# Mainboard_LEFT.net
KiCad netlist of a schematic drawn in EAGLE
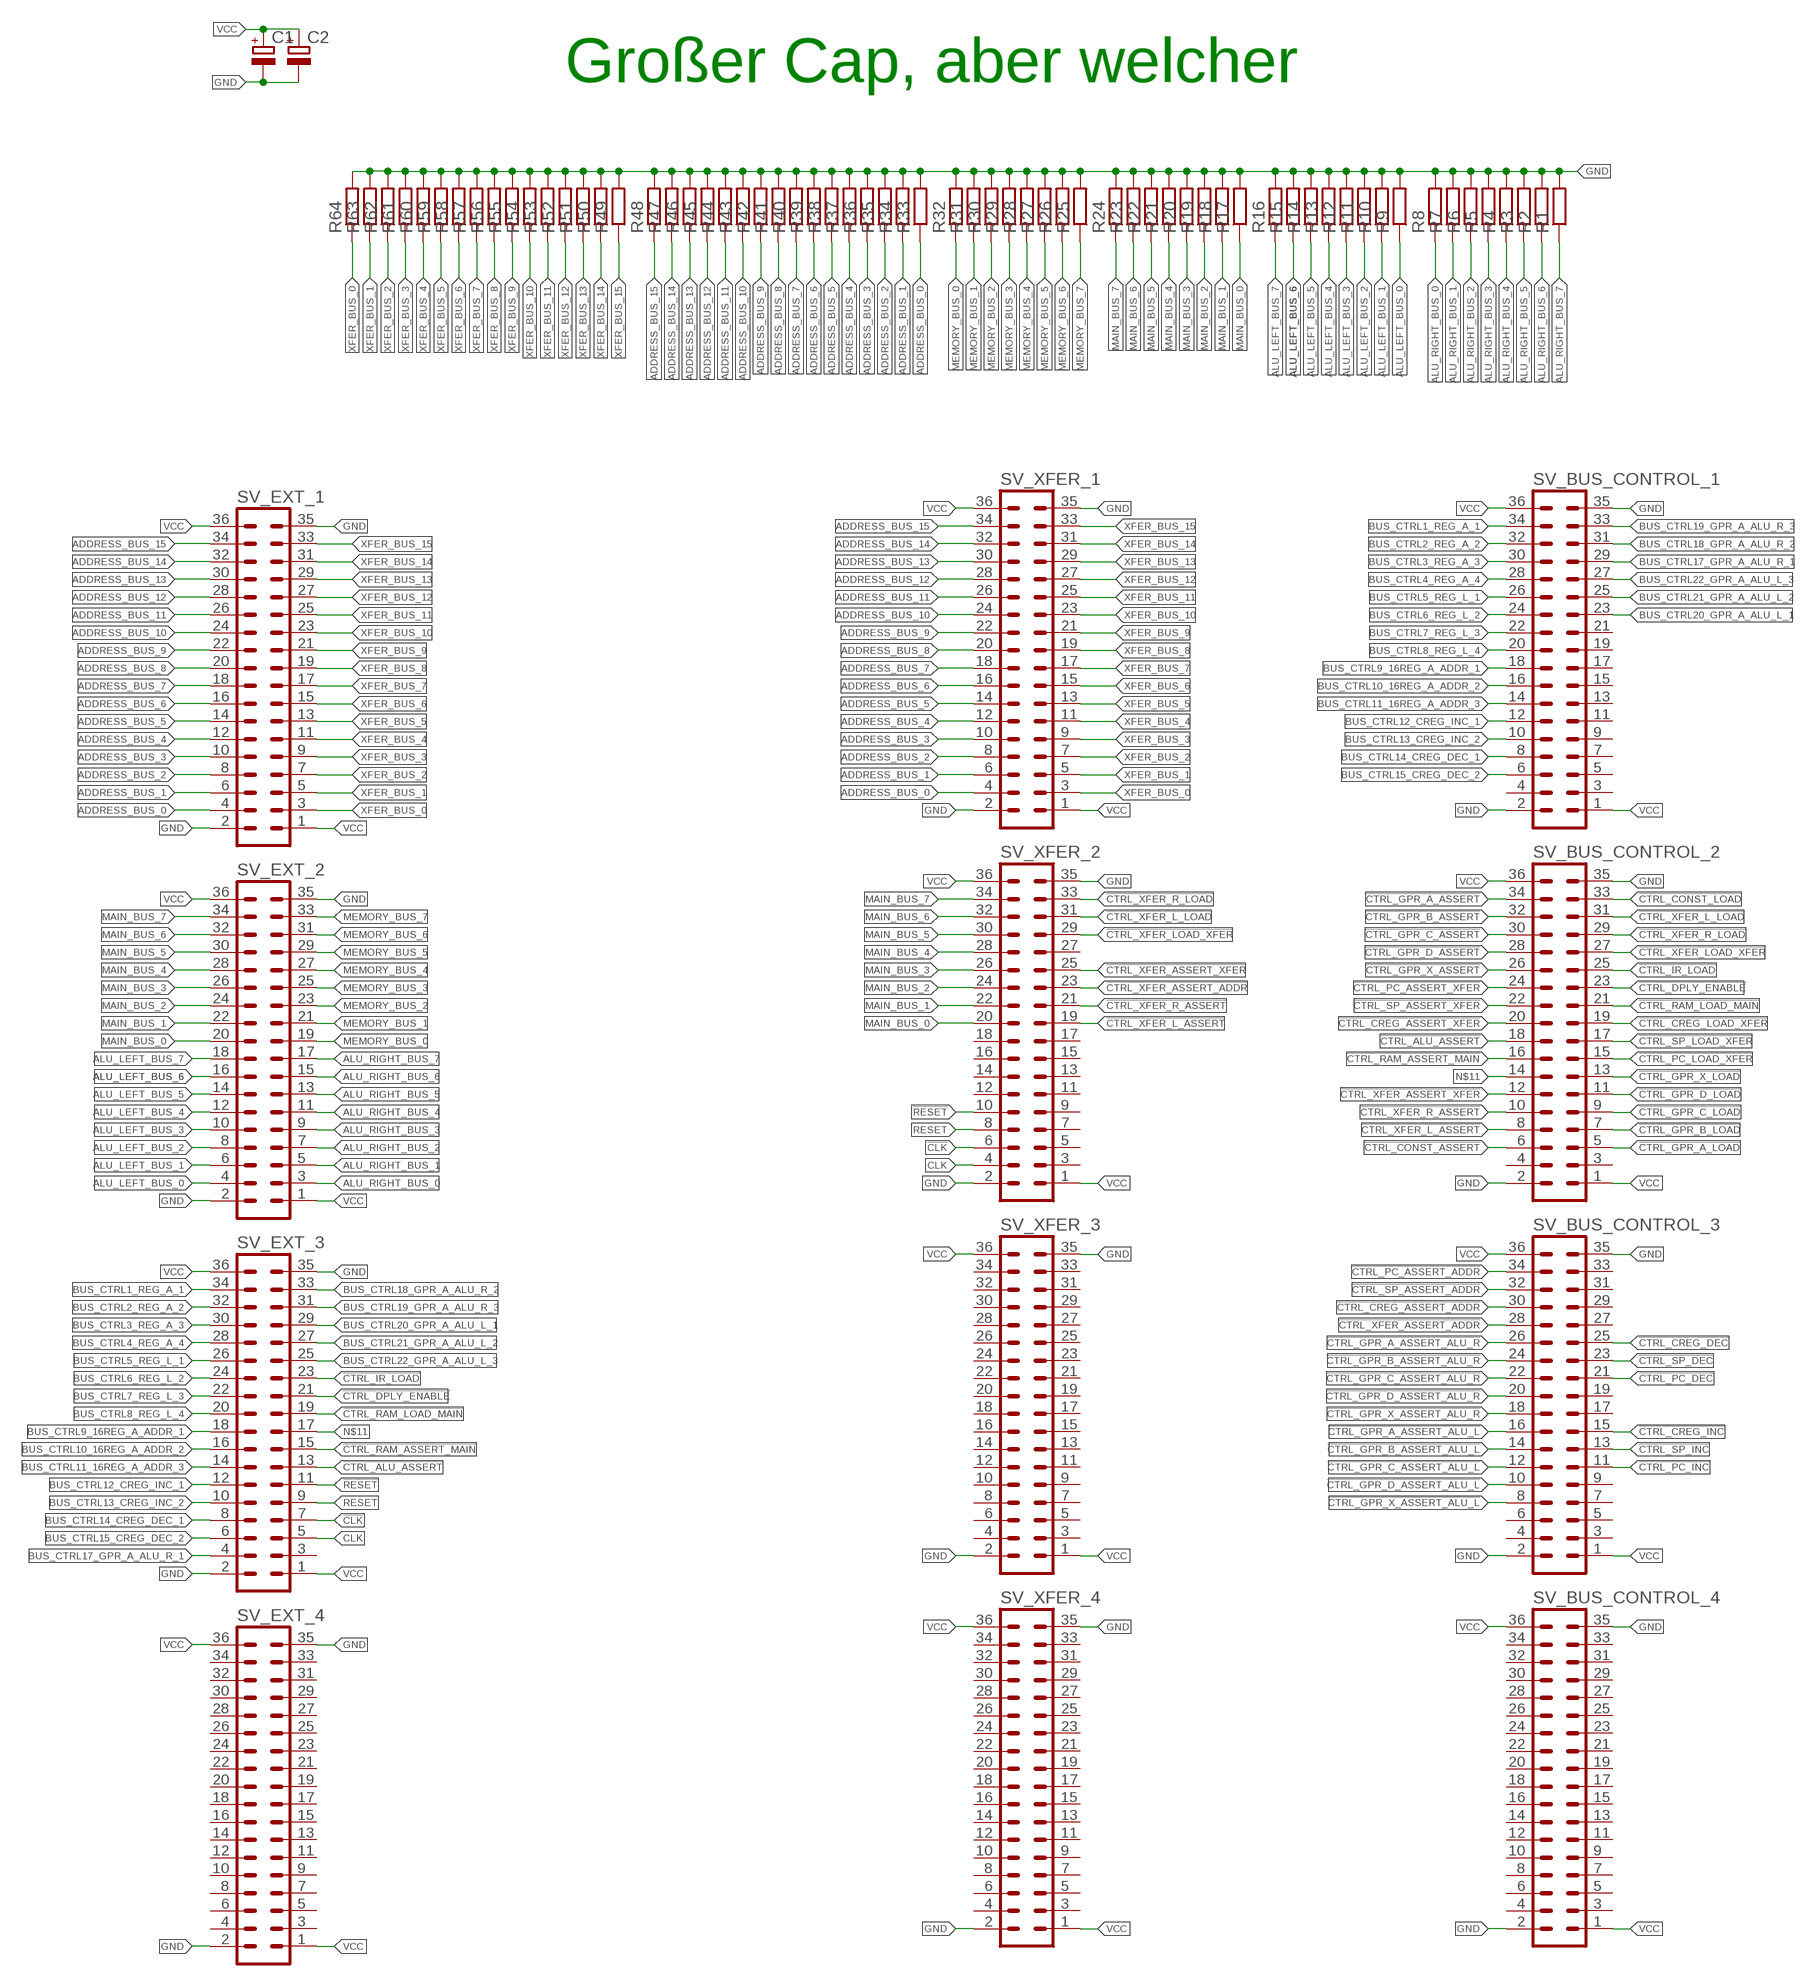
[diagram p0: schematic, sheet 1, part 1 of 2]
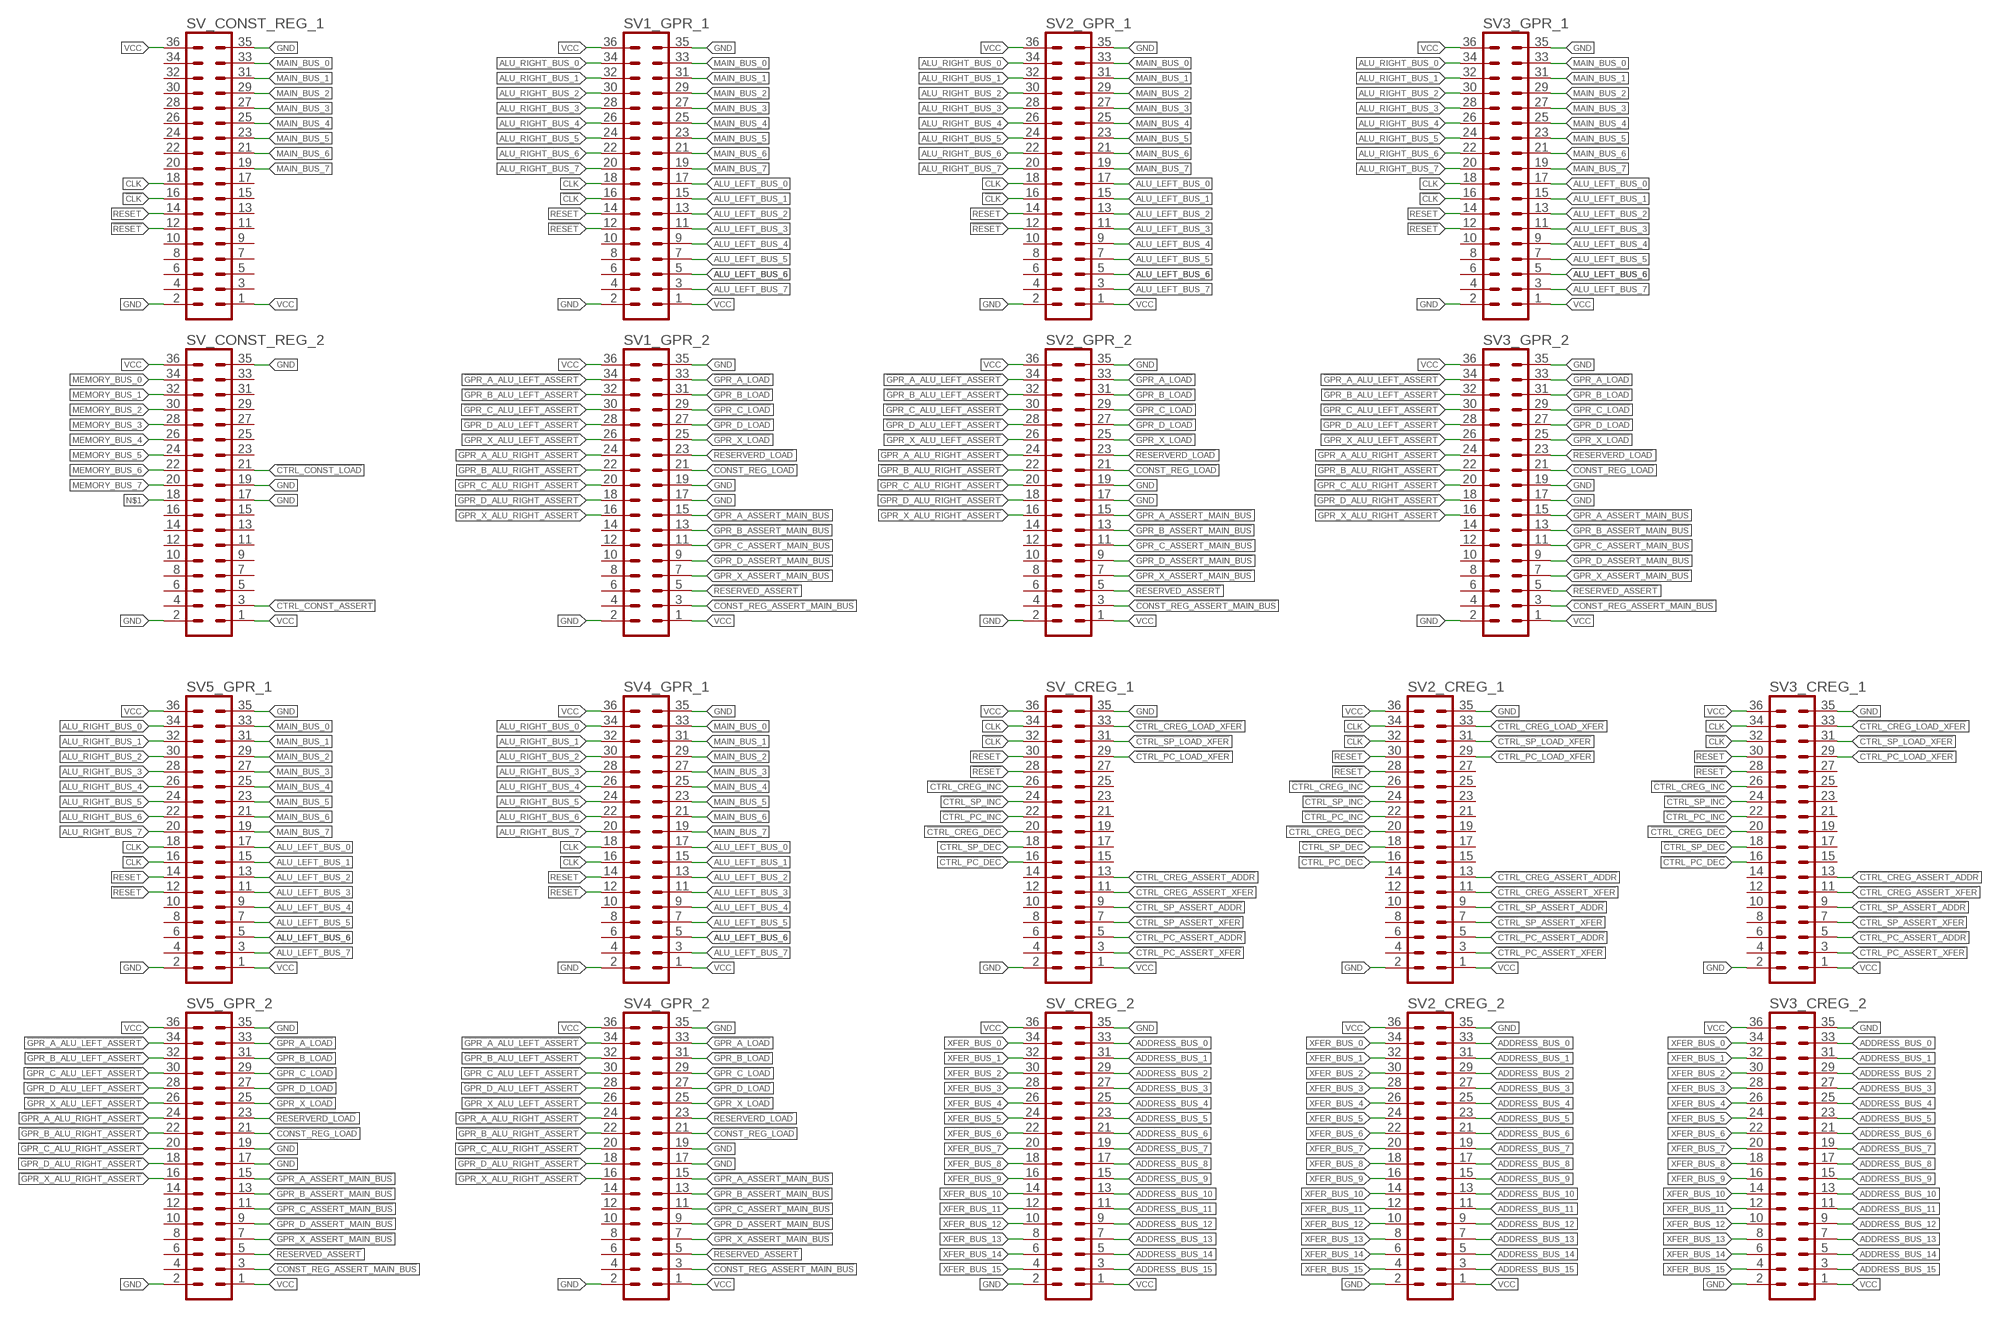
[diagram p1: schematic, sheet 1, part 2 of 2]

(export (version "E")
  (design (tool "Eeschema 10.0.6"))
  (components
    (comp (ref "C1")
      (value "CPOL-EUE5-10.5")
      (footprint "eagle-import:E5-10,5")
      (libsource (lib "eagle-import") (part "CPOL-EUE5-10.5"))
    )
    (comp (ref "C2")
      (value "CPOL-EUE5-10.5")
      (footprint "eagle-import:E5-10,5")
      (libsource (lib "eagle-import") (part "CPOL-EUE5-10.5"))
    )
    (comp (ref "R1")
      (value "R-EU_R0805")
      (footprint "eagle-import:R0805")
      (libsource (lib "eagle-import") (part "R-EU_R0805"))
    )
    (comp (ref "R2")
      (value "R-EU_R0805")
      (footprint "eagle-import:R0805")
      (libsource (lib "eagle-import") (part "R-EU_R0805"))
    )
    (comp (ref "R3")
      (value "R-EU_R0805")
      (footprint "eagle-import:R0805")
      (libsource (lib "eagle-import") (part "R-EU_R0805"))
    )
    (comp (ref "R4")
      (value "R-EU_R0805")
      (footprint "eagle-import:R0805")
      (libsource (lib "eagle-import") (part "R-EU_R0805"))
    )
    (comp (ref "R5")
      (value "R-EU_R0805")
      (footprint "eagle-import:R0805")
      (libsource (lib "eagle-import") (part "R-EU_R0805"))
    )
    (comp (ref "R6")
      (value "R-EU_R0805")
      (footprint "eagle-import:R0805")
      (libsource (lib "eagle-import") (part "R-EU_R0805"))
    )
    (comp (ref "R7")
      (value "R-EU_R0805")
      (footprint "eagle-import:R0805")
      (libsource (lib "eagle-import") (part "R-EU_R0805"))
    )
    (comp (ref "R8")
      (value "R-EU_R0805")
      (footprint "eagle-import:R0805")
      (libsource (lib "eagle-import") (part "R-EU_R0805"))
    )
    (comp (ref "R9")
      (value "R-EU_R0805")
      (footprint "eagle-import:R0805")
      (libsource (lib "eagle-import") (part "R-EU_R0805"))
    )
    (comp (ref "R10")
      (value "R-EU_R0805")
      (footprint "eagle-import:R0805")
      (libsource (lib "eagle-import") (part "R-EU_R0805"))
    )
    (comp (ref "R11")
      (value "R-EU_R0805")
      (footprint "eagle-import:R0805")
      (libsource (lib "eagle-import") (part "R-EU_R0805"))
    )
    (comp (ref "R12")
      (value "R-EU_R0805")
      (footprint "eagle-import:R0805")
      (libsource (lib "eagle-import") (part "R-EU_R0805"))
    )
    (comp (ref "R13")
      (value "R-EU_R0805")
      (footprint "eagle-import:R0805")
      (libsource (lib "eagle-import") (part "R-EU_R0805"))
    )
    (comp (ref "R14")
      (value "R-EU_R0805")
      (footprint "eagle-import:R0805")
      (libsource (lib "eagle-import") (part "R-EU_R0805"))
    )
    (comp (ref "R15")
      (value "R-EU_R0805")
      (footprint "eagle-import:R0805")
      (libsource (lib "eagle-import") (part "R-EU_R0805"))
    )
    (comp (ref "R16")
      (value "R-EU_R0805")
      (footprint "eagle-import:R0805")
      (libsource (lib "eagle-import") (part "R-EU_R0805"))
    )
    (comp (ref "R17")
      (value "R-EU_R0805")
      (footprint "eagle-import:R0805")
      (libsource (lib "eagle-import") (part "R-EU_R0805"))
    )
    (comp (ref "R18")
      (value "R-EU_R0805")
      (footprint "eagle-import:R0805")
      (libsource (lib "eagle-import") (part "R-EU_R0805"))
    )
    (comp (ref "R19")
      (value "R-EU_R0805")
      (footprint "eagle-import:R0805")
      (libsource (lib "eagle-import") (part "R-EU_R0805"))
    )
    (comp (ref "R20")
      (value "R-EU_R0805")
      (footprint "eagle-import:R0805")
      (libsource (lib "eagle-import") (part "R-EU_R0805"))
    )
    (comp (ref "R21")
      (value "R-EU_R0805")
      (footprint "eagle-import:R0805")
      (libsource (lib "eagle-import") (part "R-EU_R0805"))
    )
    (comp (ref "R22")
      (value "R-EU_R0805")
      (footprint "eagle-import:R0805")
      (libsource (lib "eagle-import") (part "R-EU_R0805"))
    )
    (comp (ref "R23")
      (value "R-EU_R0805")
      (footprint "eagle-import:R0805")
      (libsource (lib "eagle-import") (part "R-EU_R0805"))
    )
    (comp (ref "R24")
      (value "R-EU_R0805")
      (footprint "eagle-import:R0805")
      (libsource (lib "eagle-import") (part "R-EU_R0805"))
    )
    (comp (ref "R25")
      (value "R-EU_R0805")
      (footprint "eagle-import:R0805")
      (libsource (lib "eagle-import") (part "R-EU_R0805"))
    )
    (comp (ref "R26")
      (value "R-EU_R0805")
      (footprint "eagle-import:R0805")
      (libsource (lib "eagle-import") (part "R-EU_R0805"))
    )
    (comp (ref "R27")
      (value "R-EU_R0805")
      (footprint "eagle-import:R0805")
      (libsource (lib "eagle-import") (part "R-EU_R0805"))
    )
    (comp (ref "R28")
      (value "R-EU_R0805")
      (footprint "eagle-import:R0805")
      (libsource (lib "eagle-import") (part "R-EU_R0805"))
    )
    (comp (ref "R29")
      (value "R-EU_R0805")
      (footprint "eagle-import:R0805")
      (libsource (lib "eagle-import") (part "R-EU_R0805"))
    )
    (comp (ref "R30")
      (value "R-EU_R0805")
      (footprint "eagle-import:R0805")
      (libsource (lib "eagle-import") (part "R-EU_R0805"))
    )
    (comp (ref "R31")
      (value "R-EU_R0805")
      (footprint "eagle-import:R0805")
      (libsource (lib "eagle-import") (part "R-EU_R0805"))
    )
    (comp (ref "R32")
      (value "R-EU_R0805")
      (footprint "eagle-import:R0805")
      (libsource (lib "eagle-import") (part "R-EU_R0805"))
    )
    (comp (ref "R33")
      (value "R-EU_R0805")
      (footprint "eagle-import:R0805")
      (libsource (lib "eagle-import") (part "R-EU_R0805"))
    )
    (comp (ref "R34")
      (value "R-EU_R0805")
      (footprint "eagle-import:R0805")
      (libsource (lib "eagle-import") (part "R-EU_R0805"))
    )
    (comp (ref "R35")
      (value "R-EU_R0805")
      (footprint "eagle-import:R0805")
      (libsource (lib "eagle-import") (part "R-EU_R0805"))
    )
    (comp (ref "R36")
      (value "R-EU_R0805")
      (footprint "eagle-import:R0805")
      (libsource (lib "eagle-import") (part "R-EU_R0805"))
    )
    (comp (ref "R37")
      (value "R-EU_R0805")
      (footprint "eagle-import:R0805")
      (libsource (lib "eagle-import") (part "R-EU_R0805"))
    )
    (comp (ref "R38")
      (value "R-EU_R0805")
      (footprint "eagle-import:R0805")
      (libsource (lib "eagle-import") (part "R-EU_R0805"))
    )
    (comp (ref "R39")
      (value "R-EU_R0805")
      (footprint "eagle-import:R0805")
      (libsource (lib "eagle-import") (part "R-EU_R0805"))
    )
    (comp (ref "R40")
      (value "R-EU_R0805")
      (footprint "eagle-import:R0805")
      (libsource (lib "eagle-import") (part "R-EU_R0805"))
    )
    (comp (ref "R41")
      (value "R-EU_R0805")
      (footprint "eagle-import:R0805")
      (libsource (lib "eagle-import") (part "R-EU_R0805"))
    )
    (comp (ref "R42")
      (value "R-EU_R0805")
      (footprint "eagle-import:R0805")
      (libsource (lib "eagle-import") (part "R-EU_R0805"))
    )
    (comp (ref "R43")
      (value "R-EU_R0805")
      (footprint "eagle-import:R0805")
      (libsource (lib "eagle-import") (part "R-EU_R0805"))
    )
    (comp (ref "R44")
      (value "R-EU_R0805")
      (footprint "eagle-import:R0805")
      (libsource (lib "eagle-import") (part "R-EU_R0805"))
    )
    (comp (ref "R45")
      (value "R-EU_R0805")
      (footprint "eagle-import:R0805")
      (libsource (lib "eagle-import") (part "R-EU_R0805"))
    )
    (comp (ref "R46")
      (value "R-EU_R0805")
      (footprint "eagle-import:R0805")
      (libsource (lib "eagle-import") (part "R-EU_R0805"))
    )
    (comp (ref "R47")
      (value "R-EU_R0805")
      (footprint "eagle-import:R0805")
      (libsource (lib "eagle-import") (part "R-EU_R0805"))
    )
    (comp (ref "R48")
      (value "R-EU_R0805")
      (footprint "eagle-import:R0805")
      (libsource (lib "eagle-import") (part "R-EU_R0805"))
    )
    (comp (ref "R49")
      (value "R-EU_R0805")
      (footprint "eagle-import:R0805")
      (libsource (lib "eagle-import") (part "R-EU_R0805"))
    )
    (comp (ref "R50")
      (value "R-EU_R0805")
      (footprint "eagle-import:R0805")
      (libsource (lib "eagle-import") (part "R-EU_R0805"))
    )
    (comp (ref "R51")
      (value "R-EU_R0805")
      (footprint "eagle-import:R0805")
      (libsource (lib "eagle-import") (part "R-EU_R0805"))
    )
    (comp (ref "R52")
      (value "R-EU_R0805")
      (footprint "eagle-import:R0805")
      (libsource (lib "eagle-import") (part "R-EU_R0805"))
    )
    (comp (ref "R53")
      (value "R-EU_R0805")
      (footprint "eagle-import:R0805")
      (libsource (lib "eagle-import") (part "R-EU_R0805"))
    )
    (comp (ref "R54")
      (value "R-EU_R0805")
      (footprint "eagle-import:R0805")
      (libsource (lib "eagle-import") (part "R-EU_R0805"))
    )
    (comp (ref "R55")
      (value "R-EU_R0805")
      (footprint "eagle-import:R0805")
      (libsource (lib "eagle-import") (part "R-EU_R0805"))
    )
    (comp (ref "R56")
      (value "R-EU_R0805")
      (footprint "eagle-import:R0805")
      (libsource (lib "eagle-import") (part "R-EU_R0805"))
    )
    (comp (ref "R57")
      (value "R-EU_R0805")
      (footprint "eagle-import:R0805")
      (libsource (lib "eagle-import") (part "R-EU_R0805"))
    )
    (comp (ref "R58")
      (value "R-EU_R0805")
      (footprint "eagle-import:R0805")
      (libsource (lib "eagle-import") (part "R-EU_R0805"))
    )
    (comp (ref "R59")
      (value "R-EU_R0805")
      (footprint "eagle-import:R0805")
      (libsource (lib "eagle-import") (part "R-EU_R0805"))
    )
    (comp (ref "R60")
      (value "R-EU_R0805")
      (footprint "eagle-import:R0805")
      (libsource (lib "eagle-import") (part "R-EU_R0805"))
    )
    (comp (ref "R61")
      (value "R-EU_R0805")
      (footprint "eagle-import:R0805")
      (libsource (lib "eagle-import") (part "R-EU_R0805"))
    )
    (comp (ref "R62")
      (value "R-EU_R0805")
      (footprint "eagle-import:R0805")
      (libsource (lib "eagle-import") (part "R-EU_R0805"))
    )
    (comp (ref "R63")
      (value "R-EU_R0805")
      (footprint "eagle-import:R0805")
      (libsource (lib "eagle-import") (part "R-EU_R0805"))
    )
    (comp (ref "R64")
      (value "R-EU_R0805")
      (footprint "eagle-import:R0805")
      (libsource (lib "eagle-import") (part "R-EU_R0805"))
    )
    (comp (ref "SV1_GPR_1")
      (value "MA18-2")
      (footprint "eagle-import:MA18-2")
      (libsource (lib "eagle-import") (part "MA18-2"))
    )
    (comp (ref "SV1_GPR_2")
      (value "MA18-2")
      (footprint "eagle-import:MA18-2")
      (libsource (lib "eagle-import") (part "MA18-2"))
    )
    (comp (ref "SV2_CREG_1")
      (value "MA18-2")
      (footprint "eagle-import:MA18-2")
      (libsource (lib "eagle-import") (part "MA18-2"))
    )
    (comp (ref "SV2_CREG_2")
      (value "MA18-2")
      (footprint "eagle-import:MA18-2")
      (libsource (lib "eagle-import") (part "MA18-2"))
    )
    (comp (ref "SV2_GPR_1")
      (value "MA18-2")
      (footprint "eagle-import:MA18-2")
      (libsource (lib "eagle-import") (part "MA18-2"))
    )
    (comp (ref "SV2_GPR_2")
      (value "MA18-2")
      (footprint "eagle-import:MA18-2")
      (libsource (lib "eagle-import") (part "MA18-2"))
    )
    (comp (ref "SV3_CREG_1")
      (value "MA18-2")
      (footprint "eagle-import:MA18-2")
      (libsource (lib "eagle-import") (part "MA18-2"))
    )
    (comp (ref "SV3_CREG_2")
      (value "MA18-2")
      (footprint "eagle-import:MA18-2")
      (libsource (lib "eagle-import") (part "MA18-2"))
    )
    (comp (ref "SV3_GPR_1")
      (value "MA18-2")
      (footprint "eagle-import:MA18-2")
      (libsource (lib "eagle-import") (part "MA18-2"))
    )
    (comp (ref "SV3_GPR_2")
      (value "MA18-2")
      (footprint "eagle-import:MA18-2")
      (libsource (lib "eagle-import") (part "MA18-2"))
    )
    (comp (ref "SV4_GPR_1")
      (value "MA18-2")
      (footprint "eagle-import:MA18-2")
      (libsource (lib "eagle-import") (part "MA18-2"))
    )
    (comp (ref "SV4_GPR_2")
      (value "MA18-2")
      (footprint "eagle-import:MA18-2")
      (libsource (lib "eagle-import") (part "MA18-2"))
    )
    (comp (ref "SV5_GPR_1")
      (value "MA18-2")
      (footprint "eagle-import:MA18-2")
      (libsource (lib "eagle-import") (part "MA18-2"))
    )
    (comp (ref "SV5_GPR_2")
      (value "MA18-2")
      (footprint "eagle-import:MA18-2")
      (libsource (lib "eagle-import") (part "MA18-2"))
    )
    (comp (ref "SV_BUS_CONTROL_1")
      (value "MA18-2")
      (footprint "eagle-import:MA18-2")
      (libsource (lib "eagle-import") (part "MA18-2"))
    )
    (comp (ref "SV_BUS_CONTROL_2")
      (value "MA18-2")
      (footprint "eagle-import:MA18-2")
      (libsource (lib "eagle-import") (part "MA18-2"))
    )
    (comp (ref "SV_BUS_CONTROL_3")
      (value "MA18-2")
      (footprint "eagle-import:MA18-2")
      (libsource (lib "eagle-import") (part "MA18-2"))
    )
    (comp (ref "SV_BUS_CONTROL_4")
      (value "MA18-2")
      (footprint "eagle-import:MA18-2")
      (libsource (lib "eagle-import") (part "MA18-2"))
    )
    (comp (ref "SV_CONST_REG_1")
      (value "MA18-2")
      (footprint "eagle-import:MA18-2")
      (libsource (lib "eagle-import") (part "MA18-2"))
    )
    (comp (ref "SV_CONST_REG_2")
      (value "MA18-2")
      (footprint "eagle-import:MA18-2")
      (libsource (lib "eagle-import") (part "MA18-2"))
    )
    (comp (ref "SV_CREG_1")
      (value "MA18-2")
      (footprint "eagle-import:MA18-2")
      (libsource (lib "eagle-import") (part "MA18-2"))
    )
    (comp (ref "SV_CREG_2")
      (value "MA18-2")
      (footprint "eagle-import:MA18-2")
      (libsource (lib "eagle-import") (part "MA18-2"))
    )
    (comp (ref "SV_EXT_1")
      (value "MA18-2W")
      (footprint "eagle-import:MA18-2W")
      (libsource (lib "eagle-import") (part "MA18-2W"))
    )
    (comp (ref "SV_EXT_2")
      (value "MA18-2W")
      (footprint "eagle-import:MA18-2W")
      (libsource (lib "eagle-import") (part "MA18-2W"))
    )
    (comp (ref "SV_EXT_3")
      (value "MA18-2W")
      (footprint "eagle-import:MA18-2W")
      (libsource (lib "eagle-import") (part "MA18-2W"))
    )
    (comp (ref "SV_EXT_4")
      (value "MA18-2W")
      (footprint "eagle-import:MA18-2W")
      (libsource (lib "eagle-import") (part "MA18-2W"))
    )
    (comp (ref "SV_XFER_1")
      (value "MA18-2")
      (footprint "eagle-import:MA18-2")
      (libsource (lib "eagle-import") (part "MA18-2"))
    )
    (comp (ref "SV_XFER_2")
      (value "MA18-2")
      (footprint "eagle-import:MA18-2")
      (libsource (lib "eagle-import") (part "MA18-2"))
    )
    (comp (ref "SV_XFER_3")
      (value "MA18-2")
      (footprint "eagle-import:MA18-2")
      (libsource (lib "eagle-import") (part "MA18-2"))
    )
    (comp (ref "SV_XFER_4")
      (value "MA18-2")
      (footprint "eagle-import:MA18-2")
      (libsource (lib "eagle-import") (part "MA18-2"))
    )
  )
  (nets
    (net (code "1") (name "/~{CLK}") (class "Default")
      (node (ref "SV1_GPR_1") (pin "16") (pinfunction "16_16") (pintype "passive"))
      (node (ref "SV2_CREG_1") (pin "32") (pinfunction "32_32") (pintype "passive"))
      (node (ref "SV2_GPR_1") (pin "16") (pinfunction "16_16") (pintype "passive"))
      (node (ref "SV3_CREG_1") (pin "32") (pinfunction "32_32") (pintype "passive"))
      (node (ref "SV3_GPR_1") (pin "16") (pinfunction "16_16") (pintype "passive"))
      (node (ref "SV4_GPR_1") (pin "16") (pinfunction "16_16") (pintype "passive"))
      (node (ref "SV5_GPR_1") (pin "16") (pinfunction "16_16") (pintype "passive"))
      (node (ref "SV_CONST_REG_1") (pin "16") (pinfunction "16_16") (pintype "passive"))
      (node (ref "SV_CREG_1") (pin "32") (pinfunction "32_32") (pintype "passive"))
      (node (ref "SV_EXT_3") (pin "7") (pinfunction "7_7") (pintype "passive"))
      (node (ref "SV_XFER_2") (pin "6") (pinfunction "6_6") (pintype "passive"))
    )
    (net (code "2") (name "/~{CONST_REG_ASSERT_MAIN_BUS}") (class "Default")
      (node (ref "SV1_GPR_2") (pin "3") (pinfunction "3_3") (pintype "passive"))
      (node (ref "SV2_GPR_2") (pin "3") (pinfunction "3_3") (pintype "passive"))
      (node (ref "SV3_GPR_2") (pin "3") (pinfunction "3_3") (pintype "passive"))
      (node (ref "SV4_GPR_2") (pin "3") (pinfunction "3_3") (pintype "passive"))
      (node (ref "SV5_GPR_2") (pin "3") (pinfunction "3_3") (pintype "passive"))
    )
    (net (code "3") (name "/~{CONST_REG_LOAD}") (class "Default")
      (node (ref "SV1_GPR_2") (pin "21") (pinfunction "21_21") (pintype "passive"))
      (node (ref "SV2_GPR_2") (pin "21") (pinfunction "21_21") (pintype "passive"))
      (node (ref "SV3_GPR_2") (pin "21") (pinfunction "21_21") (pintype "passive"))
      (node (ref "SV4_GPR_2") (pin "21") (pinfunction "21_21") (pintype "passive"))
      (node (ref "SV5_GPR_2") (pin "21") (pinfunction "21_21") (pintype "passive"))
    )
    (net (code "4") (name "/~{CTRL_ALU_ASSERT}") (class "Default")
      (node (ref "SV_BUS_CONTROL_2") (pin "18") (pinfunction "18_18") (pintype "passive"))
      (node (ref "SV_EXT_3") (pin "13") (pinfunction "13_13") (pintype "passive"))
    )
    (net (code "5") (name "/~{CTRL_CONST_ASSERT}") (class "Default")
      (node (ref "SV_BUS_CONTROL_2") (pin "6") (pinfunction "6_6") (pintype "passive"))
      (node (ref "SV_CONST_REG_2") (pin "3") (pinfunction "3_3") (pintype "passive"))
    )
    (net (code "6") (name "/~{CTRL_CONST_LOAD}") (class "Default")
      (node (ref "SV_BUS_CONTROL_2") (pin "33") (pinfunction "33_33") (pintype "passive"))
      (node (ref "SV_CONST_REG_2") (pin "21") (pinfunction "21_21") (pintype "passive"))
    )
    (net (code "7") (name "/~{CTRL_CREG_ASSERT_ADDR}") (class "Default")
      (node (ref "SV2_CREG_1") (pin "13") (pinfunction "13_13") (pintype "passive"))
      (node (ref "SV3_CREG_1") (pin "13") (pinfunction "13_13") (pintype "passive"))
      (node (ref "SV_BUS_CONTROL_3") (pin "30") (pinfunction "30_30") (pintype "passive"))
      (node (ref "SV_CREG_1") (pin "13") (pinfunction "13_13") (pintype "passive"))
    )
    (net (code "8") (name "/~{CTRL_CREG_ASSERT_XFER}") (class "Default")
      (node (ref "SV2_CREG_1") (pin "11") (pinfunction "11_11") (pintype "passive"))
      (node (ref "SV3_CREG_1") (pin "11") (pinfunction "11_11") (pintype "passive"))
      (node (ref "SV_BUS_CONTROL_2") (pin "20") (pinfunction "20_20") (pintype "passive"))
      (node (ref "SV_CREG_1") (pin "11") (pinfunction "11_11") (pintype "passive"))
    )
    (net (code "9") (name "/~{CTRL_CREG_DEC}") (class "Default")
      (node (ref "SV2_CREG_1") (pin "20") (pinfunction "20_20") (pintype "passive"))
      (node (ref "SV3_CREG_1") (pin "20") (pinfunction "20_20") (pintype "passive"))
      (node (ref "SV_BUS_CONTROL_3") (pin "25") (pinfunction "25_25") (pintype "passive"))
      (node (ref "SV_CREG_1") (pin "20") (pinfunction "20_20") (pintype "passive"))
    )
    (net (code "10") (name "/~{CTRL_CREG_INC}") (class "Default")
      (node (ref "SV2_CREG_1") (pin "26") (pinfunction "26_26") (pintype "passive"))
      (node (ref "SV3_CREG_1") (pin "26") (pinfunction "26_26") (pintype "passive"))
      (node (ref "SV_BUS_CONTROL_3") (pin "15") (pinfunction "15_15") (pintype "passive"))
      (node (ref "SV_CREG_1") (pin "26") (pinfunction "26_26") (pintype "passive"))
    )
    (net (code "11") (name "/~{CTRL_CREG_LOAD_XFER}") (class "Default")
      (node (ref "SV2_CREG_1") (pin "33") (pinfunction "33_33") (pintype "passive"))
      (node (ref "SV3_CREG_1") (pin "33") (pinfunction "33_33") (pintype "passive"))
      (node (ref "SV_BUS_CONTROL_2") (pin "19") (pinfunction "19_19") (pintype "passive"))
      (node (ref "SV_CREG_1") (pin "33") (pinfunction "33_33") (pintype "passive"))
    )
    (net (code "12") (name "/~{CTRL_DPLY_ENABLE}") (class "Default")
      (node (ref "SV_BUS_CONTROL_2") (pin "23") (pinfunction "23_23") (pintype "passive"))
      (node (ref "SV_EXT_3") (pin "21") (pinfunction "21_21") (pintype "passive"))
    )
    (net (code "13") (name "/~{CTRL_GPR_A_ASSERT_ALU_L}") (class "Default")
      (node (ref "SV_BUS_CONTROL_3") (pin "16") (pinfunction "16_16") (pintype "passive"))
    )
    (net (code "14") (name "/~{CTRL_GPR_A_ASSERT_ALU_R}") (class "Default")
      (node (ref "SV_BUS_CONTROL_3") (pin "26") (pinfunction "26_26") (pintype "passive"))
    )
    (net (code "15") (name "/~{CTRL_GPR_A_ASSERT}") (class "Default")
      (node (ref "SV_BUS_CONTROL_2") (pin "34") (pinfunction "34_34") (pintype "passive"))
    )
    (net (code "16") (name "/~{CTRL_GPR_A_LOAD}") (class "Default")
      (node (ref "SV_BUS_CONTROL_2") (pin "5") (pinfunction "5_5") (pintype "passive"))
    )
    (net (code "17") (name "/~{CTRL_GPR_B_ASSERT_ALU_L}") (class "Default")
      (node (ref "SV_BUS_CONTROL_3") (pin "14") (pinfunction "14_14") (pintype "passive"))
    )
    (net (code "18") (name "/~{CTRL_GPR_B_ASSERT_ALU_R}") (class "Default")
      (node (ref "SV_BUS_CONTROL_3") (pin "24") (pinfunction "24_24") (pintype "passive"))
    )
    (net (code "19") (name "/~{CTRL_GPR_B_ASSERT}") (class "Default")
      (node (ref "SV_BUS_CONTROL_2") (pin "32") (pinfunction "32_32") (pintype "passive"))
    )
    (net (code "20") (name "/~{CTRL_GPR_B_LOAD}") (class "Default")
      (node (ref "SV_BUS_CONTROL_2") (pin "7") (pinfunction "7_7") (pintype "passive"))
    )
    (net (code "21") (name "/~{CTRL_GPR_C_ASSERT_ALU_L}") (class "Default")
      (node (ref "SV_BUS_CONTROL_3") (pin "12") (pinfunction "12_12") (pintype "passive"))
    )
    (net (code "22") (name "/~{CTRL_GPR_C_ASSERT_ALU_R}") (class "Default")
      (node (ref "SV_BUS_CONTROL_3") (pin "22") (pinfunction "22_22") (pintype "passive"))
    )
    (net (code "23") (name "/~{CTRL_GPR_C_ASSERT}") (class "Default")
      (node (ref "SV_BUS_CONTROL_2") (pin "30") (pinfunction "30_30") (pintype "passive"))
    )
    (net (code "24") (name "/~{CTRL_GPR_C_LOAD}") (class "Default")
      (node (ref "SV_BUS_CONTROL_2") (pin "9") (pinfunction "9_9") (pintype "passive"))
    )
    (net (code "25") (name "/~{CTRL_GPR_D_ASSERT_ALU_L}") (class "Default")
      (node (ref "SV_BUS_CONTROL_3") (pin "10") (pinfunction "10_10") (pintype "passive"))
    )
    (net (code "26") (name "/~{CTRL_GPR_D_ASSERT_ALU_R}") (class "Default")
      (node (ref "SV_BUS_CONTROL_3") (pin "20") (pinfunction "20_20") (pintype "passive"))
    )
    (net (code "27") (name "/~{CTRL_GPR_D_ASSERT}") (class "Default")
      (node (ref "SV_BUS_CONTROL_2") (pin "28") (pinfunction "28_28") (pintype "passive"))
    )
    (net (code "28") (name "/~{CTRL_GPR_D_LOAD}") (class "Default")
      (node (ref "SV_BUS_CONTROL_2") (pin "11") (pinfunction "11_11") (pintype "passive"))
    )
    (net (code "29") (name "/~{CTRL_GPR_X_ASSERT_ALU_L}") (class "Default")
      (node (ref "SV_BUS_CONTROL_3") (pin "8") (pinfunction "8_8") (pintype "passive"))
    )
    (net (code "30") (name "/~{CTRL_GPR_X_ASSERT_ALU_R}") (class "Default")
      (node (ref "SV_BUS_CONTROL_3") (pin "18") (pinfunction "18_18") (pintype "passive"))
    )
    (net (code "31") (name "/~{CTRL_GPR_X_ASSERT}") (class "Default")
      (node (ref "SV_BUS_CONTROL_2") (pin "26") (pinfunction "26_26") (pintype "passive"))
    )
    (net (code "32") (name "/~{CTRL_GPR_X_LOAD}") (class "Default")
      (node (ref "SV_BUS_CONTROL_2") (pin "13") (pinfunction "13_13") (pintype "passive"))
    )
    (net (code "33") (name "/~{CTRL_IR_LOAD}") (class "Default")
      (node (ref "SV_BUS_CONTROL_2") (pin "25") (pinfunction "25_25") (pintype "passive"))
      (node (ref "SV_EXT_3") (pin "23") (pinfunction "23_23") (pintype "passive"))
    )
    (net (code "34") (name "/~{CTRL_PC_ASSERT_ADDR}") (class "Default")
      (node (ref "SV2_CREG_1") (pin "5") (pinfunction "5_5") (pintype "passive"))
      (node (ref "SV3_CREG_1") (pin "5") (pinfunction "5_5") (pintype "passive"))
      (node (ref "SV_BUS_CONTROL_3") (pin "34") (pinfunction "34_34") (pintype "passive"))
      (node (ref "SV_CREG_1") (pin "5") (pinfunction "5_5") (pintype "passive"))
    )
    (net (code "35") (name "/~{CTRL_PC_ASSERT_XFER}") (class "Default")
      (node (ref "SV2_CREG_1") (pin "3") (pinfunction "3_3") (pintype "passive"))
      (node (ref "SV3_CREG_1") (pin "3") (pinfunction "3_3") (pintype "passive"))
      (node (ref "SV_BUS_CONTROL_2") (pin "24") (pinfunction "24_24") (pintype "passive"))
      (node (ref "SV_CREG_1") (pin "3") (pinfunction "3_3") (pintype "passive"))
    )
    (net (code "36") (name "/~{CTRL_PC_DEC}") (class "Default")
      (node (ref "SV2_CREG_1") (pin "16") (pinfunction "16_16") (pintype "passive"))
      (node (ref "SV3_CREG_1") (pin "16") (pinfunction "16_16") (pintype "passive"))
      (node (ref "SV_BUS_CONTROL_3") (pin "21") (pinfunction "21_21") (pintype "passive"))
      (node (ref "SV_CREG_1") (pin "16") (pinfunction "16_16") (pintype "passive"))
    )
    (net (code "37") (name "/~{CTRL_PC_INC}") (class "Default")
      (node (ref "SV2_CREG_1") (pin "22") (pinfunction "22_22") (pintype "passive"))
      (node (ref "SV3_CREG_1") (pin "22") (pinfunction "22_22") (pintype "passive"))
      (node (ref "SV_BUS_CONTROL_3") (pin "11") (pinfunction "11_11") (pintype "passive"))
      (node (ref "SV_CREG_1") (pin "22") (pinfunction "22_22") (pintype "passive"))
    )
    (net (code "38") (name "/~{CTRL_PC_LOAD_XFER}") (class "Default")
      (node (ref "SV2_CREG_1") (pin "29") (pinfunction "29_29") (pintype "passive"))
      (node (ref "SV3_CREG_1") (pin "29") (pinfunction "29_29") (pintype "passive"))
      (node (ref "SV_BUS_CONTROL_2") (pin "15") (pinfunction "15_15") (pintype "passive"))
      (node (ref "SV_CREG_1") (pin "29") (pinfunction "29_29") (pintype "passive"))
    )
    (net (code "39") (name "/~{CTRL_RAM_ASSERT_MAIN}") (class "Default")
      (node (ref "SV_BUS_CONTROL_2") (pin "16") (pinfunction "16_16") (pintype "passive"))
      (node (ref "SV_EXT_3") (pin "15") (pinfunction "15_15") (pintype "passive"))
    )
    (net (code "40") (name "/~{CTRL_RAM_LOAD_MAIN}") (class "Default")
      (node (ref "SV_BUS_CONTROL_2") (pin "21") (pinfunction "21_21") (pintype "passive"))
      (node (ref "SV_EXT_3") (pin "19") (pinfunction "19_19") (pintype "passive"))
    )
    (net (code "41") (name "/~{CTRL_SP_ASSERT_ADDR}") (class "Default")
      (node (ref "SV2_CREG_1") (pin "9") (pinfunction "9_9") (pintype "passive"))
      (node (ref "SV3_CREG_1") (pin "9") (pinfunction "9_9") (pintype "passive"))
      (node (ref "SV_BUS_CONTROL_3") (pin "32") (pinfunction "32_32") (pintype "passive"))
      (node (ref "SV_CREG_1") (pin "9") (pinfunction "9_9") (pintype "passive"))
    )
    (net (code "42") (name "/~{CTRL_SP_ASSERT_XFER}") (class "Default")
      (node (ref "SV2_CREG_1") (pin "7") (pinfunction "7_7") (pintype "passive"))
      (node (ref "SV3_CREG_1") (pin "7") (pinfunction "7_7") (pintype "passive"))
      (node (ref "SV_BUS_CONTROL_2") (pin "22") (pinfunction "22_22") (pintype "passive"))
      (node (ref "SV_CREG_1") (pin "7") (pinfunction "7_7") (pintype "passive"))
    )
    (net (code "43") (name "/~{CTRL_SP_DEC}") (class "Default")
      (node (ref "SV2_CREG_1") (pin "18") (pinfunction "18_18") (pintype "passive"))
      (node (ref "SV3_CREG_1") (pin "18") (pinfunction "18_18") (pintype "passive"))
      (node (ref "SV_BUS_CONTROL_3") (pin "23") (pinfunction "23_23") (pintype "passive"))
      (node (ref "SV_CREG_1") (pin "18") (pinfunction "18_18") (pintype "passive"))
    )
    (net (code "44") (name "/~{CTRL_SP_INC}") (class "Default")
      (node (ref "SV2_CREG_1") (pin "24") (pinfunction "24_24") (pintype "passive"))
      (node (ref "SV3_CREG_1") (pin "24") (pinfunction "24_24") (pintype "passive"))
      (node (ref "SV_BUS_CONTROL_3") (pin "13") (pinfunction "13_13") (pintype "passive"))
      (node (ref "SV_CREG_1") (pin "24") (pinfunction "24_24") (pintype "passive"))
    )
    (net (code "45") (name "/~{CTRL_SP_LOAD_XFER}") (class "Default")
      (node (ref "SV2_CREG_1") (pin "31") (pinfunction "31_31") (pintype "passive"))
      (node (ref "SV3_CREG_1") (pin "31") (pinfunction "31_31") (pintype "passive"))
      (node (ref "SV_BUS_CONTROL_2") (pin "17") (pinfunction "17_17") (pintype "passive"))
      (node (ref "SV_CREG_1") (pin "31") (pinfunction "31_31") (pintype "passive"))
    )
    (net (code "46") (name "/~{CTRL_XFER_ASSERT_ADDR}") (class "Default")
      (node (ref "SV_BUS_CONTROL_3") (pin "28") (pinfunction "28_28") (pintype "passive"))
      (node (ref "SV_XFER_2") (pin "23") (pinfunction "23_23") (pintype "passive"))
    )
    (net (code "47") (name "/~{CTRL_XFER_ASSERT_XFER}") (class "Default")
      (node (ref "SV_BUS_CONTROL_2") (pin "12") (pinfunction "12_12") (pintype "passive"))
      (node (ref "SV_XFER_2") (pin "25") (pinfunction "25_25") (pintype "passive"))
    )
    (net (code "48") (name "/~{CTRL_XFER_LOAD_XFER}") (class "Default")
      (node (ref "SV_BUS_CONTROL_2") (pin "27") (pinfunction "27_27") (pintype "passive"))
      (node (ref "SV_XFER_2") (pin "29") (pinfunction "29_29") (pintype "passive"))
    )
    (net (code "49") (name "/~{CTRL_XFER_L_ASSERT}") (class "Default")
      (node (ref "SV_BUS_CONTROL_2") (pin "8") (pinfunction "8_8") (pintype "passive"))
      (node (ref "SV_XFER_2") (pin "19") (pinfunction "19_19") (pintype "passive"))
    )
    (net (code "50") (name "/~{CTRL_XFER_L_LOAD}") (class "Default")
      (node (ref "SV_BUS_CONTROL_2") (pin "31") (pinfunction "31_31") (pintype "passive"))
      (node (ref "SV_XFER_2") (pin "31") (pinfunction "31_31") (pintype "passive"))
    )
    (net (code "51") (name "/~{CTRL_XFER_R_ASSERT}") (class "Default")
      (node (ref "SV_BUS_CONTROL_2") (pin "10") (pinfunction "10_10") (pintype "passive"))
      (node (ref "SV_XFER_2") (pin "21") (pinfunction "21_21") (pintype "passive"))
    )
    (net (code "52") (name "/~{CTRL_XFER_R_LOAD}") (class "Default")
      (node (ref "SV_BUS_CONTROL_2") (pin "29") (pinfunction "29_29") (pintype "passive"))
      (node (ref "SV_XFER_2") (pin "33") (pinfunction "33_33") (pintype "passive"))
    )
    (net (code "53") (name "/~{GPR_A_ALU_LEFT_ASSERT}") (class "Default")
      (node (ref "SV1_GPR_2") (pin "34") (pinfunction "34_34") (pintype "passive"))
      (node (ref "SV2_GPR_2") (pin "34") (pinfunction "34_34") (pintype "passive"))
      (node (ref "SV3_GPR_2") (pin "34") (pinfunction "34_34") (pintype "passive"))
      (node (ref "SV4_GPR_2") (pin "34") (pinfunction "34_34") (pintype "passive"))
      (node (ref "SV5_GPR_2") (pin "34") (pinfunction "34_34") (pintype "passive"))
    )
    (net (code "54") (name "/~{GPR_A_ALU_RIGHT_ASSERT}") (class "Default")
      (node (ref "SV1_GPR_2") (pin "24") (pinfunction "24_24") (pintype "passive"))
      (node (ref "SV2_GPR_2") (pin "24") (pinfunction "24_24") (pintype "passive"))
      (node (ref "SV3_GPR_2") (pin "24") (pinfunction "24_24") (pintype "passive"))
      (node (ref "SV4_GPR_2") (pin "24") (pinfunction "24_24") (pintype "passive"))
      (node (ref "SV5_GPR_2") (pin "24") (pinfunction "24_24") (pintype "passive"))
    )
    (net (code "55") (name "/~{GPR_A_ASSERT_MAIN_BUS}") (class "Default")
      (node (ref "SV1_GPR_2") (pin "15") (pinfunction "15_15") (pintype "passive"))
      (node (ref "SV2_GPR_2") (pin "15") (pinfunction "15_15") (pintype "passive"))
      (node (ref "SV3_GPR_2") (pin "15") (pinfunction "15_15") (pintype "passive"))
      (node (ref "SV4_GPR_2") (pin "15") (pinfunction "15_15") (pintype "passive"))
      (node (ref "SV5_GPR_2") (pin "15") (pinfunction "15_15") (pintype "passive"))
    )
    (net (code "56") (name "/~{GPR_A_LOAD}") (class "Default")
      (node (ref "SV1_GPR_2") (pin "33") (pinfunction "33_33") (pintype "passive"))
      (node (ref "SV2_GPR_2") (pin "33") (pinfunction "33_33") (pintype "passive"))
      (node (ref "SV3_GPR_2") (pin "33") (pinfunction "33_33") (pintype "passive"))
      (node (ref "SV4_GPR_2") (pin "33") (pinfunction "33_33") (pintype "passive"))
      (node (ref "SV5_GPR_2") (pin "33") (pinfunction "33_33") (pintype "passive"))
    )
    (net (code "57") (name "/~{GPR_B_ALU_LEFT_ASSERT}") (class "Default")
      (node (ref "SV1_GPR_2") (pin "32") (pinfunction "32_32") (pintype "passive"))
      (node (ref "SV2_GPR_2") (pin "32") (pinfunction "32_32") (pintype "passive"))
      (node (ref "SV3_GPR_2") (pin "32") (pinfunction "32_32") (pintype "passive"))
      (node (ref "SV4_GPR_2") (pin "32") (pinfunction "32_32") (pintype "passive"))
      (node (ref "SV5_GPR_2") (pin "32") (pinfunction "32_32") (pintype "passive"))
    )
    (net (code "58") (name "/~{GPR_B_ALU_RIGHT_ASSERT}") (class "Default")
      (node (ref "SV1_GPR_2") (pin "22") (pinfunction "22_22") (pintype "passive"))
      (node (ref "SV2_GPR_2") (pin "22") (pinfunction "22_22") (pintype "passive"))
      (node (ref "SV3_GPR_2") (pin "22") (pinfunction "22_22") (pintype "passive"))
      (node (ref "SV4_GPR_2") (pin "22") (pinfunction "22_22") (pintype "passive"))
      (node (ref "SV5_GPR_2") (pin "22") (pinfunction "22_22") (pintype "passive"))
    )
    (net (code "59") (name "/~{GPR_B_ASSERT_MAIN_BUS}") (class "Default")
      (node (ref "SV1_GPR_2") (pin "13") (pinfunction "13_13") (pintype "passive"))
      (node (ref "SV2_GPR_2") (pin "13") (pinfunction "13_13") (pintype "passive"))
      (node (ref "SV3_GPR_2") (pin "13") (pinfunction "13_13") (pintype "passive"))
      (node (ref "SV4_GPR_2") (pin "13") (pinfunction "13_13") (pintype "passive"))
      (node (ref "SV5_GPR_2") (pin "13") (pinfunction "13_13") (pintype "passive"))
    )
    (net (code "60") (name "/~{GPR_B_LOAD}") (class "Default")
      (node (ref "SV1_GPR_2") (pin "31") (pinfunction "31_31") (pintype "passive"))
      (node (ref "SV2_GPR_2") (pin "31") (pinfunction "31_31") (pintype "passive"))
      (node (ref "SV3_GPR_2") (pin "31") (pinfunction "31_31") (pintype "passive"))
      (node (ref "SV4_GPR_2") (pin "31") (pinfunction "31_31") (pintype "passive"))
      (node (ref "SV5_GPR_2") (pin "31") (pinfunction "31_31") (pintype "passive"))
    )
    (net (code "61") (name "/~{GPR_C_ALU_LEFT_ASSERT}") (class "Default")
      (node (ref "SV1_GPR_2") (pin "30") (pinfunction "30_30") (pintype "passive"))
      (node (ref "SV2_GPR_2") (pin "30") (pinfunction "30_30") (pintype "passive"))
      (node (ref "SV3_GPR_2") (pin "30") (pinfunction "30_30") (pintype "passive"))
      (node (ref "SV4_GPR_2") (pin "30") (pinfunction "30_30") (pintype "passive"))
      (node (ref "SV5_GPR_2") (pin "30") (pinfunction "30_30") (pintype "passive"))
    )
    (net (code "62") (name "/~{GPR_C_ALU_RIGHT_ASSERT}") (class "Default")
      (node (ref "SV1_GPR_2") (pin "20") (pinfunction "20_20") (pintype "passive"))
      (node (ref "SV2_GPR_2") (pin "20") (pinfunction "20_20") (pintype "passive"))
      (node (ref "SV3_GPR_2") (pin "20") (pinfunction "20_20") (pintype "passive"))
      (node (ref "SV4_GPR_2") (pin "20") (pinfunction "20_20") (pintype "passive"))
      (node (ref "SV5_GPR_2") (pin "20") (pinfunction "20_20") (pintype "passive"))
    )
    (net (code "63") (name "/~{GPR_C_ASSERT_MAIN_BUS}") (class "Default")
      (node (ref "SV1_GPR_2") (pin "11") (pinfunction "11_11") (pintype "passive"))
      (node (ref "SV2_GPR_2") (pin "11") (pinfunction "11_11") (pintype "passive"))
      (node (ref "SV3_GPR_2") (pin "11") (pinfunction "11_11") (pintype "passive"))
      (node (ref "SV4_GPR_2") (pin "11") (pinfunction "11_11") (pintype "passive"))
      (node (ref "SV5_GPR_2") (pin "11") (pinfunction "11_11") (pintype "passive"))
    )
    (net (code "64") (name "/~{GPR_C_LOAD}") (class "Default")
      (node (ref "SV1_GPR_2") (pin "29") (pinfunction "29_29") (pintype "passive"))
      (node (ref "SV2_GPR_2") (pin "29") (pinfunction "29_29") (pintype "passive"))
      (node (ref "SV3_GPR_2") (pin "29") (pinfunction "29_29") (pintype "passive"))
      (node (ref "SV4_GPR_2") (pin "29") (pinfunction "29_29") (pintype "passive"))
      (node (ref "SV5_GPR_2") (pin "29") (pinfunction "29_29") (pintype "passive"))
    )
    (net (code "65") (name "/~{GPR_D_ALU_LEFT_ASSERT}") (class "Default")
      (node (ref "SV1_GPR_2") (pin "28") (pinfunction "28_28") (pintype "passive"))
      (node (ref "SV2_GPR_2") (pin "28") (pinfunction "28_28") (pintype "passive"))
      (node (ref "SV3_GPR_2") (pin "28") (pinfunction "28_28") (pintype "passive"))
      (node (ref "SV4_GPR_2") (pin "28") (pinfunction "28_28") (pintype "passive"))
      (node (ref "SV5_GPR_2") (pin "28") (pinfunction "28_28") (pintype "passive"))
    )
    (net (code "66") (name "/~{GPR_D_ALU_RIGHT_ASSERT}") (class "Default")
      (node (ref "SV1_GPR_2") (pin "18") (pinfunction "18_18") (pintype "passive"))
      (node (ref "SV2_GPR_2") (pin "18") (pinfunction "18_18") (pintype "passive"))
      (node (ref "SV3_GPR_2") (pin "18") (pinfunction "18_18") (pintype "passive"))
      (node (ref "SV4_GPR_2") (pin "18") (pinfunction "18_18") (pintype "passive"))
      (node (ref "SV5_GPR_2") (pin "18") (pinfunction "18_18") (pintype "passive"))
    )
    (net (code "67") (name "/~{GPR_D_ASSERT_MAIN_BUS}") (class "Default")
      (node (ref "SV1_GPR_2") (pin "9") (pinfunction "9_9") (pintype "passive"))
      (node (ref "SV2_GPR_2") (pin "9") (pinfunction "9_9") (pintype "passive"))
      (node (ref "SV3_GPR_2") (pin "9") (pinfunction "9_9") (pintype "passive"))
      (node (ref "SV4_GPR_2") (pin "9") (pinfunction "9_9") (pintype "passive"))
      (node (ref "SV5_GPR_2") (pin "9") (pinfunction "9_9") (pintype "passive"))
    )
    (net (code "68") (name "/~{GPR_D_LOAD}") (class "Default")
      (node (ref "SV1_GPR_2") (pin "27") (pinfunction "27_27") (pintype "passive"))
      (node (ref "SV2_GPR_2") (pin "27") (pinfunction "27_27") (pintype "passive"))
      (node (ref "SV3_GPR_2") (pin "27") (pinfunction "27_27") (pintype "passive"))
      (node (ref "SV4_GPR_2") (pin "27") (pinfunction "27_27") (pintype "passive"))
      (node (ref "SV5_GPR_2") (pin "27") (pinfunction "27_27") (pintype "passive"))
    )
    (net (code "69") (name "/~{GPR_X_ALU_LEFT_ASSERT}") (class "Default")
      (node (ref "SV1_GPR_2") (pin "26") (pinfunction "26_26") (pintype "passive"))
      (node (ref "SV2_GPR_2") (pin "26") (pinfunction "26_26") (pintype "passive"))
      (node (ref "SV3_GPR_2") (pin "26") (pinfunction "26_26") (pintype "passive"))
      (node (ref "SV4_GPR_2") (pin "26") (pinfunction "26_26") (pintype "passive"))
      (node (ref "SV5_GPR_2") (pin "26") (pinfunction "26_26") (pintype "passive"))
    )
    (net (code "70") (name "/~{GPR_X_ALU_RIGHT_ASSERT}") (class "Default")
      (node (ref "SV1_GPR_2") (pin "16") (pinfunction "16_16") (pintype "passive"))
      (node (ref "SV2_GPR_2") (pin "16") (pinfunction "16_16") (pintype "passive"))
      (node (ref "SV3_GPR_2") (pin "16") (pinfunction "16_16") (pintype "passive"))
      (node (ref "SV4_GPR_2") (pin "16") (pinfunction "16_16") (pintype "passive"))
      (node (ref "SV5_GPR_2") (pin "16") (pinfunction "16_16") (pintype "passive"))
    )
    (net (code "71") (name "/~{GPR_X_ASSERT_MAIN_BUS}") (class "Default")
      (node (ref "SV1_GPR_2") (pin "7") (pinfunction "7_7") (pintype "passive"))
      (node (ref "SV2_GPR_2") (pin "7") (pinfunction "7_7") (pintype "passive"))
      (node (ref "SV3_GPR_2") (pin "7") (pinfunction "7_7") (pintype "passive"))
      (node (ref "SV4_GPR_2") (pin "7") (pinfunction "7_7") (pintype "passive"))
      (node (ref "SV5_GPR_2") (pin "7") (pinfunction "7_7") (pintype "passive"))
    )
    (net (code "72") (name "/~{GPR_X_LOAD}") (class "Default")
      (node (ref "SV1_GPR_2") (pin "25") (pinfunction "25_25") (pintype "passive"))
      (node (ref "SV2_GPR_2") (pin "25") (pinfunction "25_25") (pintype "passive"))
      (node (ref "SV3_GPR_2") (pin "25") (pinfunction "25_25") (pintype "passive"))
      (node (ref "SV4_GPR_2") (pin "25") (pinfunction "25_25") (pintype "passive"))
      (node (ref "SV5_GPR_2") (pin "25") (pinfunction "25_25") (pintype "passive"))
    )
    (net (code "73") (name "/~{RESERVED_ASSERT}") (class "Default")
      (node (ref "SV1_GPR_2") (pin "5") (pinfunction "5_5") (pintype "passive"))
      (node (ref "SV2_GPR_2") (pin "5") (pinfunction "5_5") (pintype "passive"))
      (node (ref "SV3_GPR_2") (pin "5") (pinfunction "5_5") (pintype "passive"))
      (node (ref "SV4_GPR_2") (pin "5") (pinfunction "5_5") (pintype "passive"))
      (node (ref "SV5_GPR_2") (pin "5") (pinfunction "5_5") (pintype "passive"))
    )
    (net (code "74") (name "/~{RESERVERD_LOAD}") (class "Default")
      (node (ref "SV1_GPR_2") (pin "23") (pinfunction "23_23") (pintype "passive"))
      (node (ref "SV2_GPR_2") (pin "23") (pinfunction "23_23") (pintype "passive"))
      (node (ref "SV3_GPR_2") (pin "23") (pinfunction "23_23") (pintype "passive"))
      (node (ref "SV4_GPR_2") (pin "23") (pinfunction "23_23") (pintype "passive"))
      (node (ref "SV5_GPR_2") (pin "23") (pinfunction "23_23") (pintype "passive"))
    )
    (net (code "75") (name "/~{RESET}") (class "Default")
      (node (ref "SV1_GPR_1") (pin "12") (pinfunction "12_12") (pintype "passive"))
      (node (ref "SV2_CREG_1") (pin "28") (pinfunction "28_28") (pintype "passive"))
      (node (ref "SV2_GPR_1") (pin "12") (pinfunction "12_12") (pintype "passive"))
      (node (ref "SV3_CREG_1") (pin "28") (pinfunction "28_28") (pintype "passive"))
      (node (ref "SV3_GPR_1") (pin "12") (pinfunction "12_12") (pintype "passive"))
      (node (ref "SV4_GPR_1") (pin "12") (pinfunction "12_12") (pintype "passive"))
      (node (ref "SV5_GPR_1") (pin "12") (pinfunction "12_12") (pintype "passive"))
      (node (ref "SV_CONST_REG_1") (pin "12") (pinfunction "12_12") (pintype "passive"))
      (node (ref "SV_CREG_1") (pin "28") (pinfunction "28_28") (pintype "passive"))
      (node (ref "SV_EXT_3") (pin "11") (pinfunction "11_11") (pintype "passive"))
      (node (ref "SV_XFER_2") (pin "10") (pinfunction "10_10") (pintype "passive"))
    )
    (net (code "76") (name "ADDRESS_BUS_0") (class "Default")
      (node (ref "R33") (pin "1") (pinfunction "1_1") (pintype "passive"))
      (node (ref "SV2_CREG_2") (pin "33") (pinfunction "33_33") (pintype "passive"))
      (node (ref "SV3_CREG_2") (pin "33") (pinfunction "33_33") (pintype "passive"))
      (node (ref "SV_CREG_2") (pin "33") (pinfunction "33_33") (pintype "passive"))
      (node (ref "SV_EXT_1") (pin "4") (pinfunction "4_4") (pintype "passive"))
      (node (ref "SV_XFER_1") (pin "4") (pinfunction "4_4") (pintype "passive"))
    )
    (net (code "77") (name "ADDRESS_BUS_1") (class "Default")
      (node (ref "R34") (pin "1") (pinfunction "1_1") (pintype "passive"))
      (node (ref "SV2_CREG_2") (pin "31") (pinfunction "31_31") (pintype "passive"))
      (node (ref "SV3_CREG_2") (pin "31") (pinfunction "31_31") (pintype "passive"))
      (node (ref "SV_CREG_2") (pin "31") (pinfunction "31_31") (pintype "passive"))
      (node (ref "SV_EXT_1") (pin "6") (pinfunction "6_6") (pintype "passive"))
      (node (ref "SV_XFER_1") (pin "6") (pinfunction "6_6") (pintype "passive"))
    )
    (net (code "78") (name "ADDRESS_BUS_2") (class "Default")
      (node (ref "R35") (pin "1") (pinfunction "1_1") (pintype "passive"))
      (node (ref "SV2_CREG_2") (pin "29") (pinfunction "29_29") (pintype "passive"))
      (node (ref "SV3_CREG_2") (pin "29") (pinfunction "29_29") (pintype "passive"))
      (node (ref "SV_CREG_2") (pin "29") (pinfunction "29_29") (pintype "passive"))
      (node (ref "SV_EXT_1") (pin "8") (pinfunction "8_8") (pintype "passive"))
      (node (ref "SV_XFER_1") (pin "8") (pinfunction "8_8") (pintype "passive"))
    )
    (net (code "79") (name "ADDRESS_BUS_3") (class "Default")
      (node (ref "R36") (pin "1") (pinfunction "1_1") (pintype "passive"))
      (node (ref "SV2_CREG_2") (pin "27") (pinfunction "27_27") (pintype "passive"))
      (node (ref "SV3_CREG_2") (pin "27") (pinfunction "27_27") (pintype "passive"))
      (node (ref "SV_CREG_2") (pin "27") (pinfunction "27_27") (pintype "passive"))
      (node (ref "SV_EXT_1") (pin "10") (pinfunction "10_10") (pintype "passive"))
      (node (ref "SV_XFER_1") (pin "10") (pinfunction "10_10") (pintype "passive"))
    )
    (net (code "80") (name "ADDRESS_BUS_4") (class "Default")
      (node (ref "R37") (pin "1") (pinfunction "1_1") (pintype "passive"))
      (node (ref "SV2_CREG_2") (pin "25") (pinfunction "25_25") (pintype "passive"))
      (node (ref "SV3_CREG_2") (pin "25") (pinfunction "25_25") (pintype "passive"))
      (node (ref "SV_CREG_2") (pin "25") (pinfunction "25_25") (pintype "passive"))
      (node (ref "SV_EXT_1") (pin "12") (pinfunction "12_12") (pintype "passive"))
      (node (ref "SV_XFER_1") (pin "12") (pinfunction "12_12") (pintype "passive"))
    )
    (net (code "81") (name "ADDRESS_BUS_5") (class "Default")
      (node (ref "R38") (pin "1") (pinfunction "1_1") (pintype "passive"))
      (node (ref "SV2_CREG_2") (pin "23") (pinfunction "23_23") (pintype "passive"))
      (node (ref "SV3_CREG_2") (pin "23") (pinfunction "23_23") (pintype "passive"))
      (node (ref "SV_CREG_2") (pin "23") (pinfunction "23_23") (pintype "passive"))
      (node (ref "SV_EXT_1") (pin "14") (pinfunction "14_14") (pintype "passive"))
      (node (ref "SV_XFER_1") (pin "14") (pinfunction "14_14") (pintype "passive"))
    )
    (net (code "82") (name "ADDRESS_BUS_6") (class "Default")
      (node (ref "R39") (pin "1") (pinfunction "1_1") (pintype "passive"))
      (node (ref "SV2_CREG_2") (pin "21") (pinfunction "21_21") (pintype "passive"))
      (node (ref "SV3_CREG_2") (pin "21") (pinfunction "21_21") (pintype "passive"))
      (node (ref "SV_CREG_2") (pin "21") (pinfunction "21_21") (pintype "passive"))
      (node (ref "SV_EXT_1") (pin "16") (pinfunction "16_16") (pintype "passive"))
      (node (ref "SV_XFER_1") (pin "16") (pinfunction "16_16") (pintype "passive"))
    )
    (net (code "83") (name "ADDRESS_BUS_7") (class "Default")
      (node (ref "R40") (pin "1") (pinfunction "1_1") (pintype "passive"))
      (node (ref "SV2_CREG_2") (pin "19") (pinfunction "19_19") (pintype "passive"))
      (node (ref "SV3_CREG_2") (pin "19") (pinfunction "19_19") (pintype "passive"))
      (node (ref "SV_CREG_2") (pin "19") (pinfunction "19_19") (pintype "passive"))
      (node (ref "SV_EXT_1") (pin "18") (pinfunction "18_18") (pintype "passive"))
      (node (ref "SV_XFER_1") (pin "18") (pinfunction "18_18") (pintype "passive"))
    )
    (net (code "84") (name "ADDRESS_BUS_8") (class "Default")
      (node (ref "R41") (pin "1") (pinfunction "1_1") (pintype "passive"))
      (node (ref "SV2_CREG_2") (pin "17") (pinfunction "17_17") (pintype "passive"))
      (node (ref "SV3_CREG_2") (pin "17") (pinfunction "17_17") (pintype "passive"))
      (node (ref "SV_CREG_2") (pin "17") (pinfunction "17_17") (pintype "passive"))
      (node (ref "SV_EXT_1") (pin "20") (pinfunction "20_20") (pintype "passive"))
      (node (ref "SV_XFER_1") (pin "20") (pinfunction "20_20") (pintype "passive"))
    )
    (net (code "85") (name "ADDRESS_BUS_9") (class "Default")
      (node (ref "R42") (pin "1") (pinfunction "1_1") (pintype "passive"))
      (node (ref "SV2_CREG_2") (pin "15") (pinfunction "15_15") (pintype "passive"))
      (node (ref "SV3_CREG_2") (pin "15") (pinfunction "15_15") (pintype "passive"))
      (node (ref "SV_CREG_2") (pin "15") (pinfunction "15_15") (pintype "passive"))
      (node (ref "SV_EXT_1") (pin "22") (pinfunction "22_22") (pintype "passive"))
      (node (ref "SV_XFER_1") (pin "22") (pinfunction "22_22") (pintype "passive"))
    )
    (net (code "86") (name "ADDRESS_BUS_10") (class "Default")
      (node (ref "R43") (pin "1") (pinfunction "1_1") (pintype "passive"))
      (node (ref "SV2_CREG_2") (pin "13") (pinfunction "13_13") (pintype "passive"))
      (node (ref "SV3_CREG_2") (pin "13") (pinfunction "13_13") (pintype "passive"))
      (node (ref "SV_CREG_2") (pin "13") (pinfunction "13_13") (pintype "passive"))
      (node (ref "SV_EXT_1") (pin "24") (pinfunction "24_24") (pintype "passive"))
      (node (ref "SV_XFER_1") (pin "24") (pinfunction "24_24") (pintype "passive"))
    )
    (net (code "87") (name "ADDRESS_BUS_11") (class "Default")
      (node (ref "R44") (pin "1") (pinfunction "1_1") (pintype "passive"))
      (node (ref "SV2_CREG_2") (pin "11") (pinfunction "11_11") (pintype "passive"))
      (node (ref "SV3_CREG_2") (pin "11") (pinfunction "11_11") (pintype "passive"))
      (node (ref "SV_CREG_2") (pin "11") (pinfunction "11_11") (pintype "passive"))
      (node (ref "SV_EXT_1") (pin "26") (pinfunction "26_26") (pintype "passive"))
      (node (ref "SV_XFER_1") (pin "26") (pinfunction "26_26") (pintype "passive"))
    )
    (net (code "88") (name "ADDRESS_BUS_12") (class "Default")
      (node (ref "R45") (pin "1") (pinfunction "1_1") (pintype "passive"))
      (node (ref "SV2_CREG_2") (pin "9") (pinfunction "9_9") (pintype "passive"))
      (node (ref "SV3_CREG_2") (pin "9") (pinfunction "9_9") (pintype "passive"))
      (node (ref "SV_CREG_2") (pin "9") (pinfunction "9_9") (pintype "passive"))
      (node (ref "SV_EXT_1") (pin "28") (pinfunction "28_28") (pintype "passive"))
      (node (ref "SV_XFER_1") (pin "28") (pinfunction "28_28") (pintype "passive"))
    )
    (net (code "89") (name "ADDRESS_BUS_13") (class "Default")
      (node (ref "R46") (pin "1") (pinfunction "1_1") (pintype "passive"))
      (node (ref "SV2_CREG_2") (pin "7") (pinfunction "7_7") (pintype "passive"))
      (node (ref "SV3_CREG_2") (pin "7") (pinfunction "7_7") (pintype "passive"))
      (node (ref "SV_CREG_2") (pin "7") (pinfunction "7_7") (pintype "passive"))
      (node (ref "SV_EXT_1") (pin "30") (pinfunction "30_30") (pintype "passive"))
      (node (ref "SV_XFER_1") (pin "30") (pinfunction "30_30") (pintype "passive"))
    )
    (net (code "90") (name "ADDRESS_BUS_14") (class "Default")
      (node (ref "R47") (pin "1") (pinfunction "1_1") (pintype "passive"))
      (node (ref "SV2_CREG_2") (pin "5") (pinfunction "5_5") (pintype "passive"))
      (node (ref "SV3_CREG_2") (pin "5") (pinfunction "5_5") (pintype "passive"))
      (node (ref "SV_CREG_2") (pin "5") (pinfunction "5_5") (pintype "passive"))
      (node (ref "SV_EXT_1") (pin "32") (pinfunction "32_32") (pintype "passive"))
      (node (ref "SV_XFER_1") (pin "32") (pinfunction "32_32") (pintype "passive"))
    )
    (net (code "91") (name "ADDRESS_BUS_15") (class "Default")
      (node (ref "R48") (pin "1") (pinfunction "1_1") (pintype "passive"))
      (node (ref "SV2_CREG_2") (pin "3") (pinfunction "3_3") (pintype "passive"))
      (node (ref "SV3_CREG_2") (pin "3") (pinfunction "3_3") (pintype "passive"))
      (node (ref "SV_CREG_2") (pin "3") (pinfunction "3_3") (pintype "passive"))
      (node (ref "SV_EXT_1") (pin "34") (pinfunction "34_34") (pintype "passive"))
      (node (ref "SV_XFER_1") (pin "34") (pinfunction "34_34") (pintype "passive"))
    )
    (net (code "92") (name "ALU_LEFT_BUS_0") (class "Default")
      (node (ref "R9") (pin "1") (pinfunction "1_1") (pintype "passive"))
      (node (ref "SV1_GPR_1") (pin "17") (pinfunction "17_17") (pintype "passive"))
      (node (ref "SV2_GPR_1") (pin "17") (pinfunction "17_17") (pintype "passive"))
      (node (ref "SV3_GPR_1") (pin "17") (pinfunction "17_17") (pintype "passive"))
      (node (ref "SV4_GPR_1") (pin "17") (pinfunction "17_17") (pintype "passive"))
      (node (ref "SV5_GPR_1") (pin "17") (pinfunction "17_17") (pintype "passive"))
      (node (ref "SV_EXT_2") (pin "4") (pinfunction "4_4") (pintype "passive"))
    )
    (net (code "93") (name "ALU_LEFT_BUS_1") (class "Default")
      (node (ref "R10") (pin "1") (pinfunction "1_1") (pintype "passive"))
      (node (ref "SV1_GPR_1") (pin "15") (pinfunction "15_15") (pintype "passive"))
      (node (ref "SV2_GPR_1") (pin "15") (pinfunction "15_15") (pintype "passive"))
      (node (ref "SV3_GPR_1") (pin "15") (pinfunction "15_15") (pintype "passive"))
      (node (ref "SV4_GPR_1") (pin "15") (pinfunction "15_15") (pintype "passive"))
      (node (ref "SV5_GPR_1") (pin "15") (pinfunction "15_15") (pintype "passive"))
      (node (ref "SV_EXT_2") (pin "6") (pinfunction "6_6") (pintype "passive"))
    )
    (net (code "94") (name "ALU_LEFT_BUS_2") (class "Default")
      (node (ref "R11") (pin "1") (pinfunction "1_1") (pintype "passive"))
      (node (ref "SV1_GPR_1") (pin "13") (pinfunction "13_13") (pintype "passive"))
      (node (ref "SV2_GPR_1") (pin "13") (pinfunction "13_13") (pintype "passive"))
      (node (ref "SV3_GPR_1") (pin "13") (pinfunction "13_13") (pintype "passive"))
      (node (ref "SV4_GPR_1") (pin "13") (pinfunction "13_13") (pintype "passive"))
      (node (ref "SV5_GPR_1") (pin "13") (pinfunction "13_13") (pintype "passive"))
      (node (ref "SV_EXT_2") (pin "8") (pinfunction "8_8") (pintype "passive"))
    )
    (net (code "95") (name "ALU_LEFT_BUS_3") (class "Default")
      (node (ref "R12") (pin "1") (pinfunction "1_1") (pintype "passive"))
      (node (ref "SV1_GPR_1") (pin "11") (pinfunction "11_11") (pintype "passive"))
      (node (ref "SV2_GPR_1") (pin "11") (pinfunction "11_11") (pintype "passive"))
      (node (ref "SV3_GPR_1") (pin "11") (pinfunction "11_11") (pintype "passive"))
      (node (ref "SV4_GPR_1") (pin "11") (pinfunction "11_11") (pintype "passive"))
      (node (ref "SV5_GPR_1") (pin "11") (pinfunction "11_11") (pintype "passive"))
      (node (ref "SV_EXT_2") (pin "10") (pinfunction "10_10") (pintype "passive"))
    )
    (net (code "96") (name "ALU_LEFT_BUS_4") (class "Default")
      (node (ref "R13") (pin "1") (pinfunction "1_1") (pintype "passive"))
      (node (ref "SV1_GPR_1") (pin "9") (pinfunction "9_9") (pintype "passive"))
      (node (ref "SV2_GPR_1") (pin "9") (pinfunction "9_9") (pintype "passive"))
      (node (ref "SV3_GPR_1") (pin "9") (pinfunction "9_9") (pintype "passive"))
      (node (ref "SV4_GPR_1") (pin "9") (pinfunction "9_9") (pintype "passive"))
      (node (ref "SV5_GPR_1") (pin "9") (pinfunction "9_9") (pintype "passive"))
      (node (ref "SV_EXT_2") (pin "12") (pinfunction "12_12") (pintype "passive"))
    )
    (net (code "97") (name "ALU_LEFT_BUS_5") (class "Default")
      (node (ref "R14") (pin "1") (pinfunction "1_1") (pintype "passive"))
      (node (ref "SV1_GPR_1") (pin "7") (pinfunction "7_7") (pintype "passive"))
      (node (ref "SV2_GPR_1") (pin "7") (pinfunction "7_7") (pintype "passive"))
      (node (ref "SV3_GPR_1") (pin "7") (pinfunction "7_7") (pintype "passive"))
      (node (ref "SV4_GPR_1") (pin "7") (pinfunction "7_7") (pintype "passive"))
      (node (ref "SV5_GPR_1") (pin "7") (pinfunction "7_7") (pintype "passive"))
      (node (ref "SV_EXT_2") (pin "14") (pinfunction "14_14") (pintype "passive"))
    )
    (net (code "98") (name "ALU_LEFT_BUS_6") (class "Default")
      (node (ref "R15") (pin "1") (pinfunction "1_1") (pintype "passive"))
      (node (ref "SV1_GPR_1") (pin "5") (pinfunction "5_5") (pintype "passive"))
      (node (ref "SV2_GPR_1") (pin "5") (pinfunction "5_5") (pintype "passive"))
      (node (ref "SV3_GPR_1") (pin "5") (pinfunction "5_5") (pintype "passive"))
      (node (ref "SV4_GPR_1") (pin "5") (pinfunction "5_5") (pintype "passive"))
      (node (ref "SV5_GPR_1") (pin "5") (pinfunction "5_5") (pintype "passive"))
      (node (ref "SV_EXT_2") (pin "16") (pinfunction "16_16") (pintype "passive"))
    )
    (net (code "99") (name "ALU_LEFT_BUS_7") (class "Default")
      (node (ref "R16") (pin "1") (pinfunction "1_1") (pintype "passive"))
      (node (ref "SV1_GPR_1") (pin "3") (pinfunction "3_3") (pintype "passive"))
      (node (ref "SV2_GPR_1") (pin "3") (pinfunction "3_3") (pintype "passive"))
      (node (ref "SV3_GPR_1") (pin "3") (pinfunction "3_3") (pintype "passive"))
      (node (ref "SV4_GPR_1") (pin "3") (pinfunction "3_3") (pintype "passive"))
      (node (ref "SV5_GPR_1") (pin "3") (pinfunction "3_3") (pintype "passive"))
      (node (ref "SV_EXT_2") (pin "18") (pinfunction "18_18") (pintype "passive"))
    )
    (net (code "100") (name "ALU_RIGHT_BUS_0") (class "Default")
      (node (ref "R8") (pin "1") (pinfunction "1_1") (pintype "passive"))
      (node (ref "SV1_GPR_1") (pin "34") (pinfunction "34_34") (pintype "passive"))
      (node (ref "SV2_GPR_1") (pin "34") (pinfunction "34_34") (pintype "passive"))
      (node (ref "SV3_GPR_1") (pin "34") (pinfunction "34_34") (pintype "passive"))
      (node (ref "SV4_GPR_1") (pin "34") (pinfunction "34_34") (pintype "passive"))
      (node (ref "SV5_GPR_1") (pin "34") (pinfunction "34_34") (pintype "passive"))
      (node (ref "SV_EXT_2") (pin "3") (pinfunction "3_3") (pintype "passive"))
    )
    (net (code "101") (name "ALU_RIGHT_BUS_1") (class "Default")
      (node (ref "R7") (pin "1") (pinfunction "1_1") (pintype "passive"))
      (node (ref "SV1_GPR_1") (pin "32") (pinfunction "32_32") (pintype "passive"))
      (node (ref "SV2_GPR_1") (pin "32") (pinfunction "32_32") (pintype "passive"))
      (node (ref "SV3_GPR_1") (pin "32") (pinfunction "32_32") (pintype "passive"))
      (node (ref "SV4_GPR_1") (pin "32") (pinfunction "32_32") (pintype "passive"))
      (node (ref "SV5_GPR_1") (pin "32") (pinfunction "32_32") (pintype "passive"))
      (node (ref "SV_EXT_2") (pin "5") (pinfunction "5_5") (pintype "passive"))
    )
    (net (code "102") (name "ALU_RIGHT_BUS_2") (class "Default")
      (node (ref "R6") (pin "1") (pinfunction "1_1") (pintype "passive"))
      (node (ref "SV1_GPR_1") (pin "30") (pinfunction "30_30") (pintype "passive"))
      (node (ref "SV2_GPR_1") (pin "30") (pinfunction "30_30") (pintype "passive"))
      (node (ref "SV3_GPR_1") (pin "30") (pinfunction "30_30") (pintype "passive"))
      (node (ref "SV4_GPR_1") (pin "30") (pinfunction "30_30") (pintype "passive"))
      (node (ref "SV5_GPR_1") (pin "30") (pinfunction "30_30") (pintype "passive"))
      (node (ref "SV_EXT_2") (pin "7") (pinfunction "7_7") (pintype "passive"))
    )
    (net (code "103") (name "ALU_RIGHT_BUS_3") (class "Default")
      (node (ref "R5") (pin "1") (pinfunction "1_1") (pintype "passive"))
      (node (ref "SV1_GPR_1") (pin "28") (pinfunction "28_28") (pintype "passive"))
      (node (ref "SV2_GPR_1") (pin "28") (pinfunction "28_28") (pintype "passive"))
      (node (ref "SV3_GPR_1") (pin "28") (pinfunction "28_28") (pintype "passive"))
      (node (ref "SV4_GPR_1") (pin "28") (pinfunction "28_28") (pintype "passive"))
      (node (ref "SV5_GPR_1") (pin "28") (pinfunction "28_28") (pintype "passive"))
      (node (ref "SV_EXT_2") (pin "9") (pinfunction "9_9") (pintype "passive"))
    )
    (net (code "104") (name "ALU_RIGHT_BUS_4") (class "Default")
      (node (ref "R4") (pin "1") (pinfunction "1_1") (pintype "passive"))
      (node (ref "SV1_GPR_1") (pin "26") (pinfunction "26_26") (pintype "passive"))
      (node (ref "SV2_GPR_1") (pin "26") (pinfunction "26_26") (pintype "passive"))
      (node (ref "SV3_GPR_1") (pin "26") (pinfunction "26_26") (pintype "passive"))
      (node (ref "SV4_GPR_1") (pin "26") (pinfunction "26_26") (pintype "passive"))
      (node (ref "SV5_GPR_1") (pin "26") (pinfunction "26_26") (pintype "passive"))
      (node (ref "SV_EXT_2") (pin "11") (pinfunction "11_11") (pintype "passive"))
    )
    (net (code "105") (name "ALU_RIGHT_BUS_5") (class "Default")
      (node (ref "R3") (pin "1") (pinfunction "1_1") (pintype "passive"))
      (node (ref "SV1_GPR_1") (pin "24") (pinfunction "24_24") (pintype "passive"))
      (node (ref "SV2_GPR_1") (pin "24") (pinfunction "24_24") (pintype "passive"))
      (node (ref "SV3_GPR_1") (pin "24") (pinfunction "24_24") (pintype "passive"))
      (node (ref "SV4_GPR_1") (pin "24") (pinfunction "24_24") (pintype "passive"))
      (node (ref "SV5_GPR_1") (pin "24") (pinfunction "24_24") (pintype "passive"))
      (node (ref "SV_EXT_2") (pin "13") (pinfunction "13_13") (pintype "passive"))
    )
    (net (code "106") (name "ALU_RIGHT_BUS_6") (class "Default")
      (node (ref "R2") (pin "1") (pinfunction "1_1") (pintype "passive"))
      (node (ref "SV1_GPR_1") (pin "22") (pinfunction "22_22") (pintype "passive"))
      (node (ref "SV2_GPR_1") (pin "22") (pinfunction "22_22") (pintype "passive"))
      (node (ref "SV3_GPR_1") (pin "22") (pinfunction "22_22") (pintype "passive"))
      (node (ref "SV4_GPR_1") (pin "22") (pinfunction "22_22") (pintype "passive"))
      (node (ref "SV5_GPR_1") (pin "22") (pinfunction "22_22") (pintype "passive"))
      (node (ref "SV_EXT_2") (pin "15") (pinfunction "15_15") (pintype "passive"))
    )
    (net (code "107") (name "ALU_RIGHT_BUS_7") (class "Default")
      (node (ref "R1") (pin "1") (pinfunction "1_1") (pintype "passive"))
      (node (ref "SV1_GPR_1") (pin "20") (pinfunction "20_20") (pintype "passive"))
      (node (ref "SV2_GPR_1") (pin "20") (pinfunction "20_20") (pintype "passive"))
      (node (ref "SV3_GPR_1") (pin "20") (pinfunction "20_20") (pintype "passive"))
      (node (ref "SV4_GPR_1") (pin "20") (pinfunction "20_20") (pintype "passive"))
      (node (ref "SV5_GPR_1") (pin "20") (pinfunction "20_20") (pintype "passive"))
      (node (ref "SV_EXT_2") (pin "17") (pinfunction "17_17") (pintype "passive"))
    )
    (net (code "108") (name "BUS_CTRL1_REG_A_1") (class "Default")
      (node (ref "SV_BUS_CONTROL_1") (pin "34") (pinfunction "34_34") (pintype "passive"))
      (node (ref "SV_EXT_3") (pin "34") (pinfunction "34_34") (pintype "passive"))
    )
    (net (code "109") (name "BUS_CTRL2_REG_A_2") (class "Default")
      (node (ref "SV_BUS_CONTROL_1") (pin "32") (pinfunction "32_32") (pintype "passive"))
      (node (ref "SV_EXT_3") (pin "32") (pinfunction "32_32") (pintype "passive"))
    )
    (net (code "110") (name "BUS_CTRL3_REG_A_3") (class "Default")
      (node (ref "SV_BUS_CONTROL_1") (pin "30") (pinfunction "30_30") (pintype "passive"))
      (node (ref "SV_EXT_3") (pin "30") (pinfunction "30_30") (pintype "passive"))
    )
    (net (code "111") (name "BUS_CTRL4_REG_A_4") (class "Default")
      (node (ref "SV_BUS_CONTROL_1") (pin "28") (pinfunction "28_28") (pintype "passive"))
      (node (ref "SV_EXT_3") (pin "28") (pinfunction "28_28") (pintype "passive"))
    )
    (net (code "112") (name "BUS_CTRL5_REG_L_1") (class "Default")
      (node (ref "SV_BUS_CONTROL_1") (pin "26") (pinfunction "26_26") (pintype "passive"))
      (node (ref "SV_EXT_3") (pin "26") (pinfunction "26_26") (pintype "passive"))
    )
    (net (code "113") (name "BUS_CTRL6_REG_L_2") (class "Default")
      (node (ref "SV_BUS_CONTROL_1") (pin "24") (pinfunction "24_24") (pintype "passive"))
      (node (ref "SV_EXT_3") (pin "24") (pinfunction "24_24") (pintype "passive"))
    )
    (net (code "114") (name "BUS_CTRL7_REG_L_3") (class "Default")
      (node (ref "SV_BUS_CONTROL_1") (pin "22") (pinfunction "22_22") (pintype "passive"))
      (node (ref "SV_EXT_3") (pin "22") (pinfunction "22_22") (pintype "passive"))
    )
    (net (code "115") (name "BUS_CTRL8_REG_L_4") (class "Default")
      (node (ref "SV_BUS_CONTROL_1") (pin "20") (pinfunction "20_20") (pintype "passive"))
      (node (ref "SV_EXT_3") (pin "20") (pinfunction "20_20") (pintype "passive"))
    )
    (net (code "116") (name "BUS_CTRL9_16REG_A_ADDR_1") (class "Default")
      (node (ref "SV_BUS_CONTROL_1") (pin "18") (pinfunction "18_18") (pintype "passive"))
      (node (ref "SV_EXT_3") (pin "18") (pinfunction "18_18") (pintype "passive"))
    )
    (net (code "117") (name "BUS_CTRL10_16REG_A_ADDR_2") (class "Default")
      (node (ref "SV_BUS_CONTROL_1") (pin "16") (pinfunction "16_16") (pintype "passive"))
      (node (ref "SV_EXT_3") (pin "16") (pinfunction "16_16") (pintype "passive"))
    )
    (net (code "118") (name "BUS_CTRL11_16REG_A_ADDR_3") (class "Default")
      (node (ref "SV_BUS_CONTROL_1") (pin "14") (pinfunction "14_14") (pintype "passive"))
      (node (ref "SV_EXT_3") (pin "14") (pinfunction "14_14") (pintype "passive"))
    )
    (net (code "119") (name "BUS_CTRL12_CREG_INC_1") (class "Default")
      (node (ref "SV_BUS_CONTROL_1") (pin "12") (pinfunction "12_12") (pintype "passive"))
      (node (ref "SV_EXT_3") (pin "12") (pinfunction "12_12") (pintype "passive"))
    )
    (net (code "120") (name "BUS_CTRL13_CREG_INC_2") (class "Default")
      (node (ref "SV_BUS_CONTROL_1") (pin "10") (pinfunction "10_10") (pintype "passive"))
      (node (ref "SV_EXT_3") (pin "10") (pinfunction "10_10") (pintype "passive"))
    )
    (net (code "121") (name "BUS_CTRL14_CREG_DEC_1") (class "Default")
      (node (ref "SV_BUS_CONTROL_1") (pin "8") (pinfunction "8_8") (pintype "passive"))
      (node (ref "SV_EXT_3") (pin "8") (pinfunction "8_8") (pintype "passive"))
    )
    (net (code "122") (name "BUS_CTRL15_CREG_DEC_2") (class "Default")
      (node (ref "SV_BUS_CONTROL_1") (pin "6") (pinfunction "6_6") (pintype "passive"))
      (node (ref "SV_EXT_3") (pin "6") (pinfunction "6_6") (pintype "passive"))
    )
    (net (code "123") (name "BUS_CTRL17_GPR_A_ALU_R_1") (class "Default")
      (node (ref "SV_BUS_CONTROL_1") (pin "29") (pinfunction "29_29") (pintype "passive"))
      (node (ref "SV_EXT_3") (pin "4") (pinfunction "4_4") (pintype "passive"))
    )
    (net (code "124") (name "BUS_CTRL18_GPR_A_ALU_R_2") (class "Default")
      (node (ref "SV_BUS_CONTROL_1") (pin "31") (pinfunction "31_31") (pintype "passive"))
      (node (ref "SV_EXT_3") (pin "33") (pinfunction "33_33") (pintype "passive"))
    )
    (net (code "125") (name "BUS_CTRL19_GPR_A_ALU_R_3") (class "Default")
      (node (ref "SV_BUS_CONTROL_1") (pin "33") (pinfunction "33_33") (pintype "passive"))
      (node (ref "SV_EXT_3") (pin "31") (pinfunction "31_31") (pintype "passive"))
    )
    (net (code "126") (name "BUS_CTRL20_GPR_A_ALU_L_1") (class "Default")
      (node (ref "SV_BUS_CONTROL_1") (pin "23") (pinfunction "23_23") (pintype "passive"))
      (node (ref "SV_EXT_3") (pin "29") (pinfunction "29_29") (pintype "passive"))
    )
    (net (code "127") (name "BUS_CTRL21_GPR_A_ALU_L_2") (class "Default")
      (node (ref "SV_BUS_CONTROL_1") (pin "25") (pinfunction "25_25") (pintype "passive"))
      (node (ref "SV_EXT_3") (pin "27") (pinfunction "27_27") (pintype "passive"))
    )
    (net (code "128") (name "BUS_CTRL22_GPR_A_ALU_L_3") (class "Default")
      (node (ref "SV_BUS_CONTROL_1") (pin "27") (pinfunction "27_27") (pintype "passive"))
      (node (ref "SV_EXT_3") (pin "25") (pinfunction "25_25") (pintype "passive"))
    )
    (net (code "129") (name "CLK") (class "Default")
      (node (ref "SV1_GPR_1") (pin "18") (pinfunction "18_18") (pintype "passive"))
      (node (ref "SV2_CREG_1") (pin "34") (pinfunction "34_34") (pintype "passive"))
      (node (ref "SV2_GPR_1") (pin "18") (pinfunction "18_18") (pintype "passive"))
      (node (ref "SV3_CREG_1") (pin "34") (pinfunction "34_34") (pintype "passive"))
      (node (ref "SV3_GPR_1") (pin "18") (pinfunction "18_18") (pintype "passive"))
      (node (ref "SV4_GPR_1") (pin "18") (pinfunction "18_18") (pintype "passive"))
      (node (ref "SV5_GPR_1") (pin "18") (pinfunction "18_18") (pintype "passive"))
      (node (ref "SV_CONST_REG_1") (pin "18") (pinfunction "18_18") (pintype "passive"))
      (node (ref "SV_CREG_1") (pin "34") (pinfunction "34_34") (pintype "passive"))
      (node (ref "SV_EXT_3") (pin "5") (pinfunction "5_5") (pintype "passive"))
      (node (ref "SV_XFER_2") (pin "4") (pinfunction "4_4") (pintype "passive"))
    )
    (net (code "130") (name "GND") (class "Default")
      (node (ref "C1") (pin "-") (pinfunction "-_-") (pintype "passive"))
      (node (ref "C2") (pin "-") (pinfunction "-_-") (pintype "passive"))
      (node (ref "R1") (pin "2") (pinfunction "2_2") (pintype "passive"))
      (node (ref "R10") (pin "2") (pinfunction "2_2") (pintype "passive"))
      (node (ref "R11") (pin "2") (pinfunction "2_2") (pintype "passive"))
      (node (ref "R12") (pin "2") (pinfunction "2_2") (pintype "passive"))
      (node (ref "R13") (pin "2") (pinfunction "2_2") (pintype "passive"))
      (node (ref "R14") (pin "2") (pinfunction "2_2") (pintype "passive"))
      (node (ref "R15") (pin "2") (pinfunction "2_2") (pintype "passive"))
      (node (ref "R16") (pin "2") (pinfunction "2_2") (pintype "passive"))
      (node (ref "R17") (pin "2") (pinfunction "2_2") (pintype "passive"))
      (node (ref "R18") (pin "2") (pinfunction "2_2") (pintype "passive"))
      (node (ref "R19") (pin "2") (pinfunction "2_2") (pintype "passive"))
      (node (ref "R2") (pin "2") (pinfunction "2_2") (pintype "passive"))
      (node (ref "R20") (pin "2") (pinfunction "2_2") (pintype "passive"))
      (node (ref "R21") (pin "2") (pinfunction "2_2") (pintype "passive"))
      (node (ref "R22") (pin "2") (pinfunction "2_2") (pintype "passive"))
      (node (ref "R23") (pin "2") (pinfunction "2_2") (pintype "passive"))
      (node (ref "R24") (pin "2") (pinfunction "2_2") (pintype "passive"))
      (node (ref "R25") (pin "2") (pinfunction "2_2") (pintype "passive"))
      (node (ref "R26") (pin "2") (pinfunction "2_2") (pintype "passive"))
      (node (ref "R27") (pin "2") (pinfunction "2_2") (pintype "passive"))
      (node (ref "R28") (pin "2") (pinfunction "2_2") (pintype "passive"))
      (node (ref "R29") (pin "2") (pinfunction "2_2") (pintype "passive"))
      (node (ref "R3") (pin "2") (pinfunction "2_2") (pintype "passive"))
      (node (ref "R30") (pin "2") (pinfunction "2_2") (pintype "passive"))
      (node (ref "R31") (pin "2") (pinfunction "2_2") (pintype "passive"))
      (node (ref "R32") (pin "2") (pinfunction "2_2") (pintype "passive"))
      (node (ref "R33") (pin "2") (pinfunction "2_2") (pintype "passive"))
      (node (ref "R34") (pin "2") (pinfunction "2_2") (pintype "passive"))
      (node (ref "R35") (pin "2") (pinfunction "2_2") (pintype "passive"))
      (node (ref "R36") (pin "2") (pinfunction "2_2") (pintype "passive"))
      (node (ref "R37") (pin "2") (pinfunction "2_2") (pintype "passive"))
      (node (ref "R38") (pin "2") (pinfunction "2_2") (pintype "passive"))
      (node (ref "R39") (pin "2") (pinfunction "2_2") (pintype "passive"))
      (node (ref "R4") (pin "2") (pinfunction "2_2") (pintype "passive"))
      (node (ref "R40") (pin "2") (pinfunction "2_2") (pintype "passive"))
      (node (ref "R41") (pin "2") (pinfunction "2_2") (pintype "passive"))
      (node (ref "R42") (pin "2") (pinfunction "2_2") (pintype "passive"))
      (node (ref "R43") (pin "2") (pinfunction "2_2") (pintype "passive"))
      (node (ref "R44") (pin "2") (pinfunction "2_2") (pintype "passive"))
      (node (ref "R45") (pin "2") (pinfunction "2_2") (pintype "passive"))
      (node (ref "R46") (pin "2") (pinfunction "2_2") (pintype "passive"))
      (node (ref "R47") (pin "2") (pinfunction "2_2") (pintype "passive"))
      (node (ref "R48") (pin "2") (pinfunction "2_2") (pintype "passive"))
      (node (ref "R49") (pin "2") (pinfunction "2_2") (pintype "passive"))
      (node (ref "R5") (pin "2") (pinfunction "2_2") (pintype "passive"))
      (node (ref "R50") (pin "2") (pinfunction "2_2") (pintype "passive"))
      (node (ref "R51") (pin "2") (pinfunction "2_2") (pintype "passive"))
      (node (ref "R52") (pin "2") (pinfunction "2_2") (pintype "passive"))
      (node (ref "R53") (pin "2") (pinfunction "2_2") (pintype "passive"))
      (node (ref "R54") (pin "2") (pinfunction "2_2") (pintype "passive"))
      (node (ref "R55") (pin "2") (pinfunction "2_2") (pintype "passive"))
      (node (ref "R56") (pin "2") (pinfunction "2_2") (pintype "passive"))
      (node (ref "R57") (pin "2") (pinfunction "2_2") (pintype "passive"))
      (node (ref "R58") (pin "2") (pinfunction "2_2") (pintype "passive"))
      (node (ref "R59") (pin "2") (pinfunction "2_2") (pintype "passive"))
      (node (ref "R6") (pin "2") (pinfunction "2_2") (pintype "passive"))
      (node (ref "R60") (pin "2") (pinfunction "2_2") (pintype "passive"))
      (node (ref "R61") (pin "2") (pinfunction "2_2") (pintype "passive"))
      (node (ref "R62") (pin "2") (pinfunction "2_2") (pintype "passive"))
      (node (ref "R63") (pin "2") (pinfunction "2_2") (pintype "passive"))
      (node (ref "R64") (pin "2") (pinfunction "2_2") (pintype "passive"))
      (node (ref "R7") (pin "2") (pinfunction "2_2") (pintype "passive"))
      (node (ref "R8") (pin "2") (pinfunction "2_2") (pintype "passive"))
      (node (ref "R9") (pin "2") (pinfunction "2_2") (pintype "passive"))
      (node (ref "SV1_GPR_1") (pin "2") (pinfunction "2_2") (pintype "passive"))
      (node (ref "SV1_GPR_1") (pin "35") (pinfunction "35_35") (pintype "passive"))
      (node (ref "SV1_GPR_2") (pin "17") (pinfunction "17_17") (pintype "passive"))
      (node (ref "SV1_GPR_2") (pin "19") (pinfunction "19_19") (pintype "passive"))
      (node (ref "SV1_GPR_2") (pin "2") (pinfunction "2_2") (pintype "passive"))
      (node (ref "SV1_GPR_2") (pin "35") (pinfunction "35_35") (pintype "passive"))
      (node (ref "SV2_CREG_1") (pin "2") (pinfunction "2_2") (pintype "passive"))
      (node (ref "SV2_CREG_1") (pin "35") (pinfunction "35_35") (pintype "passive"))
      (node (ref "SV2_CREG_2") (pin "2") (pinfunction "2_2") (pintype "passive"))
      (node (ref "SV2_CREG_2") (pin "35") (pinfunction "35_35") (pintype "passive"))
      (node (ref "SV2_GPR_1") (pin "2") (pinfunction "2_2") (pintype "passive"))
      (node (ref "SV2_GPR_1") (pin "35") (pinfunction "35_35") (pintype "passive"))
      (node (ref "SV2_GPR_2") (pin "17") (pinfunction "17_17") (pintype "passive"))
      (node (ref "SV2_GPR_2") (pin "19") (pinfunction "19_19") (pintype "passive"))
      (node (ref "SV2_GPR_2") (pin "2") (pinfunction "2_2") (pintype "passive"))
      (node (ref "SV2_GPR_2") (pin "35") (pinfunction "35_35") (pintype "passive"))
      (node (ref "SV3_CREG_1") (pin "2") (pinfunction "2_2") (pintype "passive"))
      (node (ref "SV3_CREG_1") (pin "35") (pinfunction "35_35") (pintype "passive"))
      (node (ref "SV3_CREG_2") (pin "2") (pinfunction "2_2") (pintype "passive"))
      (node (ref "SV3_CREG_2") (pin "35") (pinfunction "35_35") (pintype "passive"))
      (node (ref "SV3_GPR_1") (pin "2") (pinfunction "2_2") (pintype "passive"))
      (node (ref "SV3_GPR_1") (pin "35") (pinfunction "35_35") (pintype "passive"))
      (node (ref "SV3_GPR_2") (pin "17") (pinfunction "17_17") (pintype "passive"))
      (node (ref "SV3_GPR_2") (pin "19") (pinfunction "19_19") (pintype "passive"))
      (node (ref "SV3_GPR_2") (pin "2") (pinfunction "2_2") (pintype "passive"))
      (node (ref "SV3_GPR_2") (pin "35") (pinfunction "35_35") (pintype "passive"))
      (node (ref "SV4_GPR_1") (pin "2") (pinfunction "2_2") (pintype "passive"))
      (node (ref "SV4_GPR_1") (pin "35") (pinfunction "35_35") (pintype "passive"))
      (node (ref "SV4_GPR_2") (pin "17") (pinfunction "17_17") (pintype "passive"))
      (node (ref "SV4_GPR_2") (pin "19") (pinfunction "19_19") (pintype "passive"))
      (node (ref "SV4_GPR_2") (pin "2") (pinfunction "2_2") (pintype "passive"))
      (node (ref "SV4_GPR_2") (pin "35") (pinfunction "35_35") (pintype "passive"))
      (node (ref "SV5_GPR_1") (pin "2") (pinfunction "2_2") (pintype "passive"))
      (node (ref "SV5_GPR_1") (pin "35") (pinfunction "35_35") (pintype "passive"))
      (node (ref "SV5_GPR_2") (pin "17") (pinfunction "17_17") (pintype "passive"))
      (node (ref "SV5_GPR_2") (pin "19") (pinfunction "19_19") (pintype "passive"))
      (node (ref "SV5_GPR_2") (pin "2") (pinfunction "2_2") (pintype "passive"))
      (node (ref "SV5_GPR_2") (pin "35") (pinfunction "35_35") (pintype "passive"))
      (node (ref "SV_BUS_CONTROL_1") (pin "2") (pinfunction "2_2") (pintype "passive"))
      (node (ref "SV_BUS_CONTROL_1") (pin "35") (pinfunction "35_35") (pintype "passive"))
      (node (ref "SV_BUS_CONTROL_2") (pin "2") (pinfunction "2_2") (pintype "passive"))
      (node (ref "SV_BUS_CONTROL_2") (pin "35") (pinfunction "35_35") (pintype "passive"))
      (node (ref "SV_BUS_CONTROL_3") (pin "2") (pinfunction "2_2") (pintype "passive"))
      (node (ref "SV_BUS_CONTROL_3") (pin "35") (pinfunction "35_35") (pintype "passive"))
      (node (ref "SV_BUS_CONTROL_4") (pin "2") (pinfunction "2_2") (pintype "passive"))
      (node (ref "SV_BUS_CONTROL_4") (pin "35") (pinfunction "35_35") (pintype "passive"))
      (node (ref "SV_CONST_REG_1") (pin "2") (pinfunction "2_2") (pintype "passive"))
      (node (ref "SV_CONST_REG_1") (pin "35") (pinfunction "35_35") (pintype "passive"))
      (node (ref "SV_CONST_REG_2") (pin "17") (pinfunction "17_17") (pintype "passive"))
      (node (ref "SV_CONST_REG_2") (pin "19") (pinfunction "19_19") (pintype "passive"))
      (node (ref "SV_CONST_REG_2") (pin "2") (pinfunction "2_2") (pintype "passive"))
      (node (ref "SV_CONST_REG_2") (pin "35") (pinfunction "35_35") (pintype "passive"))
      (node (ref "SV_CREG_1") (pin "2") (pinfunction "2_2") (pintype "passive"))
      (node (ref "SV_CREG_1") (pin "35") (pinfunction "35_35") (pintype "passive"))
      (node (ref "SV_CREG_2") (pin "2") (pinfunction "2_2") (pintype "passive"))
      (node (ref "SV_CREG_2") (pin "35") (pinfunction "35_35") (pintype "passive"))
      (node (ref "SV_EXT_1") (pin "2") (pinfunction "2_2") (pintype "passive"))
      (node (ref "SV_EXT_1") (pin "35") (pinfunction "35_35") (pintype "passive"))
      (node (ref "SV_EXT_2") (pin "2") (pinfunction "2_2") (pintype "passive"))
      (node (ref "SV_EXT_2") (pin "35") (pinfunction "35_35") (pintype "passive"))
      (node (ref "SV_EXT_3") (pin "2") (pinfunction "2_2") (pintype "passive"))
      (node (ref "SV_EXT_3") (pin "35") (pinfunction "35_35") (pintype "passive"))
      (node (ref "SV_EXT_4") (pin "2") (pinfunction "2_2") (pintype "passive"))
      (node (ref "SV_EXT_4") (pin "35") (pinfunction "35_35") (pintype "passive"))
      (node (ref "SV_XFER_1") (pin "2") (pinfunction "2_2") (pintype "passive"))
      (node (ref "SV_XFER_1") (pin "35") (pinfunction "35_35") (pintype "passive"))
      (node (ref "SV_XFER_2") (pin "2") (pinfunction "2_2") (pintype "passive"))
      (node (ref "SV_XFER_2") (pin "35") (pinfunction "35_35") (pintype "passive"))
      (node (ref "SV_XFER_3") (pin "2") (pinfunction "2_2") (pintype "passive"))
      (node (ref "SV_XFER_3") (pin "35") (pinfunction "35_35") (pintype "passive"))
      (node (ref "SV_XFER_4") (pin "2") (pinfunction "2_2") (pintype "passive"))
      (node (ref "SV_XFER_4") (pin "35") (pinfunction "35_35") (pintype "passive"))
    )
    (net (code "131") (name "MAIN_BUS_0") (class "Default")
      (node (ref "R17") (pin "1") (pinfunction "1_1") (pintype "passive"))
      (node (ref "SV1_GPR_1") (pin "33") (pinfunction "33_33") (pintype "passive"))
      (node (ref "SV2_GPR_1") (pin "33") (pinfunction "33_33") (pintype "passive"))
      (node (ref "SV3_GPR_1") (pin "33") (pinfunction "33_33") (pintype "passive"))
      (node (ref "SV4_GPR_1") (pin "33") (pinfunction "33_33") (pintype "passive"))
      (node (ref "SV5_GPR_1") (pin "33") (pinfunction "33_33") (pintype "passive"))
      (node (ref "SV_CONST_REG_1") (pin "33") (pinfunction "33_33") (pintype "passive"))
      (node (ref "SV_EXT_2") (pin "20") (pinfunction "20_20") (pintype "passive"))
      (node (ref "SV_XFER_2") (pin "20") (pinfunction "20_20") (pintype "passive"))
    )
    (net (code "132") (name "MAIN_BUS_1") (class "Default")
      (node (ref "R18") (pin "1") (pinfunction "1_1") (pintype "passive"))
      (node (ref "SV1_GPR_1") (pin "31") (pinfunction "31_31") (pintype "passive"))
      (node (ref "SV2_GPR_1") (pin "31") (pinfunction "31_31") (pintype "passive"))
      (node (ref "SV3_GPR_1") (pin "31") (pinfunction "31_31") (pintype "passive"))
      (node (ref "SV4_GPR_1") (pin "31") (pinfunction "31_31") (pintype "passive"))
      (node (ref "SV5_GPR_1") (pin "31") (pinfunction "31_31") (pintype "passive"))
      (node (ref "SV_CONST_REG_1") (pin "31") (pinfunction "31_31") (pintype "passive"))
      (node (ref "SV_EXT_2") (pin "22") (pinfunction "22_22") (pintype "passive"))
      (node (ref "SV_XFER_2") (pin "22") (pinfunction "22_22") (pintype "passive"))
    )
    (net (code "133") (name "MAIN_BUS_2") (class "Default")
      (node (ref "R19") (pin "1") (pinfunction "1_1") (pintype "passive"))
      (node (ref "SV1_GPR_1") (pin "29") (pinfunction "29_29") (pintype "passive"))
      (node (ref "SV2_GPR_1") (pin "29") (pinfunction "29_29") (pintype "passive"))
      (node (ref "SV3_GPR_1") (pin "29") (pinfunction "29_29") (pintype "passive"))
      (node (ref "SV4_GPR_1") (pin "29") (pinfunction "29_29") (pintype "passive"))
      (node (ref "SV5_GPR_1") (pin "29") (pinfunction "29_29") (pintype "passive"))
      (node (ref "SV_CONST_REG_1") (pin "29") (pinfunction "29_29") (pintype "passive"))
      (node (ref "SV_EXT_2") (pin "24") (pinfunction "24_24") (pintype "passive"))
      (node (ref "SV_XFER_2") (pin "24") (pinfunction "24_24") (pintype "passive"))
    )
    (net (code "134") (name "MAIN_BUS_3") (class "Default")
      (node (ref "R20") (pin "1") (pinfunction "1_1") (pintype "passive"))
      (node (ref "SV1_GPR_1") (pin "27") (pinfunction "27_27") (pintype "passive"))
      (node (ref "SV2_GPR_1") (pin "27") (pinfunction "27_27") (pintype "passive"))
      (node (ref "SV3_GPR_1") (pin "27") (pinfunction "27_27") (pintype "passive"))
      (node (ref "SV4_GPR_1") (pin "27") (pinfunction "27_27") (pintype "passive"))
      (node (ref "SV5_GPR_1") (pin "27") (pinfunction "27_27") (pintype "passive"))
      (node (ref "SV_CONST_REG_1") (pin "27") (pinfunction "27_27") (pintype "passive"))
      (node (ref "SV_EXT_2") (pin "26") (pinfunction "26_26") (pintype "passive"))
      (node (ref "SV_XFER_2") (pin "26") (pinfunction "26_26") (pintype "passive"))
    )
    (net (code "135") (name "MAIN_BUS_4") (class "Default")
      (node (ref "R21") (pin "1") (pinfunction "1_1") (pintype "passive"))
      (node (ref "SV1_GPR_1") (pin "25") (pinfunction "25_25") (pintype "passive"))
      (node (ref "SV2_GPR_1") (pin "25") (pinfunction "25_25") (pintype "passive"))
      (node (ref "SV3_GPR_1") (pin "25") (pinfunction "25_25") (pintype "passive"))
      (node (ref "SV4_GPR_1") (pin "25") (pinfunction "25_25") (pintype "passive"))
      (node (ref "SV5_GPR_1") (pin "25") (pinfunction "25_25") (pintype "passive"))
      (node (ref "SV_CONST_REG_1") (pin "25") (pinfunction "25_25") (pintype "passive"))
      (node (ref "SV_EXT_2") (pin "28") (pinfunction "28_28") (pintype "passive"))
      (node (ref "SV_XFER_2") (pin "28") (pinfunction "28_28") (pintype "passive"))
    )
    (net (code "136") (name "MAIN_BUS_5") (class "Default")
      (node (ref "R22") (pin "1") (pinfunction "1_1") (pintype "passive"))
      (node (ref "SV1_GPR_1") (pin "23") (pinfunction "23_23") (pintype "passive"))
      (node (ref "SV2_GPR_1") (pin "23") (pinfunction "23_23") (pintype "passive"))
      (node (ref "SV3_GPR_1") (pin "23") (pinfunction "23_23") (pintype "passive"))
      (node (ref "SV4_GPR_1") (pin "23") (pinfunction "23_23") (pintype "passive"))
      (node (ref "SV5_GPR_1") (pin "23") (pinfunction "23_23") (pintype "passive"))
      (node (ref "SV_CONST_REG_1") (pin "23") (pinfunction "23_23") (pintype "passive"))
      (node (ref "SV_EXT_2") (pin "30") (pinfunction "30_30") (pintype "passive"))
      (node (ref "SV_XFER_2") (pin "30") (pinfunction "30_30") (pintype "passive"))
    )
    (net (code "137") (name "MAIN_BUS_6") (class "Default")
      (node (ref "R23") (pin "1") (pinfunction "1_1") (pintype "passive"))
      (node (ref "SV1_GPR_1") (pin "21") (pinfunction "21_21") (pintype "passive"))
      (node (ref "SV2_GPR_1") (pin "21") (pinfunction "21_21") (pintype "passive"))
      (node (ref "SV3_GPR_1") (pin "21") (pinfunction "21_21") (pintype "passive"))
      (node (ref "SV4_GPR_1") (pin "21") (pinfunction "21_21") (pintype "passive"))
      (node (ref "SV5_GPR_1") (pin "21") (pinfunction "21_21") (pintype "passive"))
      (node (ref "SV_CONST_REG_1") (pin "21") (pinfunction "21_21") (pintype "passive"))
      (node (ref "SV_EXT_2") (pin "32") (pinfunction "32_32") (pintype "passive"))
      (node (ref "SV_XFER_2") (pin "32") (pinfunction "32_32") (pintype "passive"))
    )
    (net (code "138") (name "MAIN_BUS_7") (class "Default")
      (node (ref "R24") (pin "1") (pinfunction "1_1") (pintype "passive"))
      (node (ref "SV1_GPR_1") (pin "19") (pinfunction "19_19") (pintype "passive"))
      (node (ref "SV2_GPR_1") (pin "19") (pinfunction "19_19") (pintype "passive"))
      (node (ref "SV3_GPR_1") (pin "19") (pinfunction "19_19") (pintype "passive"))
      (node (ref "SV4_GPR_1") (pin "19") (pinfunction "19_19") (pintype "passive"))
      (node (ref "SV5_GPR_1") (pin "19") (pinfunction "19_19") (pintype "passive"))
      (node (ref "SV_CONST_REG_1") (pin "19") (pinfunction "19_19") (pintype "passive"))
      (node (ref "SV_EXT_2") (pin "34") (pinfunction "34_34") (pintype "passive"))
      (node (ref "SV_XFER_2") (pin "34") (pinfunction "34_34") (pintype "passive"))
    )
    (net (code "139") (name "MEMORY_BUS_0") (class "Default")
      (node (ref "R32") (pin "1") (pinfunction "1_1") (pintype "passive"))
      (node (ref "SV_CONST_REG_2") (pin "34") (pinfunction "34_34") (pintype "passive"))
      (node (ref "SV_EXT_2") (pin "19") (pinfunction "19_19") (pintype "passive"))
    )
    (net (code "140") (name "MEMORY_BUS_1") (class "Default")
      (node (ref "R31") (pin "1") (pinfunction "1_1") (pintype "passive"))
      (node (ref "SV_CONST_REG_2") (pin "32") (pinfunction "32_32") (pintype "passive"))
      (node (ref "SV_EXT_2") (pin "21") (pinfunction "21_21") (pintype "passive"))
    )
    (net (code "141") (name "MEMORY_BUS_2") (class "Default")
      (node (ref "R30") (pin "1") (pinfunction "1_1") (pintype "passive"))
      (node (ref "SV_CONST_REG_2") (pin "30") (pinfunction "30_30") (pintype "passive"))
      (node (ref "SV_EXT_2") (pin "23") (pinfunction "23_23") (pintype "passive"))
    )
    (net (code "142") (name "MEMORY_BUS_3") (class "Default")
      (node (ref "R29") (pin "1") (pinfunction "1_1") (pintype "passive"))
      (node (ref "SV_CONST_REG_2") (pin "28") (pinfunction "28_28") (pintype "passive"))
      (node (ref "SV_EXT_2") (pin "25") (pinfunction "25_25") (pintype "passive"))
    )
    (net (code "143") (name "MEMORY_BUS_4") (class "Default")
      (node (ref "R28") (pin "1") (pinfunction "1_1") (pintype "passive"))
      (node (ref "SV_CONST_REG_2") (pin "26") (pinfunction "26_26") (pintype "passive"))
      (node (ref "SV_EXT_2") (pin "27") (pinfunction "27_27") (pintype "passive"))
    )
    (net (code "144") (name "MEMORY_BUS_5") (class "Default")
      (node (ref "R27") (pin "1") (pinfunction "1_1") (pintype "passive"))
      (node (ref "SV_CONST_REG_2") (pin "24") (pinfunction "24_24") (pintype "passive"))
      (node (ref "SV_EXT_2") (pin "29") (pinfunction "29_29") (pintype "passive"))
    )
    (net (code "145") (name "MEMORY_BUS_6") (class "Default")
      (node (ref "R26") (pin "1") (pinfunction "1_1") (pintype "passive"))
      (node (ref "SV_CONST_REG_2") (pin "22") (pinfunction "22_22") (pintype "passive"))
      (node (ref "SV_EXT_2") (pin "31") (pinfunction "31_31") (pintype "passive"))
    )
    (net (code "146") (name "MEMORY_BUS_7") (class "Default")
      (node (ref "R25") (pin "1") (pinfunction "1_1") (pintype "passive"))
      (node (ref "SV_CONST_REG_2") (pin "20") (pinfunction "20_20") (pintype "passive"))
      (node (ref "SV_EXT_2") (pin "33") (pinfunction "33_33") (pintype "passive"))
    )
    (net (code "147") (name "N$1") (class "Default")
      (node (ref "SV_CONST_REG_2") (pin "18") (pinfunction "18_18") (pintype "passive"))
    )
    (net (code "148") (name "N$11") (class "Default")
      (node (ref "SV_BUS_CONTROL_2") (pin "14") (pinfunction "14_14") (pintype "passive"))
      (node (ref "SV_EXT_3") (pin "17") (pinfunction "17_17") (pintype "passive"))
    )
    (net (code "149") (name "RESET") (class "Default")
      (node (ref "SV1_GPR_1") (pin "14") (pinfunction "14_14") (pintype "passive"))
      (node (ref "SV2_CREG_1") (pin "30") (pinfunction "30_30") (pintype "passive"))
      (node (ref "SV2_GPR_1") (pin "14") (pinfunction "14_14") (pintype "passive"))
      (node (ref "SV3_CREG_1") (pin "30") (pinfunction "30_30") (pintype "passive"))
      (node (ref "SV3_GPR_1") (pin "14") (pinfunction "14_14") (pintype "passive"))
      (node (ref "SV4_GPR_1") (pin "14") (pinfunction "14_14") (pintype "passive"))
      (node (ref "SV5_GPR_1") (pin "14") (pinfunction "14_14") (pintype "passive"))
      (node (ref "SV_CONST_REG_1") (pin "14") (pinfunction "14_14") (pintype "passive"))
      (node (ref "SV_CREG_1") (pin "30") (pinfunction "30_30") (pintype "passive"))
      (node (ref "SV_EXT_3") (pin "9") (pinfunction "9_9") (pintype "passive"))
      (node (ref "SV_XFER_2") (pin "8") (pinfunction "8_8") (pintype "passive"))
    )
    (net (code "150") (name "VCC") (class "Default")
      (node (ref "C1") (pin "+") (pinfunction "+_+") (pintype "passive"))
      (node (ref "C2") (pin "+") (pinfunction "+_+") (pintype "passive"))
      (node (ref "SV1_GPR_1") (pin "1") (pinfunction "1_1") (pintype "passive"))
      (node (ref "SV1_GPR_1") (pin "36") (pinfunction "36_36") (pintype "passive"))
      (node (ref "SV1_GPR_2") (pin "1") (pinfunction "1_1") (pintype "passive"))
      (node (ref "SV1_GPR_2") (pin "36") (pinfunction "36_36") (pintype "passive"))
      (node (ref "SV2_CREG_1") (pin "1") (pinfunction "1_1") (pintype "passive"))
      (node (ref "SV2_CREG_1") (pin "36") (pinfunction "36_36") (pintype "passive"))
      (node (ref "SV2_CREG_2") (pin "1") (pinfunction "1_1") (pintype "passive"))
      (node (ref "SV2_CREG_2") (pin "36") (pinfunction "36_36") (pintype "passive"))
      (node (ref "SV2_GPR_1") (pin "1") (pinfunction "1_1") (pintype "passive"))
      (node (ref "SV2_GPR_1") (pin "36") (pinfunction "36_36") (pintype "passive"))
      (node (ref "SV2_GPR_2") (pin "1") (pinfunction "1_1") (pintype "passive"))
      (node (ref "SV2_GPR_2") (pin "36") (pinfunction "36_36") (pintype "passive"))
      (node (ref "SV3_CREG_1") (pin "1") (pinfunction "1_1") (pintype "passive"))
      (node (ref "SV3_CREG_1") (pin "36") (pinfunction "36_36") (pintype "passive"))
      (node (ref "SV3_CREG_2") (pin "1") (pinfunction "1_1") (pintype "passive"))
      (node (ref "SV3_CREG_2") (pin "36") (pinfunction "36_36") (pintype "passive"))
      (node (ref "SV3_GPR_1") (pin "1") (pinfunction "1_1") (pintype "passive"))
      (node (ref "SV3_GPR_1") (pin "36") (pinfunction "36_36") (pintype "passive"))
      (node (ref "SV3_GPR_2") (pin "1") (pinfunction "1_1") (pintype "passive"))
      (node (ref "SV3_GPR_2") (pin "36") (pinfunction "36_36") (pintype "passive"))
      (node (ref "SV4_GPR_1") (pin "1") (pinfunction "1_1") (pintype "passive"))
      (node (ref "SV4_GPR_1") (pin "36") (pinfunction "36_36") (pintype "passive"))
      (node (ref "SV4_GPR_2") (pin "1") (pinfunction "1_1") (pintype "passive"))
      (node (ref "SV4_GPR_2") (pin "36") (pinfunction "36_36") (pintype "passive"))
      (node (ref "SV5_GPR_1") (pin "1") (pinfunction "1_1") (pintype "passive"))
      (node (ref "SV5_GPR_1") (pin "36") (pinfunction "36_36") (pintype "passive"))
      (node (ref "SV5_GPR_2") (pin "1") (pinfunction "1_1") (pintype "passive"))
      (node (ref "SV5_GPR_2") (pin "36") (pinfunction "36_36") (pintype "passive"))
      (node (ref "SV_BUS_CONTROL_1") (pin "1") (pinfunction "1_1") (pintype "passive"))
      (node (ref "SV_BUS_CONTROL_1") (pin "36") (pinfunction "36_36") (pintype "passive"))
      (node (ref "SV_BUS_CONTROL_2") (pin "1") (pinfunction "1_1") (pintype "passive"))
      (node (ref "SV_BUS_CONTROL_2") (pin "36") (pinfunction "36_36") (pintype "passive"))
      (node (ref "SV_BUS_CONTROL_3") (pin "1") (pinfunction "1_1") (pintype "passive"))
      (node (ref "SV_BUS_CONTROL_3") (pin "36") (pinfunction "36_36") (pintype "passive"))
      (node (ref "SV_BUS_CONTROL_4") (pin "1") (pinfunction "1_1") (pintype "passive"))
      (node (ref "SV_BUS_CONTROL_4") (pin "36") (pinfunction "36_36") (pintype "passive"))
      (node (ref "SV_CONST_REG_1") (pin "1") (pinfunction "1_1") (pintype "passive"))
      (node (ref "SV_CONST_REG_1") (pin "36") (pinfunction "36_36") (pintype "passive"))
      (node (ref "SV_CONST_REG_2") (pin "1") (pinfunction "1_1") (pintype "passive"))
      (node (ref "SV_CONST_REG_2") (pin "36") (pinfunction "36_36") (pintype "passive"))
      (node (ref "SV_CREG_1") (pin "1") (pinfunction "1_1") (pintype "passive"))
      (node (ref "SV_CREG_1") (pin "36") (pinfunction "36_36") (pintype "passive"))
      (node (ref "SV_CREG_2") (pin "1") (pinfunction "1_1") (pintype "passive"))
      (node (ref "SV_CREG_2") (pin "36") (pinfunction "36_36") (pintype "passive"))
      (node (ref "SV_EXT_1") (pin "1") (pinfunction "1_1") (pintype "passive"))
      (node (ref "SV_EXT_1") (pin "36") (pinfunction "36_36") (pintype "passive"))
      (node (ref "SV_EXT_2") (pin "1") (pinfunction "1_1") (pintype "passive"))
      (node (ref "SV_EXT_2") (pin "36") (pinfunction "36_36") (pintype "passive"))
      (node (ref "SV_EXT_3") (pin "1") (pinfunction "1_1") (pintype "passive"))
      (node (ref "SV_EXT_3") (pin "36") (pinfunction "36_36") (pintype "passive"))
      (node (ref "SV_EXT_4") (pin "1") (pinfunction "1_1") (pintype "passive"))
      (node (ref "SV_EXT_4") (pin "36") (pinfunction "36_36") (pintype "passive"))
      (node (ref "SV_XFER_1") (pin "1") (pinfunction "1_1") (pintype "passive"))
      (node (ref "SV_XFER_1") (pin "36") (pinfunction "36_36") (pintype "passive"))
      (node (ref "SV_XFER_2") (pin "1") (pinfunction "1_1") (pintype "passive"))
      (node (ref "SV_XFER_2") (pin "36") (pinfunction "36_36") (pintype "passive"))
      (node (ref "SV_XFER_3") (pin "1") (pinfunction "1_1") (pintype "passive"))
      (node (ref "SV_XFER_3") (pin "36") (pinfunction "36_36") (pintype "passive"))
      (node (ref "SV_XFER_4") (pin "1") (pinfunction "1_1") (pintype "passive"))
      (node (ref "SV_XFER_4") (pin "36") (pinfunction "36_36") (pintype "passive"))
    )
    (net (code "151") (name "XFER_BUS_0") (class "Default")
      (node (ref "R64") (pin "1") (pinfunction "1_1") (pintype "passive"))
      (node (ref "SV2_CREG_2") (pin "34") (pinfunction "34_34") (pintype "passive"))
      (node (ref "SV3_CREG_2") (pin "34") (pinfunction "34_34") (pintype "passive"))
      (node (ref "SV_CREG_2") (pin "34") (pinfunction "34_34") (pintype "passive"))
      (node (ref "SV_EXT_1") (pin "3") (pinfunction "3_3") (pintype "passive"))
      (node (ref "SV_XFER_1") (pin "3") (pinfunction "3_3") (pintype "passive"))
    )
    (net (code "152") (name "XFER_BUS_1") (class "Default")
      (node (ref "R63") (pin "1") (pinfunction "1_1") (pintype "passive"))
      (node (ref "SV2_CREG_2") (pin "32") (pinfunction "32_32") (pintype "passive"))
      (node (ref "SV3_CREG_2") (pin "32") (pinfunction "32_32") (pintype "passive"))
      (node (ref "SV_CREG_2") (pin "32") (pinfunction "32_32") (pintype "passive"))
      (node (ref "SV_EXT_1") (pin "5") (pinfunction "5_5") (pintype "passive"))
      (node (ref "SV_XFER_1") (pin "5") (pinfunction "5_5") (pintype "passive"))
    )
    (net (code "153") (name "XFER_BUS_2") (class "Default")
      (node (ref "R62") (pin "1") (pinfunction "1_1") (pintype "passive"))
      (node (ref "SV2_CREG_2") (pin "30") (pinfunction "30_30") (pintype "passive"))
      (node (ref "SV3_CREG_2") (pin "30") (pinfunction "30_30") (pintype "passive"))
      (node (ref "SV_CREG_2") (pin "30") (pinfunction "30_30") (pintype "passive"))
      (node (ref "SV_EXT_1") (pin "7") (pinfunction "7_7") (pintype "passive"))
      (node (ref "SV_XFER_1") (pin "7") (pinfunction "7_7") (pintype "passive"))
    )
    (net (code "154") (name "XFER_BUS_3") (class "Default")
      (node (ref "R61") (pin "1") (pinfunction "1_1") (pintype "passive"))
      (node (ref "SV2_CREG_2") (pin "28") (pinfunction "28_28") (pintype "passive"))
      (node (ref "SV3_CREG_2") (pin "28") (pinfunction "28_28") (pintype "passive"))
      (node (ref "SV_CREG_2") (pin "28") (pinfunction "28_28") (pintype "passive"))
      (node (ref "SV_EXT_1") (pin "9") (pinfunction "9_9") (pintype "passive"))
      (node (ref "SV_XFER_1") (pin "9") (pinfunction "9_9") (pintype "passive"))
    )
    (net (code "155") (name "XFER_BUS_4") (class "Default")
      (node (ref "R60") (pin "1") (pinfunction "1_1") (pintype "passive"))
      (node (ref "SV2_CREG_2") (pin "26") (pinfunction "26_26") (pintype "passive"))
      (node (ref "SV3_CREG_2") (pin "26") (pinfunction "26_26") (pintype "passive"))
      (node (ref "SV_CREG_2") (pin "26") (pinfunction "26_26") (pintype "passive"))
      (node (ref "SV_EXT_1") (pin "11") (pinfunction "11_11") (pintype "passive"))
      (node (ref "SV_XFER_1") (pin "11") (pinfunction "11_11") (pintype "passive"))
    )
    (net (code "156") (name "XFER_BUS_5") (class "Default")
      (node (ref "R59") (pin "1") (pinfunction "1_1") (pintype "passive"))
      (node (ref "SV2_CREG_2") (pin "24") (pinfunction "24_24") (pintype "passive"))
      (node (ref "SV3_CREG_2") (pin "24") (pinfunction "24_24") (pintype "passive"))
      (node (ref "SV_CREG_2") (pin "24") (pinfunction "24_24") (pintype "passive"))
      (node (ref "SV_EXT_1") (pin "13") (pinfunction "13_13") (pintype "passive"))
      (node (ref "SV_XFER_1") (pin "13") (pinfunction "13_13") (pintype "passive"))
    )
    (net (code "157") (name "XFER_BUS_6") (class "Default")
      (node (ref "R58") (pin "1") (pinfunction "1_1") (pintype "passive"))
      (node (ref "SV2_CREG_2") (pin "22") (pinfunction "22_22") (pintype "passive"))
      (node (ref "SV3_CREG_2") (pin "22") (pinfunction "22_22") (pintype "passive"))
      (node (ref "SV_CREG_2") (pin "22") (pinfunction "22_22") (pintype "passive"))
      (node (ref "SV_EXT_1") (pin "15") (pinfunction "15_15") (pintype "passive"))
      (node (ref "SV_XFER_1") (pin "15") (pinfunction "15_15") (pintype "passive"))
    )
    (net (code "158") (name "XFER_BUS_7") (class "Default")
      (node (ref "R57") (pin "1") (pinfunction "1_1") (pintype "passive"))
      (node (ref "SV2_CREG_2") (pin "20") (pinfunction "20_20") (pintype "passive"))
      (node (ref "SV3_CREG_2") (pin "20") (pinfunction "20_20") (pintype "passive"))
      (node (ref "SV_CREG_2") (pin "20") (pinfunction "20_20") (pintype "passive"))
      (node (ref "SV_EXT_1") (pin "17") (pinfunction "17_17") (pintype "passive"))
      (node (ref "SV_XFER_1") (pin "17") (pinfunction "17_17") (pintype "passive"))
    )
    (net (code "159") (name "XFER_BUS_8") (class "Default")
      (node (ref "R56") (pin "1") (pinfunction "1_1") (pintype "passive"))
      (node (ref "SV2_CREG_2") (pin "18") (pinfunction "18_18") (pintype "passive"))
      (node (ref "SV3_CREG_2") (pin "18") (pinfunction "18_18") (pintype "passive"))
      (node (ref "SV_CREG_2") (pin "18") (pinfunction "18_18") (pintype "passive"))
      (node (ref "SV_EXT_1") (pin "19") (pinfunction "19_19") (pintype "passive"))
      (node (ref "SV_XFER_1") (pin "19") (pinfunction "19_19") (pintype "passive"))
    )
    (net (code "160") (name "XFER_BUS_9") (class "Default")
      (node (ref "R55") (pin "1") (pinfunction "1_1") (pintype "passive"))
      (node (ref "SV2_CREG_2") (pin "16") (pinfunction "16_16") (pintype "passive"))
      (node (ref "SV3_CREG_2") (pin "16") (pinfunction "16_16") (pintype "passive"))
      (node (ref "SV_CREG_2") (pin "16") (pinfunction "16_16") (pintype "passive"))
      (node (ref "SV_EXT_1") (pin "21") (pinfunction "21_21") (pintype "passive"))
      (node (ref "SV_XFER_1") (pin "21") (pinfunction "21_21") (pintype "passive"))
    )
    (net (code "161") (name "XFER_BUS_10") (class "Default")
      (node (ref "R54") (pin "1") (pinfunction "1_1") (pintype "passive"))
      (node (ref "SV2_CREG_2") (pin "14") (pinfunction "14_14") (pintype "passive"))
      (node (ref "SV3_CREG_2") (pin "14") (pinfunction "14_14") (pintype "passive"))
      (node (ref "SV_CREG_2") (pin "14") (pinfunction "14_14") (pintype "passive"))
      (node (ref "SV_EXT_1") (pin "23") (pinfunction "23_23") (pintype "passive"))
      (node (ref "SV_XFER_1") (pin "23") (pinfunction "23_23") (pintype "passive"))
    )
    (net (code "162") (name "XFER_BUS_11") (class "Default")
      (node (ref "R53") (pin "1") (pinfunction "1_1") (pintype "passive"))
      (node (ref "SV2_CREG_2") (pin "12") (pinfunction "12_12") (pintype "passive"))
      (node (ref "SV3_CREG_2") (pin "12") (pinfunction "12_12") (pintype "passive"))
      (node (ref "SV_CREG_2") (pin "12") (pinfunction "12_12") (pintype "passive"))
      (node (ref "SV_EXT_1") (pin "25") (pinfunction "25_25") (pintype "passive"))
      (node (ref "SV_XFER_1") (pin "25") (pinfunction "25_25") (pintype "passive"))
    )
    (net (code "163") (name "XFER_BUS_12") (class "Default")
      (node (ref "R52") (pin "1") (pinfunction "1_1") (pintype "passive"))
      (node (ref "SV2_CREG_2") (pin "10") (pinfunction "10_10") (pintype "passive"))
      (node (ref "SV3_CREG_2") (pin "10") (pinfunction "10_10") (pintype "passive"))
      (node (ref "SV_CREG_2") (pin "10") (pinfunction "10_10") (pintype "passive"))
      (node (ref "SV_EXT_1") (pin "27") (pinfunction "27_27") (pintype "passive"))
      (node (ref "SV_XFER_1") (pin "27") (pinfunction "27_27") (pintype "passive"))
    )
    (net (code "164") (name "XFER_BUS_13") (class "Default")
      (node (ref "R51") (pin "1") (pinfunction "1_1") (pintype "passive"))
      (node (ref "SV2_CREG_2") (pin "8") (pinfunction "8_8") (pintype "passive"))
      (node (ref "SV3_CREG_2") (pin "8") (pinfunction "8_8") (pintype "passive"))
      (node (ref "SV_CREG_2") (pin "8") (pinfunction "8_8") (pintype "passive"))
      (node (ref "SV_EXT_1") (pin "29") (pinfunction "29_29") (pintype "passive"))
      (node (ref "SV_XFER_1") (pin "29") (pinfunction "29_29") (pintype "passive"))
    )
    (net (code "165") (name "XFER_BUS_14") (class "Default")
      (node (ref "R50") (pin "1") (pinfunction "1_1") (pintype "passive"))
      (node (ref "SV2_CREG_2") (pin "6") (pinfunction "6_6") (pintype "passive"))
      (node (ref "SV3_CREG_2") (pin "6") (pinfunction "6_6") (pintype "passive"))
      (node (ref "SV_CREG_2") (pin "6") (pinfunction "6_6") (pintype "passive"))
      (node (ref "SV_EXT_1") (pin "31") (pinfunction "31_31") (pintype "passive"))
      (node (ref "SV_XFER_1") (pin "31") (pinfunction "31_31") (pintype "passive"))
    )
    (net (code "166") (name "XFER_BUS_15") (class "Default")
      (node (ref "R49") (pin "1") (pinfunction "1_1") (pintype "passive"))
      (node (ref "SV2_CREG_2") (pin "4") (pinfunction "4_4") (pintype "passive"))
      (node (ref "SV3_CREG_2") (pin "4") (pinfunction "4_4") (pintype "passive"))
      (node (ref "SV_CREG_2") (pin "4") (pinfunction "4_4") (pintype "passive"))
      (node (ref "SV_EXT_1") (pin "33") (pinfunction "33_33") (pintype "passive"))
      (node (ref "SV_XFER_1") (pin "33") (pinfunction "33_33") (pintype "passive"))
    )
    (net (code "167") (name "unconnected-(SV1_GPR_1-Pad4)") (class "Default")
      (node (ref "SV1_GPR_1") (pin "4") (pinfunction "4_4") (pintype "passive"))
    )
    (net (code "168") (name "unconnected-(SV1_GPR_1-Pad6)") (class "Default")
      (node (ref "SV1_GPR_1") (pin "6") (pinfunction "6_6") (pintype "passive"))
    )
    (net (code "169") (name "unconnected-(SV1_GPR_1-Pad8)") (class "Default")
      (node (ref "SV1_GPR_1") (pin "8") (pinfunction "8_8") (pintype "passive"))
    )
    (net (code "170") (name "unconnected-(SV1_GPR_1-Pad10)") (class "Default")
      (node (ref "SV1_GPR_1") (pin "10") (pinfunction "10_10") (pintype "passive"))
    )
    (net (code "171") (name "unconnected-(SV1_GPR_2-Pad4)") (class "Default")
      (node (ref "SV1_GPR_2") (pin "4") (pinfunction "4_4") (pintype "passive"))
    )
    (net (code "172") (name "unconnected-(SV1_GPR_2-Pad6)") (class "Default")
      (node (ref "SV1_GPR_2") (pin "6") (pinfunction "6_6") (pintype "passive"))
    )
    (net (code "173") (name "unconnected-(SV1_GPR_2-Pad8)") (class "Default")
      (node (ref "SV1_GPR_2") (pin "8") (pinfunction "8_8") (pintype "passive"))
    )
    (net (code "174") (name "unconnected-(SV1_GPR_2-Pad10)") (class "Default")
      (node (ref "SV1_GPR_2") (pin "10") (pinfunction "10_10") (pintype "passive"))
    )
    (net (code "175") (name "unconnected-(SV1_GPR_2-Pad12)") (class "Default")
      (node (ref "SV1_GPR_2") (pin "12") (pinfunction "12_12") (pintype "passive"))
    )
    (net (code "176") (name "unconnected-(SV1_GPR_2-Pad14)") (class "Default")
      (node (ref "SV1_GPR_2") (pin "14") (pinfunction "14_14") (pintype "passive"))
    )
    (net (code "177") (name "unconnected-(SV2_CREG_1-Pad4)") (class "Default")
      (node (ref "SV2_CREG_1") (pin "4") (pinfunction "4_4") (pintype "passive"))
    )
    (net (code "178") (name "unconnected-(SV2_CREG_1-Pad6)") (class "Default")
      (node (ref "SV2_CREG_1") (pin "6") (pinfunction "6_6") (pintype "passive"))
    )
    (net (code "179") (name "unconnected-(SV2_CREG_1-Pad8)") (class "Default")
      (node (ref "SV2_CREG_1") (pin "8") (pinfunction "8_8") (pintype "passive"))
    )
    (net (code "180") (name "unconnected-(SV2_CREG_1-Pad10)") (class "Default")
      (node (ref "SV2_CREG_1") (pin "10") (pinfunction "10_10") (pintype "passive"))
    )
    (net (code "181") (name "unconnected-(SV2_CREG_1-Pad12)") (class "Default")
      (node (ref "SV2_CREG_1") (pin "12") (pinfunction "12_12") (pintype "passive"))
    )
    (net (code "182") (name "unconnected-(SV2_CREG_1-Pad14)") (class "Default")
      (node (ref "SV2_CREG_1") (pin "14") (pinfunction "14_14") (pintype "passive"))
    )
    (net (code "183") (name "unconnected-(SV2_CREG_1-Pad15)") (class "Default")
      (node (ref "SV2_CREG_1") (pin "15") (pinfunction "15_15") (pintype "passive"))
    )
    (net (code "184") (name "unconnected-(SV2_CREG_1-Pad17)") (class "Default")
      (node (ref "SV2_CREG_1") (pin "17") (pinfunction "17_17") (pintype "passive"))
    )
    (net (code "185") (name "unconnected-(SV2_CREG_1-Pad19)") (class "Default")
      (node (ref "SV2_CREG_1") (pin "19") (pinfunction "19_19") (pintype "passive"))
    )
    (net (code "186") (name "unconnected-(SV2_CREG_1-Pad21)") (class "Default")
      (node (ref "SV2_CREG_1") (pin "21") (pinfunction "21_21") (pintype "passive"))
    )
    (net (code "187") (name "unconnected-(SV2_CREG_1-Pad23)") (class "Default")
      (node (ref "SV2_CREG_1") (pin "23") (pinfunction "23_23") (pintype "passive"))
    )
    (net (code "188") (name "unconnected-(SV2_CREG_1-Pad25)") (class "Default")
      (node (ref "SV2_CREG_1") (pin "25") (pinfunction "25_25") (pintype "passive"))
    )
    (net (code "189") (name "unconnected-(SV2_CREG_1-Pad27)") (class "Default")
      (node (ref "SV2_CREG_1") (pin "27") (pinfunction "27_27") (pintype "passive"))
    )
    (net (code "190") (name "unconnected-(SV2_GPR_1-Pad4)") (class "Default")
      (node (ref "SV2_GPR_1") (pin "4") (pinfunction "4_4") (pintype "passive"))
    )
    (net (code "191") (name "unconnected-(SV2_GPR_1-Pad6)") (class "Default")
      (node (ref "SV2_GPR_1") (pin "6") (pinfunction "6_6") (pintype "passive"))
    )
    (net (code "192") (name "unconnected-(SV2_GPR_1-Pad8)") (class "Default")
      (node (ref "SV2_GPR_1") (pin "8") (pinfunction "8_8") (pintype "passive"))
    )
    (net (code "193") (name "unconnected-(SV2_GPR_1-Pad10)") (class "Default")
      (node (ref "SV2_GPR_1") (pin "10") (pinfunction "10_10") (pintype "passive"))
    )
    (net (code "194") (name "unconnected-(SV2_GPR_2-Pad4)") (class "Default")
      (node (ref "SV2_GPR_2") (pin "4") (pinfunction "4_4") (pintype "passive"))
    )
    (net (code "195") (name "unconnected-(SV2_GPR_2-Pad6)") (class "Default")
      (node (ref "SV2_GPR_2") (pin "6") (pinfunction "6_6") (pintype "passive"))
    )
    (net (code "196") (name "unconnected-(SV2_GPR_2-Pad8)") (class "Default")
      (node (ref "SV2_GPR_2") (pin "8") (pinfunction "8_8") (pintype "passive"))
    )
    (net (code "197") (name "unconnected-(SV2_GPR_2-Pad10)") (class "Default")
      (node (ref "SV2_GPR_2") (pin "10") (pinfunction "10_10") (pintype "passive"))
    )
    (net (code "198") (name "unconnected-(SV2_GPR_2-Pad12)") (class "Default")
      (node (ref "SV2_GPR_2") (pin "12") (pinfunction "12_12") (pintype "passive"))
    )
    (net (code "199") (name "unconnected-(SV2_GPR_2-Pad14)") (class "Default")
      (node (ref "SV2_GPR_2") (pin "14") (pinfunction "14_14") (pintype "passive"))
    )
    (net (code "200") (name "unconnected-(SV3_CREG_1-Pad4)") (class "Default")
      (node (ref "SV3_CREG_1") (pin "4") (pinfunction "4_4") (pintype "passive"))
    )
    (net (code "201") (name "unconnected-(SV3_CREG_1-Pad6)") (class "Default")
      (node (ref "SV3_CREG_1") (pin "6") (pinfunction "6_6") (pintype "passive"))
    )
    (net (code "202") (name "unconnected-(SV3_CREG_1-Pad8)") (class "Default")
      (node (ref "SV3_CREG_1") (pin "8") (pinfunction "8_8") (pintype "passive"))
    )
    (net (code "203") (name "unconnected-(SV3_CREG_1-Pad10)") (class "Default")
      (node (ref "SV3_CREG_1") (pin "10") (pinfunction "10_10") (pintype "passive"))
    )
    (net (code "204") (name "unconnected-(SV3_CREG_1-Pad12)") (class "Default")
      (node (ref "SV3_CREG_1") (pin "12") (pinfunction "12_12") (pintype "passive"))
    )
    (net (code "205") (name "unconnected-(SV3_CREG_1-Pad14)") (class "Default")
      (node (ref "SV3_CREG_1") (pin "14") (pinfunction "14_14") (pintype "passive"))
    )
    (net (code "206") (name "unconnected-(SV3_CREG_1-Pad15)") (class "Default")
      (node (ref "SV3_CREG_1") (pin "15") (pinfunction "15_15") (pintype "passive"))
    )
    (net (code "207") (name "unconnected-(SV3_CREG_1-Pad17)") (class "Default")
      (node (ref "SV3_CREG_1") (pin "17") (pinfunction "17_17") (pintype "passive"))
    )
    (net (code "208") (name "unconnected-(SV3_CREG_1-Pad19)") (class "Default")
      (node (ref "SV3_CREG_1") (pin "19") (pinfunction "19_19") (pintype "passive"))
    )
    (net (code "209") (name "unconnected-(SV3_CREG_1-Pad21)") (class "Default")
      (node (ref "SV3_CREG_1") (pin "21") (pinfunction "21_21") (pintype "passive"))
    )
    (net (code "210") (name "unconnected-(SV3_CREG_1-Pad23)") (class "Default")
      (node (ref "SV3_CREG_1") (pin "23") (pinfunction "23_23") (pintype "passive"))
    )
    (net (code "211") (name "unconnected-(SV3_CREG_1-Pad25)") (class "Default")
      (node (ref "SV3_CREG_1") (pin "25") (pinfunction "25_25") (pintype "passive"))
    )
    (net (code "212") (name "unconnected-(SV3_CREG_1-Pad27)") (class "Default")
      (node (ref "SV3_CREG_1") (pin "27") (pinfunction "27_27") (pintype "passive"))
    )
    (net (code "213") (name "unconnected-(SV3_GPR_1-Pad4)") (class "Default")
      (node (ref "SV3_GPR_1") (pin "4") (pinfunction "4_4") (pintype "passive"))
    )
    (net (code "214") (name "unconnected-(SV3_GPR_1-Pad6)") (class "Default")
      (node (ref "SV3_GPR_1") (pin "6") (pinfunction "6_6") (pintype "passive"))
    )
    (net (code "215") (name "unconnected-(SV3_GPR_1-Pad8)") (class "Default")
      (node (ref "SV3_GPR_1") (pin "8") (pinfunction "8_8") (pintype "passive"))
    )
    (net (code "216") (name "unconnected-(SV3_GPR_1-Pad10)") (class "Default")
      (node (ref "SV3_GPR_1") (pin "10") (pinfunction "10_10") (pintype "passive"))
    )
    (net (code "217") (name "unconnected-(SV3_GPR_2-Pad4)") (class "Default")
      (node (ref "SV3_GPR_2") (pin "4") (pinfunction "4_4") (pintype "passive"))
    )
    (net (code "218") (name "unconnected-(SV3_GPR_2-Pad6)") (class "Default")
      (node (ref "SV3_GPR_2") (pin "6") (pinfunction "6_6") (pintype "passive"))
    )
    (net (code "219") (name "unconnected-(SV3_GPR_2-Pad8)") (class "Default")
      (node (ref "SV3_GPR_2") (pin "8") (pinfunction "8_8") (pintype "passive"))
    )
    (net (code "220") (name "unconnected-(SV3_GPR_2-Pad10)") (class "Default")
      (node (ref "SV3_GPR_2") (pin "10") (pinfunction "10_10") (pintype "passive"))
    )
    (net (code "221") (name "unconnected-(SV3_GPR_2-Pad12)") (class "Default")
      (node (ref "SV3_GPR_2") (pin "12") (pinfunction "12_12") (pintype "passive"))
    )
    (net (code "222") (name "unconnected-(SV3_GPR_2-Pad14)") (class "Default")
      (node (ref "SV3_GPR_2") (pin "14") (pinfunction "14_14") (pintype "passive"))
    )
    (net (code "223") (name "unconnected-(SV4_GPR_1-Pad4)") (class "Default")
      (node (ref "SV4_GPR_1") (pin "4") (pinfunction "4_4") (pintype "passive"))
    )
    (net (code "224") (name "unconnected-(SV4_GPR_1-Pad6)") (class "Default")
      (node (ref "SV4_GPR_1") (pin "6") (pinfunction "6_6") (pintype "passive"))
    )
    (net (code "225") (name "unconnected-(SV4_GPR_1-Pad8)") (class "Default")
      (node (ref "SV4_GPR_1") (pin "8") (pinfunction "8_8") (pintype "passive"))
    )
    (net (code "226") (name "unconnected-(SV4_GPR_1-Pad10)") (class "Default")
      (node (ref "SV4_GPR_1") (pin "10") (pinfunction "10_10") (pintype "passive"))
    )
    (net (code "227") (name "unconnected-(SV4_GPR_2-Pad4)") (class "Default")
      (node (ref "SV4_GPR_2") (pin "4") (pinfunction "4_4") (pintype "passive"))
    )
    (net (code "228") (name "unconnected-(SV4_GPR_2-Pad6)") (class "Default")
      (node (ref "SV4_GPR_2") (pin "6") (pinfunction "6_6") (pintype "passive"))
    )
    (net (code "229") (name "unconnected-(SV4_GPR_2-Pad8)") (class "Default")
      (node (ref "SV4_GPR_2") (pin "8") (pinfunction "8_8") (pintype "passive"))
    )
    (net (code "230") (name "unconnected-(SV4_GPR_2-Pad10)") (class "Default")
      (node (ref "SV4_GPR_2") (pin "10") (pinfunction "10_10") (pintype "passive"))
    )
    (net (code "231") (name "unconnected-(SV4_GPR_2-Pad12)") (class "Default")
      (node (ref "SV4_GPR_2") (pin "12") (pinfunction "12_12") (pintype "passive"))
    )
    (net (code "232") (name "unconnected-(SV4_GPR_2-Pad14)") (class "Default")
      (node (ref "SV4_GPR_2") (pin "14") (pinfunction "14_14") (pintype "passive"))
    )
    (net (code "233") (name "unconnected-(SV5_GPR_1-Pad4)") (class "Default")
      (node (ref "SV5_GPR_1") (pin "4") (pinfunction "4_4") (pintype "passive"))
    )
    (net (code "234") (name "unconnected-(SV5_GPR_1-Pad6)") (class "Default")
      (node (ref "SV5_GPR_1") (pin "6") (pinfunction "6_6") (pintype "passive"))
    )
    (net (code "235") (name "unconnected-(SV5_GPR_1-Pad8)") (class "Default")
      (node (ref "SV5_GPR_1") (pin "8") (pinfunction "8_8") (pintype "passive"))
    )
    (net (code "236") (name "unconnected-(SV5_GPR_1-Pad10)") (class "Default")
      (node (ref "SV5_GPR_1") (pin "10") (pinfunction "10_10") (pintype "passive"))
    )
    (net (code "237") (name "unconnected-(SV5_GPR_2-Pad4)") (class "Default")
      (node (ref "SV5_GPR_2") (pin "4") (pinfunction "4_4") (pintype "passive"))
    )
    (net (code "238") (name "unconnected-(SV5_GPR_2-Pad6)") (class "Default")
      (node (ref "SV5_GPR_2") (pin "6") (pinfunction "6_6") (pintype "passive"))
    )
    (net (code "239") (name "unconnected-(SV5_GPR_2-Pad8)") (class "Default")
      (node (ref "SV5_GPR_2") (pin "8") (pinfunction "8_8") (pintype "passive"))
    )
    (net (code "240") (name "unconnected-(SV5_GPR_2-Pad10)") (class "Default")
      (node (ref "SV5_GPR_2") (pin "10") (pinfunction "10_10") (pintype "passive"))
    )
    (net (code "241") (name "unconnected-(SV5_GPR_2-Pad12)") (class "Default")
      (node (ref "SV5_GPR_2") (pin "12") (pinfunction "12_12") (pintype "passive"))
    )
    (net (code "242") (name "unconnected-(SV5_GPR_2-Pad14)") (class "Default")
      (node (ref "SV5_GPR_2") (pin "14") (pinfunction "14_14") (pintype "passive"))
    )
    (net (code "243") (name "unconnected-(SV_BUS_CONTROL_1-Pad3)") (class "Default")
      (node (ref "SV_BUS_CONTROL_1") (pin "3") (pinfunction "3_3") (pintype "passive"))
    )
    (net (code "244") (name "unconnected-(SV_BUS_CONTROL_1-Pad4)") (class "Default")
      (node (ref "SV_BUS_CONTROL_1") (pin "4") (pinfunction "4_4") (pintype "passive"))
    )
    (net (code "245") (name "unconnected-(SV_BUS_CONTROL_1-Pad5)") (class "Default")
      (node (ref "SV_BUS_CONTROL_1") (pin "5") (pinfunction "5_5") (pintype "passive"))
    )
    (net (code "246") (name "unconnected-(SV_BUS_CONTROL_1-Pad7)") (class "Default")
      (node (ref "SV_BUS_CONTROL_1") (pin "7") (pinfunction "7_7") (pintype "passive"))
    )
    (net (code "247") (name "unconnected-(SV_BUS_CONTROL_1-Pad9)") (class "Default")
      (node (ref "SV_BUS_CONTROL_1") (pin "9") (pinfunction "9_9") (pintype "passive"))
    )
    (net (code "248") (name "unconnected-(SV_BUS_CONTROL_1-Pad11)") (class "Default")
      (node (ref "SV_BUS_CONTROL_1") (pin "11") (pinfunction "11_11") (pintype "passive"))
    )
    (net (code "249") (name "unconnected-(SV_BUS_CONTROL_1-Pad13)") (class "Default")
      (node (ref "SV_BUS_CONTROL_1") (pin "13") (pinfunction "13_13") (pintype "passive"))
    )
    (net (code "250") (name "unconnected-(SV_BUS_CONTROL_1-Pad15)") (class "Default")
      (node (ref "SV_BUS_CONTROL_1") (pin "15") (pinfunction "15_15") (pintype "passive"))
    )
    (net (code "251") (name "unconnected-(SV_BUS_CONTROL_1-Pad17)") (class "Default")
      (node (ref "SV_BUS_CONTROL_1") (pin "17") (pinfunction "17_17") (pintype "passive"))
    )
    (net (code "252") (name "unconnected-(SV_BUS_CONTROL_1-Pad19)") (class "Default")
      (node (ref "SV_BUS_CONTROL_1") (pin "19") (pinfunction "19_19") (pintype "passive"))
    )
    (net (code "253") (name "unconnected-(SV_BUS_CONTROL_1-Pad21)") (class "Default")
      (node (ref "SV_BUS_CONTROL_1") (pin "21") (pinfunction "21_21") (pintype "passive"))
    )
    (net (code "254") (name "unconnected-(SV_BUS_CONTROL_2-Pad3)") (class "Default")
      (node (ref "SV_BUS_CONTROL_2") (pin "3") (pinfunction "3_3") (pintype "passive"))
    )
    (net (code "255") (name "unconnected-(SV_BUS_CONTROL_2-Pad4)") (class "Default")
      (node (ref "SV_BUS_CONTROL_2") (pin "4") (pinfunction "4_4") (pintype "passive"))
    )
    (net (code "256") (name "unconnected-(SV_BUS_CONTROL_3-Pad3)") (class "Default")
      (node (ref "SV_BUS_CONTROL_3") (pin "3") (pinfunction "3_3") (pintype "passive"))
    )
    (net (code "257") (name "unconnected-(SV_BUS_CONTROL_3-Pad4)") (class "Default")
      (node (ref "SV_BUS_CONTROL_3") (pin "4") (pinfunction "4_4") (pintype "passive"))
    )
    (net (code "258") (name "unconnected-(SV_BUS_CONTROL_3-Pad5)") (class "Default")
      (node (ref "SV_BUS_CONTROL_3") (pin "5") (pinfunction "5_5") (pintype "passive"))
    )
    (net (code "259") (name "unconnected-(SV_BUS_CONTROL_3-Pad6)") (class "Default")
      (node (ref "SV_BUS_CONTROL_3") (pin "6") (pinfunction "6_6") (pintype "passive"))
    )
    (net (code "260") (name "unconnected-(SV_BUS_CONTROL_3-Pad7)") (class "Default")
      (node (ref "SV_BUS_CONTROL_3") (pin "7") (pinfunction "7_7") (pintype "passive"))
    )
    (net (code "261") (name "unconnected-(SV_BUS_CONTROL_3-Pad9)") (class "Default")
      (node (ref "SV_BUS_CONTROL_3") (pin "9") (pinfunction "9_9") (pintype "passive"))
    )
    (net (code "262") (name "unconnected-(SV_BUS_CONTROL_3-Pad17)") (class "Default")
      (node (ref "SV_BUS_CONTROL_3") (pin "17") (pinfunction "17_17") (pintype "passive"))
    )
    (net (code "263") (name "unconnected-(SV_BUS_CONTROL_3-Pad19)") (class "Default")
      (node (ref "SV_BUS_CONTROL_3") (pin "19") (pinfunction "19_19") (pintype "passive"))
    )
    (net (code "264") (name "unconnected-(SV_BUS_CONTROL_3-Pad27)") (class "Default")
      (node (ref "SV_BUS_CONTROL_3") (pin "27") (pinfunction "27_27") (pintype "passive"))
    )
    (net (code "265") (name "unconnected-(SV_BUS_CONTROL_3-Pad29)") (class "Default")
      (node (ref "SV_BUS_CONTROL_3") (pin "29") (pinfunction "29_29") (pintype "passive"))
    )
    (net (code "266") (name "unconnected-(SV_BUS_CONTROL_3-Pad31)") (class "Default")
      (node (ref "SV_BUS_CONTROL_3") (pin "31") (pinfunction "31_31") (pintype "passive"))
    )
    (net (code "267") (name "unconnected-(SV_BUS_CONTROL_3-Pad33)") (class "Default")
      (node (ref "SV_BUS_CONTROL_3") (pin "33") (pinfunction "33_33") (pintype "passive"))
    )
    (net (code "268") (name "unconnected-(SV_BUS_CONTROL_4-Pad3)") (class "Default")
      (node (ref "SV_BUS_CONTROL_4") (pin "3") (pinfunction "3_3") (pintype "passive"))
    )
    (net (code "269") (name "unconnected-(SV_BUS_CONTROL_4-Pad4)") (class "Default")
      (node (ref "SV_BUS_CONTROL_4") (pin "4") (pinfunction "4_4") (pintype "passive"))
    )
    (net (code "270") (name "unconnected-(SV_BUS_CONTROL_4-Pad5)") (class "Default")
      (node (ref "SV_BUS_CONTROL_4") (pin "5") (pinfunction "5_5") (pintype "passive"))
    )
    (net (code "271") (name "unconnected-(SV_BUS_CONTROL_4-Pad6)") (class "Default")
      (node (ref "SV_BUS_CONTROL_4") (pin "6") (pinfunction "6_6") (pintype "passive"))
    )
    (net (code "272") (name "unconnected-(SV_BUS_CONTROL_4-Pad7)") (class "Default")
      (node (ref "SV_BUS_CONTROL_4") (pin "7") (pinfunction "7_7") (pintype "passive"))
    )
    (net (code "273") (name "unconnected-(SV_BUS_CONTROL_4-Pad8)") (class "Default")
      (node (ref "SV_BUS_CONTROL_4") (pin "8") (pinfunction "8_8") (pintype "passive"))
    )
    (net (code "274") (name "unconnected-(SV_BUS_CONTROL_4-Pad9)") (class "Default")
      (node (ref "SV_BUS_CONTROL_4") (pin "9") (pinfunction "9_9") (pintype "passive"))
    )
    (net (code "275") (name "unconnected-(SV_BUS_CONTROL_4-Pad10)") (class "Default")
      (node (ref "SV_BUS_CONTROL_4") (pin "10") (pinfunction "10_10") (pintype "passive"))
    )
    (net (code "276") (name "unconnected-(SV_BUS_CONTROL_4-Pad11)") (class "Default")
      (node (ref "SV_BUS_CONTROL_4") (pin "11") (pinfunction "11_11") (pintype "passive"))
    )
    (net (code "277") (name "unconnected-(SV_BUS_CONTROL_4-Pad12)") (class "Default")
      (node (ref "SV_BUS_CONTROL_4") (pin "12") (pinfunction "12_12") (pintype "passive"))
    )
    (net (code "278") (name "unconnected-(SV_BUS_CONTROL_4-Pad13)") (class "Default")
      (node (ref "SV_BUS_CONTROL_4") (pin "13") (pinfunction "13_13") (pintype "passive"))
    )
    (net (code "279") (name "unconnected-(SV_BUS_CONTROL_4-Pad14)") (class "Default")
      (node (ref "SV_BUS_CONTROL_4") (pin "14") (pinfunction "14_14") (pintype "passive"))
    )
    (net (code "280") (name "unconnected-(SV_BUS_CONTROL_4-Pad15)") (class "Default")
      (node (ref "SV_BUS_CONTROL_4") (pin "15") (pinfunction "15_15") (pintype "passive"))
    )
    (net (code "281") (name "unconnected-(SV_BUS_CONTROL_4-Pad16)") (class "Default")
      (node (ref "SV_BUS_CONTROL_4") (pin "16") (pinfunction "16_16") (pintype "passive"))
    )
    (net (code "282") (name "unconnected-(SV_BUS_CONTROL_4-Pad17)") (class "Default")
      (node (ref "SV_BUS_CONTROL_4") (pin "17") (pinfunction "17_17") (pintype "passive"))
    )
    (net (code "283") (name "unconnected-(SV_BUS_CONTROL_4-Pad18)") (class "Default")
      (node (ref "SV_BUS_CONTROL_4") (pin "18") (pinfunction "18_18") (pintype "passive"))
    )
    (net (code "284") (name "unconnected-(SV_BUS_CONTROL_4-Pad19)") (class "Default")
      (node (ref "SV_BUS_CONTROL_4") (pin "19") (pinfunction "19_19") (pintype "passive"))
    )
    (net (code "285") (name "unconnected-(SV_BUS_CONTROL_4-Pad20)") (class "Default")
      (node (ref "SV_BUS_CONTROL_4") (pin "20") (pinfunction "20_20") (pintype "passive"))
    )
    (net (code "286") (name "unconnected-(SV_BUS_CONTROL_4-Pad21)") (class "Default")
      (node (ref "SV_BUS_CONTROL_4") (pin "21") (pinfunction "21_21") (pintype "passive"))
    )
    (net (code "287") (name "unconnected-(SV_BUS_CONTROL_4-Pad22)") (class "Default")
      (node (ref "SV_BUS_CONTROL_4") (pin "22") (pinfunction "22_22") (pintype "passive"))
    )
    (net (code "288") (name "unconnected-(SV_BUS_CONTROL_4-Pad23)") (class "Default")
      (node (ref "SV_BUS_CONTROL_4") (pin "23") (pinfunction "23_23") (pintype "passive"))
    )
    (net (code "289") (name "unconnected-(SV_BUS_CONTROL_4-Pad24)") (class "Default")
      (node (ref "SV_BUS_CONTROL_4") (pin "24") (pinfunction "24_24") (pintype "passive"))
    )
    (net (code "290") (name "unconnected-(SV_BUS_CONTROL_4-Pad25)") (class "Default")
      (node (ref "SV_BUS_CONTROL_4") (pin "25") (pinfunction "25_25") (pintype "passive"))
    )
    (net (code "291") (name "unconnected-(SV_BUS_CONTROL_4-Pad26)") (class "Default")
      (node (ref "SV_BUS_CONTROL_4") (pin "26") (pinfunction "26_26") (pintype "passive"))
    )
    (net (code "292") (name "unconnected-(SV_BUS_CONTROL_4-Pad27)") (class "Default")
      (node (ref "SV_BUS_CONTROL_4") (pin "27") (pinfunction "27_27") (pintype "passive"))
    )
    (net (code "293") (name "unconnected-(SV_BUS_CONTROL_4-Pad28)") (class "Default")
      (node (ref "SV_BUS_CONTROL_4") (pin "28") (pinfunction "28_28") (pintype "passive"))
    )
    (net (code "294") (name "unconnected-(SV_BUS_CONTROL_4-Pad29)") (class "Default")
      (node (ref "SV_BUS_CONTROL_4") (pin "29") (pinfunction "29_29") (pintype "passive"))
    )
    (net (code "295") (name "unconnected-(SV_BUS_CONTROL_4-Pad30)") (class "Default")
      (node (ref "SV_BUS_CONTROL_4") (pin "30") (pinfunction "30_30") (pintype "passive"))
    )
    (net (code "296") (name "unconnected-(SV_BUS_CONTROL_4-Pad31)") (class "Default")
      (node (ref "SV_BUS_CONTROL_4") (pin "31") (pinfunction "31_31") (pintype "passive"))
    )
    (net (code "297") (name "unconnected-(SV_BUS_CONTROL_4-Pad32)") (class "Default")
      (node (ref "SV_BUS_CONTROL_4") (pin "32") (pinfunction "32_32") (pintype "passive"))
    )
    (net (code "298") (name "unconnected-(SV_BUS_CONTROL_4-Pad33)") (class "Default")
      (node (ref "SV_BUS_CONTROL_4") (pin "33") (pinfunction "33_33") (pintype "passive"))
    )
    (net (code "299") (name "unconnected-(SV_BUS_CONTROL_4-Pad34)") (class "Default")
      (node (ref "SV_BUS_CONTROL_4") (pin "34") (pinfunction "34_34") (pintype "passive"))
    )
    (net (code "300") (name "unconnected-(SV_CONST_REG_1-Pad3)") (class "Default")
      (node (ref "SV_CONST_REG_1") (pin "3") (pinfunction "3_3") (pintype "passive"))
    )
    (net (code "301") (name "unconnected-(SV_CONST_REG_1-Pad4)") (class "Default")
      (node (ref "SV_CONST_REG_1") (pin "4") (pinfunction "4_4") (pintype "passive"))
    )
    (net (code "302") (name "unconnected-(SV_CONST_REG_1-Pad5)") (class "Default")
      (node (ref "SV_CONST_REG_1") (pin "5") (pinfunction "5_5") (pintype "passive"))
    )
    (net (code "303") (name "unconnected-(SV_CONST_REG_1-Pad6)") (class "Default")
      (node (ref "SV_CONST_REG_1") (pin "6") (pinfunction "6_6") (pintype "passive"))
    )
    (net (code "304") (name "unconnected-(SV_CONST_REG_1-Pad7)") (class "Default")
      (node (ref "SV_CONST_REG_1") (pin "7") (pinfunction "7_7") (pintype "passive"))
    )
    (net (code "305") (name "unconnected-(SV_CONST_REG_1-Pad8)") (class "Default")
      (node (ref "SV_CONST_REG_1") (pin "8") (pinfunction "8_8") (pintype "passive"))
    )
    (net (code "306") (name "unconnected-(SV_CONST_REG_1-Pad9)") (class "Default")
      (node (ref "SV_CONST_REG_1") (pin "9") (pinfunction "9_9") (pintype "passive"))
    )
    (net (code "307") (name "unconnected-(SV_CONST_REG_1-Pad10)") (class "Default")
      (node (ref "SV_CONST_REG_1") (pin "10") (pinfunction "10_10") (pintype "passive"))
    )
    (net (code "308") (name "unconnected-(SV_CONST_REG_1-Pad11)") (class "Default")
      (node (ref "SV_CONST_REG_1") (pin "11") (pinfunction "11_11") (pintype "passive"))
    )
    (net (code "309") (name "unconnected-(SV_CONST_REG_1-Pad13)") (class "Default")
      (node (ref "SV_CONST_REG_1") (pin "13") (pinfunction "13_13") (pintype "passive"))
    )
    (net (code "310") (name "unconnected-(SV_CONST_REG_1-Pad15)") (class "Default")
      (node (ref "SV_CONST_REG_1") (pin "15") (pinfunction "15_15") (pintype "passive"))
    )
    (net (code "311") (name "unconnected-(SV_CONST_REG_1-Pad17)") (class "Default")
      (node (ref "SV_CONST_REG_1") (pin "17") (pinfunction "17_17") (pintype "passive"))
    )
    (net (code "312") (name "unconnected-(SV_CONST_REG_1-Pad20)") (class "Default")
      (node (ref "SV_CONST_REG_1") (pin "20") (pinfunction "20_20") (pintype "passive"))
    )
    (net (code "313") (name "unconnected-(SV_CONST_REG_1-Pad22)") (class "Default")
      (node (ref "SV_CONST_REG_1") (pin "22") (pinfunction "22_22") (pintype "passive"))
    )
    (net (code "314") (name "unconnected-(SV_CONST_REG_1-Pad24)") (class "Default")
      (node (ref "SV_CONST_REG_1") (pin "24") (pinfunction "24_24") (pintype "passive"))
    )
    (net (code "315") (name "unconnected-(SV_CONST_REG_1-Pad26)") (class "Default")
      (node (ref "SV_CONST_REG_1") (pin "26") (pinfunction "26_26") (pintype "passive"))
    )
    (net (code "316") (name "unconnected-(SV_CONST_REG_1-Pad28)") (class "Default")
      (node (ref "SV_CONST_REG_1") (pin "28") (pinfunction "28_28") (pintype "passive"))
    )
    (net (code "317") (name "unconnected-(SV_CONST_REG_1-Pad30)") (class "Default")
      (node (ref "SV_CONST_REG_1") (pin "30") (pinfunction "30_30") (pintype "passive"))
    )
    (net (code "318") (name "unconnected-(SV_CONST_REG_1-Pad32)") (class "Default")
      (node (ref "SV_CONST_REG_1") (pin "32") (pinfunction "32_32") (pintype "passive"))
    )
    (net (code "319") (name "unconnected-(SV_CONST_REG_1-Pad34)") (class "Default")
      (node (ref "SV_CONST_REG_1") (pin "34") (pinfunction "34_34") (pintype "passive"))
    )
    (net (code "320") (name "unconnected-(SV_CONST_REG_2-Pad4)") (class "Default")
      (node (ref "SV_CONST_REG_2") (pin "4") (pinfunction "4_4") (pintype "passive"))
    )
    (net (code "321") (name "unconnected-(SV_CONST_REG_2-Pad5)") (class "Default")
      (node (ref "SV_CONST_REG_2") (pin "5") (pinfunction "5_5") (pintype "passive"))
    )
    (net (code "322") (name "unconnected-(SV_CONST_REG_2-Pad6)") (class "Default")
      (node (ref "SV_CONST_REG_2") (pin "6") (pinfunction "6_6") (pintype "passive"))
    )
    (net (code "323") (name "unconnected-(SV_CONST_REG_2-Pad7)") (class "Default")
      (node (ref "SV_CONST_REG_2") (pin "7") (pinfunction "7_7") (pintype "passive"))
    )
    (net (code "324") (name "unconnected-(SV_CONST_REG_2-Pad8)") (class "Default")
      (node (ref "SV_CONST_REG_2") (pin "8") (pinfunction "8_8") (pintype "passive"))
    )
    (net (code "325") (name "unconnected-(SV_CONST_REG_2-Pad9)") (class "Default")
      (node (ref "SV_CONST_REG_2") (pin "9") (pinfunction "9_9") (pintype "passive"))
    )
    (net (code "326") (name "unconnected-(SV_CONST_REG_2-Pad10)") (class "Default")
      (node (ref "SV_CONST_REG_2") (pin "10") (pinfunction "10_10") (pintype "passive"))
    )
    (net (code "327") (name "unconnected-(SV_CONST_REG_2-Pad11)") (class "Default")
      (node (ref "SV_CONST_REG_2") (pin "11") (pinfunction "11_11") (pintype "passive"))
    )
    (net (code "328") (name "unconnected-(SV_CONST_REG_2-Pad12)") (class "Default")
      (node (ref "SV_CONST_REG_2") (pin "12") (pinfunction "12_12") (pintype "passive"))
    )
    (net (code "329") (name "unconnected-(SV_CONST_REG_2-Pad13)") (class "Default")
      (node (ref "SV_CONST_REG_2") (pin "13") (pinfunction "13_13") (pintype "passive"))
    )
    (net (code "330") (name "unconnected-(SV_CONST_REG_2-Pad14)") (class "Default")
      (node (ref "SV_CONST_REG_2") (pin "14") (pinfunction "14_14") (pintype "passive"))
    )
    (net (code "331") (name "unconnected-(SV_CONST_REG_2-Pad15)") (class "Default")
      (node (ref "SV_CONST_REG_2") (pin "15") (pinfunction "15_15") (pintype "passive"))
    )
    (net (code "332") (name "unconnected-(SV_CONST_REG_2-Pad16)") (class "Default")
      (node (ref "SV_CONST_REG_2") (pin "16") (pinfunction "16_16") (pintype "passive"))
    )
    (net (code "333") (name "unconnected-(SV_CONST_REG_2-Pad23)") (class "Default")
      (node (ref "SV_CONST_REG_2") (pin "23") (pinfunction "23_23") (pintype "passive"))
    )
    (net (code "334") (name "unconnected-(SV_CONST_REG_2-Pad25)") (class "Default")
      (node (ref "SV_CONST_REG_2") (pin "25") (pinfunction "25_25") (pintype "passive"))
    )
    (net (code "335") (name "unconnected-(SV_CONST_REG_2-Pad27)") (class "Default")
      (node (ref "SV_CONST_REG_2") (pin "27") (pinfunction "27_27") (pintype "passive"))
    )
    (net (code "336") (name "unconnected-(SV_CONST_REG_2-Pad29)") (class "Default")
      (node (ref "SV_CONST_REG_2") (pin "29") (pinfunction "29_29") (pintype "passive"))
    )
    (net (code "337") (name "unconnected-(SV_CONST_REG_2-Pad31)") (class "Default")
      (node (ref "SV_CONST_REG_2") (pin "31") (pinfunction "31_31") (pintype "passive"))
    )
    (net (code "338") (name "unconnected-(SV_CONST_REG_2-Pad33)") (class "Default")
      (node (ref "SV_CONST_REG_2") (pin "33") (pinfunction "33_33") (pintype "passive"))
    )
    (net (code "339") (name "unconnected-(SV_CREG_1-Pad4)") (class "Default")
      (node (ref "SV_CREG_1") (pin "4") (pinfunction "4_4") (pintype "passive"))
    )
    (net (code "340") (name "unconnected-(SV_CREG_1-Pad6)") (class "Default")
      (node (ref "SV_CREG_1") (pin "6") (pinfunction "6_6") (pintype "passive"))
    )
    (net (code "341") (name "unconnected-(SV_CREG_1-Pad8)") (class "Default")
      (node (ref "SV_CREG_1") (pin "8") (pinfunction "8_8") (pintype "passive"))
    )
    (net (code "342") (name "unconnected-(SV_CREG_1-Pad10)") (class "Default")
      (node (ref "SV_CREG_1") (pin "10") (pinfunction "10_10") (pintype "passive"))
    )
    (net (code "343") (name "unconnected-(SV_CREG_1-Pad12)") (class "Default")
      (node (ref "SV_CREG_1") (pin "12") (pinfunction "12_12") (pintype "passive"))
    )
    (net (code "344") (name "unconnected-(SV_CREG_1-Pad14)") (class "Default")
      (node (ref "SV_CREG_1") (pin "14") (pinfunction "14_14") (pintype "passive"))
    )
    (net (code "345") (name "unconnected-(SV_CREG_1-Pad15)") (class "Default")
      (node (ref "SV_CREG_1") (pin "15") (pinfunction "15_15") (pintype "passive"))
    )
    (net (code "346") (name "unconnected-(SV_CREG_1-Pad17)") (class "Default")
      (node (ref "SV_CREG_1") (pin "17") (pinfunction "17_17") (pintype "passive"))
    )
    (net (code "347") (name "unconnected-(SV_CREG_1-Pad19)") (class "Default")
      (node (ref "SV_CREG_1") (pin "19") (pinfunction "19_19") (pintype "passive"))
    )
    (net (code "348") (name "unconnected-(SV_CREG_1-Pad21)") (class "Default")
      (node (ref "SV_CREG_1") (pin "21") (pinfunction "21_21") (pintype "passive"))
    )
    (net (code "349") (name "unconnected-(SV_CREG_1-Pad23)") (class "Default")
      (node (ref "SV_CREG_1") (pin "23") (pinfunction "23_23") (pintype "passive"))
    )
    (net (code "350") (name "unconnected-(SV_CREG_1-Pad25)") (class "Default")
      (node (ref "SV_CREG_1") (pin "25") (pinfunction "25_25") (pintype "passive"))
    )
    (net (code "351") (name "unconnected-(SV_CREG_1-Pad27)") (class "Default")
      (node (ref "SV_CREG_1") (pin "27") (pinfunction "27_27") (pintype "passive"))
    )
    (net (code "352") (name "unconnected-(SV_EXT_3-Pad3)") (class "Default")
      (node (ref "SV_EXT_3") (pin "3") (pinfunction "3_3") (pintype "passive"))
    )
    (net (code "353") (name "unconnected-(SV_EXT_4-Pad3)") (class "Default")
      (node (ref "SV_EXT_4") (pin "3") (pinfunction "3_3") (pintype "passive"))
    )
    (net (code "354") (name "unconnected-(SV_EXT_4-Pad4)") (class "Default")
      (node (ref "SV_EXT_4") (pin "4") (pinfunction "4_4") (pintype "passive"))
    )
    (net (code "355") (name "unconnected-(SV_EXT_4-Pad5)") (class "Default")
      (node (ref "SV_EXT_4") (pin "5") (pinfunction "5_5") (pintype "passive"))
    )
    (net (code "356") (name "unconnected-(SV_EXT_4-Pad6)") (class "Default")
      (node (ref "SV_EXT_4") (pin "6") (pinfunction "6_6") (pintype "passive"))
    )
    (net (code "357") (name "unconnected-(SV_EXT_4-Pad7)") (class "Default")
      (node (ref "SV_EXT_4") (pin "7") (pinfunction "7_7") (pintype "passive"))
    )
    (net (code "358") (name "unconnected-(SV_EXT_4-Pad8)") (class "Default")
      (node (ref "SV_EXT_4") (pin "8") (pinfunction "8_8") (pintype "passive"))
    )
    (net (code "359") (name "unconnected-(SV_EXT_4-Pad9)") (class "Default")
      (node (ref "SV_EXT_4") (pin "9") (pinfunction "9_9") (pintype "passive"))
    )
    (net (code "360") (name "unconnected-(SV_EXT_4-Pad10)") (class "Default")
      (node (ref "SV_EXT_4") (pin "10") (pinfunction "10_10") (pintype "passive"))
    )
    (net (code "361") (name "unconnected-(SV_EXT_4-Pad11)") (class "Default")
      (node (ref "SV_EXT_4") (pin "11") (pinfunction "11_11") (pintype "passive"))
    )
    (net (code "362") (name "unconnected-(SV_EXT_4-Pad12)") (class "Default")
      (node (ref "SV_EXT_4") (pin "12") (pinfunction "12_12") (pintype "passive"))
    )
    (net (code "363") (name "unconnected-(SV_EXT_4-Pad13)") (class "Default")
      (node (ref "SV_EXT_4") (pin "13") (pinfunction "13_13") (pintype "passive"))
    )
    (net (code "364") (name "unconnected-(SV_EXT_4-Pad14)") (class "Default")
      (node (ref "SV_EXT_4") (pin "14") (pinfunction "14_14") (pintype "passive"))
    )
    (net (code "365") (name "unconnected-(SV_EXT_4-Pad15)") (class "Default")
      (node (ref "SV_EXT_4") (pin "15") (pinfunction "15_15") (pintype "passive"))
    )
    (net (code "366") (name "unconnected-(SV_EXT_4-Pad16)") (class "Default")
      (node (ref "SV_EXT_4") (pin "16") (pinfunction "16_16") (pintype "passive"))
    )
    (net (code "367") (name "unconnected-(SV_EXT_4-Pad17)") (class "Default")
      (node (ref "SV_EXT_4") (pin "17") (pinfunction "17_17") (pintype "passive"))
    )
    (net (code "368") (name "unconnected-(SV_EXT_4-Pad18)") (class "Default")
      (node (ref "SV_EXT_4") (pin "18") (pinfunction "18_18") (pintype "passive"))
    )
    (net (code "369") (name "unconnected-(SV_EXT_4-Pad19)") (class "Default")
      (node (ref "SV_EXT_4") (pin "19") (pinfunction "19_19") (pintype "passive"))
    )
    (net (code "370") (name "unconnected-(SV_EXT_4-Pad20)") (class "Default")
      (node (ref "SV_EXT_4") (pin "20") (pinfunction "20_20") (pintype "passive"))
    )
    (net (code "371") (name "unconnected-(SV_EXT_4-Pad21)") (class "Default")
      (node (ref "SV_EXT_4") (pin "21") (pinfunction "21_21") (pintype "passive"))
    )
    (net (code "372") (name "unconnected-(SV_EXT_4-Pad22)") (class "Default")
      (node (ref "SV_EXT_4") (pin "22") (pinfunction "22_22") (pintype "passive"))
    )
    (net (code "373") (name "unconnected-(SV_EXT_4-Pad23)") (class "Default")
      (node (ref "SV_EXT_4") (pin "23") (pinfunction "23_23") (pintype "passive"))
    )
    (net (code "374") (name "unconnected-(SV_EXT_4-Pad24)") (class "Default")
      (node (ref "SV_EXT_4") (pin "24") (pinfunction "24_24") (pintype "passive"))
    )
    (net (code "375") (name "unconnected-(SV_EXT_4-Pad25)") (class "Default")
      (node (ref "SV_EXT_4") (pin "25") (pinfunction "25_25") (pintype "passive"))
    )
    (net (code "376") (name "unconnected-(SV_EXT_4-Pad26)") (class "Default")
      (node (ref "SV_EXT_4") (pin "26") (pinfunction "26_26") (pintype "passive"))
    )
    (net (code "377") (name "unconnected-(SV_EXT_4-Pad27)") (class "Default")
      (node (ref "SV_EXT_4") (pin "27") (pinfunction "27_27") (pintype "passive"))
    )
    (net (code "378") (name "unconnected-(SV_EXT_4-Pad28)") (class "Default")
      (node (ref "SV_EXT_4") (pin "28") (pinfunction "28_28") (pintype "passive"))
    )
    (net (code "379") (name "unconnected-(SV_EXT_4-Pad29)") (class "Default")
      (node (ref "SV_EXT_4") (pin "29") (pinfunction "29_29") (pintype "passive"))
    )
    (net (code "380") (name "unconnected-(SV_EXT_4-Pad30)") (class "Default")
      (node (ref "SV_EXT_4") (pin "30") (pinfunction "30_30") (pintype "passive"))
    )
    (net (code "381") (name "unconnected-(SV_EXT_4-Pad31)") (class "Default")
      (node (ref "SV_EXT_4") (pin "31") (pinfunction "31_31") (pintype "passive"))
    )
    (net (code "382") (name "unconnected-(SV_EXT_4-Pad32)") (class "Default")
      (node (ref "SV_EXT_4") (pin "32") (pinfunction "32_32") (pintype "passive"))
    )
    (net (code "383") (name "unconnected-(SV_EXT_4-Pad33)") (class "Default")
      (node (ref "SV_EXT_4") (pin "33") (pinfunction "33_33") (pintype "passive"))
    )
    (net (code "384") (name "unconnected-(SV_EXT_4-Pad34)") (class "Default")
      (node (ref "SV_EXT_4") (pin "34") (pinfunction "34_34") (pintype "passive"))
    )
    (net (code "385") (name "unconnected-(SV_XFER_2-Pad3)") (class "Default")
      (node (ref "SV_XFER_2") (pin "3") (pinfunction "3_3") (pintype "passive"))
    )
    (net (code "386") (name "unconnected-(SV_XFER_2-Pad5)") (class "Default")
      (node (ref "SV_XFER_2") (pin "5") (pinfunction "5_5") (pintype "passive"))
    )
    (net (code "387") (name "unconnected-(SV_XFER_2-Pad7)") (class "Default")
      (node (ref "SV_XFER_2") (pin "7") (pinfunction "7_7") (pintype "passive"))
    )
    (net (code "388") (name "unconnected-(SV_XFER_2-Pad9)") (class "Default")
      (node (ref "SV_XFER_2") (pin "9") (pinfunction "9_9") (pintype "passive"))
    )
    (net (code "389") (name "unconnected-(SV_XFER_2-Pad11)") (class "Default")
      (node (ref "SV_XFER_2") (pin "11") (pinfunction "11_11") (pintype "passive"))
    )
    (net (code "390") (name "unconnected-(SV_XFER_2-Pad12)") (class "Default")
      (node (ref "SV_XFER_2") (pin "12") (pinfunction "12_12") (pintype "passive"))
    )
    (net (code "391") (name "unconnected-(SV_XFER_2-Pad13)") (class "Default")
      (node (ref "SV_XFER_2") (pin "13") (pinfunction "13_13") (pintype "passive"))
    )
    (net (code "392") (name "unconnected-(SV_XFER_2-Pad14)") (class "Default")
      (node (ref "SV_XFER_2") (pin "14") (pinfunction "14_14") (pintype "passive"))
    )
    (net (code "393") (name "unconnected-(SV_XFER_2-Pad15)") (class "Default")
      (node (ref "SV_XFER_2") (pin "15") (pinfunction "15_15") (pintype "passive"))
    )
    (net (code "394") (name "unconnected-(SV_XFER_2-Pad16)") (class "Default")
      (node (ref "SV_XFER_2") (pin "16") (pinfunction "16_16") (pintype "passive"))
    )
    (net (code "395") (name "unconnected-(SV_XFER_2-Pad17)") (class "Default")
      (node (ref "SV_XFER_2") (pin "17") (pinfunction "17_17") (pintype "passive"))
    )
    (net (code "396") (name "unconnected-(SV_XFER_2-Pad18)") (class "Default")
      (node (ref "SV_XFER_2") (pin "18") (pinfunction "18_18") (pintype "passive"))
    )
    (net (code "397") (name "unconnected-(SV_XFER_2-Pad27)") (class "Default")
      (node (ref "SV_XFER_2") (pin "27") (pinfunction "27_27") (pintype "passive"))
    )
    (net (code "398") (name "unconnected-(SV_XFER_3-Pad3)") (class "Default")
      (node (ref "SV_XFER_3") (pin "3") (pinfunction "3_3") (pintype "passive"))
    )
    (net (code "399") (name "unconnected-(SV_XFER_3-Pad4)") (class "Default")
      (node (ref "SV_XFER_3") (pin "4") (pinfunction "4_4") (pintype "passive"))
    )
    (net (code "400") (name "unconnected-(SV_XFER_3-Pad5)") (class "Default")
      (node (ref "SV_XFER_3") (pin "5") (pinfunction "5_5") (pintype "passive"))
    )
    (net (code "401") (name "unconnected-(SV_XFER_3-Pad6)") (class "Default")
      (node (ref "SV_XFER_3") (pin "6") (pinfunction "6_6") (pintype "passive"))
    )
    (net (code "402") (name "unconnected-(SV_XFER_3-Pad7)") (class "Default")
      (node (ref "SV_XFER_3") (pin "7") (pinfunction "7_7") (pintype "passive"))
    )
    (net (code "403") (name "unconnected-(SV_XFER_3-Pad8)") (class "Default")
      (node (ref "SV_XFER_3") (pin "8") (pinfunction "8_8") (pintype "passive"))
    )
    (net (code "404") (name "unconnected-(SV_XFER_3-Pad9)") (class "Default")
      (node (ref "SV_XFER_3") (pin "9") (pinfunction "9_9") (pintype "passive"))
    )
    (net (code "405") (name "unconnected-(SV_XFER_3-Pad10)") (class "Default")
      (node (ref "SV_XFER_3") (pin "10") (pinfunction "10_10") (pintype "passive"))
    )
    (net (code "406") (name "unconnected-(SV_XFER_3-Pad11)") (class "Default")
      (node (ref "SV_XFER_3") (pin "11") (pinfunction "11_11") (pintype "passive"))
    )
    (net (code "407") (name "unconnected-(SV_XFER_3-Pad12)") (class "Default")
      (node (ref "SV_XFER_3") (pin "12") (pinfunction "12_12") (pintype "passive"))
    )
    (net (code "408") (name "unconnected-(SV_XFER_3-Pad13)") (class "Default")
      (node (ref "SV_XFER_3") (pin "13") (pinfunction "13_13") (pintype "passive"))
    )
    (net (code "409") (name "unconnected-(SV_XFER_3-Pad14)") (class "Default")
      (node (ref "SV_XFER_3") (pin "14") (pinfunction "14_14") (pintype "passive"))
    )
    (net (code "410") (name "unconnected-(SV_XFER_3-Pad15)") (class "Default")
      (node (ref "SV_XFER_3") (pin "15") (pinfunction "15_15") (pintype "passive"))
    )
    (net (code "411") (name "unconnected-(SV_XFER_3-Pad16)") (class "Default")
      (node (ref "SV_XFER_3") (pin "16") (pinfunction "16_16") (pintype "passive"))
    )
    (net (code "412") (name "unconnected-(SV_XFER_3-Pad17)") (class "Default")
      (node (ref "SV_XFER_3") (pin "17") (pinfunction "17_17") (pintype "passive"))
    )
    (net (code "413") (name "unconnected-(SV_XFER_3-Pad18)") (class "Default")
      (node (ref "SV_XFER_3") (pin "18") (pinfunction "18_18") (pintype "passive"))
    )
    (net (code "414") (name "unconnected-(SV_XFER_3-Pad19)") (class "Default")
      (node (ref "SV_XFER_3") (pin "19") (pinfunction "19_19") (pintype "passive"))
    )
    (net (code "415") (name "unconnected-(SV_XFER_3-Pad20)") (class "Default")
      (node (ref "SV_XFER_3") (pin "20") (pinfunction "20_20") (pintype "passive"))
    )
    (net (code "416") (name "unconnected-(SV_XFER_3-Pad21)") (class "Default")
      (node (ref "SV_XFER_3") (pin "21") (pinfunction "21_21") (pintype "passive"))
    )
    (net (code "417") (name "unconnected-(SV_XFER_3-Pad22)") (class "Default")
      (node (ref "SV_XFER_3") (pin "22") (pinfunction "22_22") (pintype "passive"))
    )
    (net (code "418") (name "unconnected-(SV_XFER_3-Pad23)") (class "Default")
      (node (ref "SV_XFER_3") (pin "23") (pinfunction "23_23") (pintype "passive"))
    )
    (net (code "419") (name "unconnected-(SV_XFER_3-Pad24)") (class "Default")
      (node (ref "SV_XFER_3") (pin "24") (pinfunction "24_24") (pintype "passive"))
    )
    (net (code "420") (name "unconnected-(SV_XFER_3-Pad25)") (class "Default")
      (node (ref "SV_XFER_3") (pin "25") (pinfunction "25_25") (pintype "passive"))
    )
    (net (code "421") (name "unconnected-(SV_XFER_3-Pad26)") (class "Default")
      (node (ref "SV_XFER_3") (pin "26") (pinfunction "26_26") (pintype "passive"))
    )
    (net (code "422") (name "unconnected-(SV_XFER_3-Pad27)") (class "Default")
      (node (ref "SV_XFER_3") (pin "27") (pinfunction "27_27") (pintype "passive"))
    )
    (net (code "423") (name "unconnected-(SV_XFER_3-Pad28)") (class "Default")
      (node (ref "SV_XFER_3") (pin "28") (pinfunction "28_28") (pintype "passive"))
    )
    (net (code "424") (name "unconnected-(SV_XFER_3-Pad29)") (class "Default")
      (node (ref "SV_XFER_3") (pin "29") (pinfunction "29_29") (pintype "passive"))
    )
    (net (code "425") (name "unconnected-(SV_XFER_3-Pad30)") (class "Default")
      (node (ref "SV_XFER_3") (pin "30") (pinfunction "30_30") (pintype "passive"))
    )
    (net (code "426") (name "unconnected-(SV_XFER_3-Pad31)") (class "Default")
      (node (ref "SV_XFER_3") (pin "31") (pinfunction "31_31") (pintype "passive"))
    )
    (net (code "427") (name "unconnected-(SV_XFER_3-Pad32)") (class "Default")
      (node (ref "SV_XFER_3") (pin "32") (pinfunction "32_32") (pintype "passive"))
    )
    (net (code "428") (name "unconnected-(SV_XFER_3-Pad33)") (class "Default")
      (node (ref "SV_XFER_3") (pin "33") (pinfunction "33_33") (pintype "passive"))
    )
    (net (code "429") (name "unconnected-(SV_XFER_3-Pad34)") (class "Default")
      (node (ref "SV_XFER_3") (pin "34") (pinfunction "34_34") (pintype "passive"))
    )
    (net (code "430") (name "unconnected-(SV_XFER_4-Pad3)") (class "Default")
      (node (ref "SV_XFER_4") (pin "3") (pinfunction "3_3") (pintype "passive"))
    )
    (net (code "431") (name "unconnected-(SV_XFER_4-Pad4)") (class "Default")
      (node (ref "SV_XFER_4") (pin "4") (pinfunction "4_4") (pintype "passive"))
    )
    (net (code "432") (name "unconnected-(SV_XFER_4-Pad5)") (class "Default")
      (node (ref "SV_XFER_4") (pin "5") (pinfunction "5_5") (pintype "passive"))
    )
    (net (code "433") (name "unconnected-(SV_XFER_4-Pad6)") (class "Default")
      (node (ref "SV_XFER_4") (pin "6") (pinfunction "6_6") (pintype "passive"))
    )
    (net (code "434") (name "unconnected-(SV_XFER_4-Pad7)") (class "Default")
      (node (ref "SV_XFER_4") (pin "7") (pinfunction "7_7") (pintype "passive"))
    )
    (net (code "435") (name "unconnected-(SV_XFER_4-Pad8)") (class "Default")
      (node (ref "SV_XFER_4") (pin "8") (pinfunction "8_8") (pintype "passive"))
    )
    (net (code "436") (name "unconnected-(SV_XFER_4-Pad9)") (class "Default")
      (node (ref "SV_XFER_4") (pin "9") (pinfunction "9_9") (pintype "passive"))
    )
    (net (code "437") (name "unconnected-(SV_XFER_4-Pad10)") (class "Default")
      (node (ref "SV_XFER_4") (pin "10") (pinfunction "10_10") (pintype "passive"))
    )
    (net (code "438") (name "unconnected-(SV_XFER_4-Pad11)") (class "Default")
      (node (ref "SV_XFER_4") (pin "11") (pinfunction "11_11") (pintype "passive"))
    )
    (net (code "439") (name "unconnected-(SV_XFER_4-Pad12)") (class "Default")
      (node (ref "SV_XFER_4") (pin "12") (pinfunction "12_12") (pintype "passive"))
    )
    (net (code "440") (name "unconnected-(SV_XFER_4-Pad13)") (class "Default")
      (node (ref "SV_XFER_4") (pin "13") (pinfunction "13_13") (pintype "passive"))
    )
    (net (code "441") (name "unconnected-(SV_XFER_4-Pad14)") (class "Default")
      (node (ref "SV_XFER_4") (pin "14") (pinfunction "14_14") (pintype "passive"))
    )
    (net (code "442") (name "unconnected-(SV_XFER_4-Pad15)") (class "Default")
      (node (ref "SV_XFER_4") (pin "15") (pinfunction "15_15") (pintype "passive"))
    )
    (net (code "443") (name "unconnected-(SV_XFER_4-Pad16)") (class "Default")
      (node (ref "SV_XFER_4") (pin "16") (pinfunction "16_16") (pintype "passive"))
    )
    (net (code "444") (name "unconnected-(SV_XFER_4-Pad17)") (class "Default")
      (node (ref "SV_XFER_4") (pin "17") (pinfunction "17_17") (pintype "passive"))
    )
    (net (code "445") (name "unconnected-(SV_XFER_4-Pad18)") (class "Default")
      (node (ref "SV_XFER_4") (pin "18") (pinfunction "18_18") (pintype "passive"))
    )
    (net (code "446") (name "unconnected-(SV_XFER_4-Pad19)") (class "Default")
      (node (ref "SV_XFER_4") (pin "19") (pinfunction "19_19") (pintype "passive"))
    )
    (net (code "447") (name "unconnected-(SV_XFER_4-Pad20)") (class "Default")
      (node (ref "SV_XFER_4") (pin "20") (pinfunction "20_20") (pintype "passive"))
    )
    (net (code "448") (name "unconnected-(SV_XFER_4-Pad21)") (class "Default")
      (node (ref "SV_XFER_4") (pin "21") (pinfunction "21_21") (pintype "passive"))
    )
    (net (code "449") (name "unconnected-(SV_XFER_4-Pad22)") (class "Default")
      (node (ref "SV_XFER_4") (pin "22") (pinfunction "22_22") (pintype "passive"))
    )
    (net (code "450") (name "unconnected-(SV_XFER_4-Pad23)") (class "Default")
      (node (ref "SV_XFER_4") (pin "23") (pinfunction "23_23") (pintype "passive"))
    )
    (net (code "451") (name "unconnected-(SV_XFER_4-Pad24)") (class "Default")
      (node (ref "SV_XFER_4") (pin "24") (pinfunction "24_24") (pintype "passive"))
    )
    (net (code "452") (name "unconnected-(SV_XFER_4-Pad25)") (class "Default")
      (node (ref "SV_XFER_4") (pin "25") (pinfunction "25_25") (pintype "passive"))
    )
    (net (code "453") (name "unconnected-(SV_XFER_4-Pad26)") (class "Default")
      (node (ref "SV_XFER_4") (pin "26") (pinfunction "26_26") (pintype "passive"))
    )
    (net (code "454") (name "unconnected-(SV_XFER_4-Pad27)") (class "Default")
      (node (ref "SV_XFER_4") (pin "27") (pinfunction "27_27") (pintype "passive"))
    )
    (net (code "455") (name "unconnected-(SV_XFER_4-Pad28)") (class "Default")
      (node (ref "SV_XFER_4") (pin "28") (pinfunction "28_28") (pintype "passive"))
    )
    (net (code "456") (name "unconnected-(SV_XFER_4-Pad29)") (class "Default")
      (node (ref "SV_XFER_4") (pin "29") (pinfunction "29_29") (pintype "passive"))
    )
    (net (code "457") (name "unconnected-(SV_XFER_4-Pad30)") (class "Default")
      (node (ref "SV_XFER_4") (pin "30") (pinfunction "30_30") (pintype "passive"))
    )
    (net (code "458") (name "unconnected-(SV_XFER_4-Pad31)") (class "Default")
      (node (ref "SV_XFER_4") (pin "31") (pinfunction "31_31") (pintype "passive"))
    )
    (net (code "459") (name "unconnected-(SV_XFER_4-Pad32)") (class "Default")
      (node (ref "SV_XFER_4") (pin "32") (pinfunction "32_32") (pintype "passive"))
    )
    (net (code "460") (name "unconnected-(SV_XFER_4-Pad33)") (class "Default")
      (node (ref "SV_XFER_4") (pin "33") (pinfunction "33_33") (pintype "passive"))
    )
    (net (code "461") (name "unconnected-(SV_XFER_4-Pad34)") (class "Default")
      (node (ref "SV_XFER_4") (pin "34") (pinfunction "34_34") (pintype "passive"))
    )
  )
)
